# Smoothieboard_v1_1.net
KiCad netlist of a schematic drawn in Altium Designer
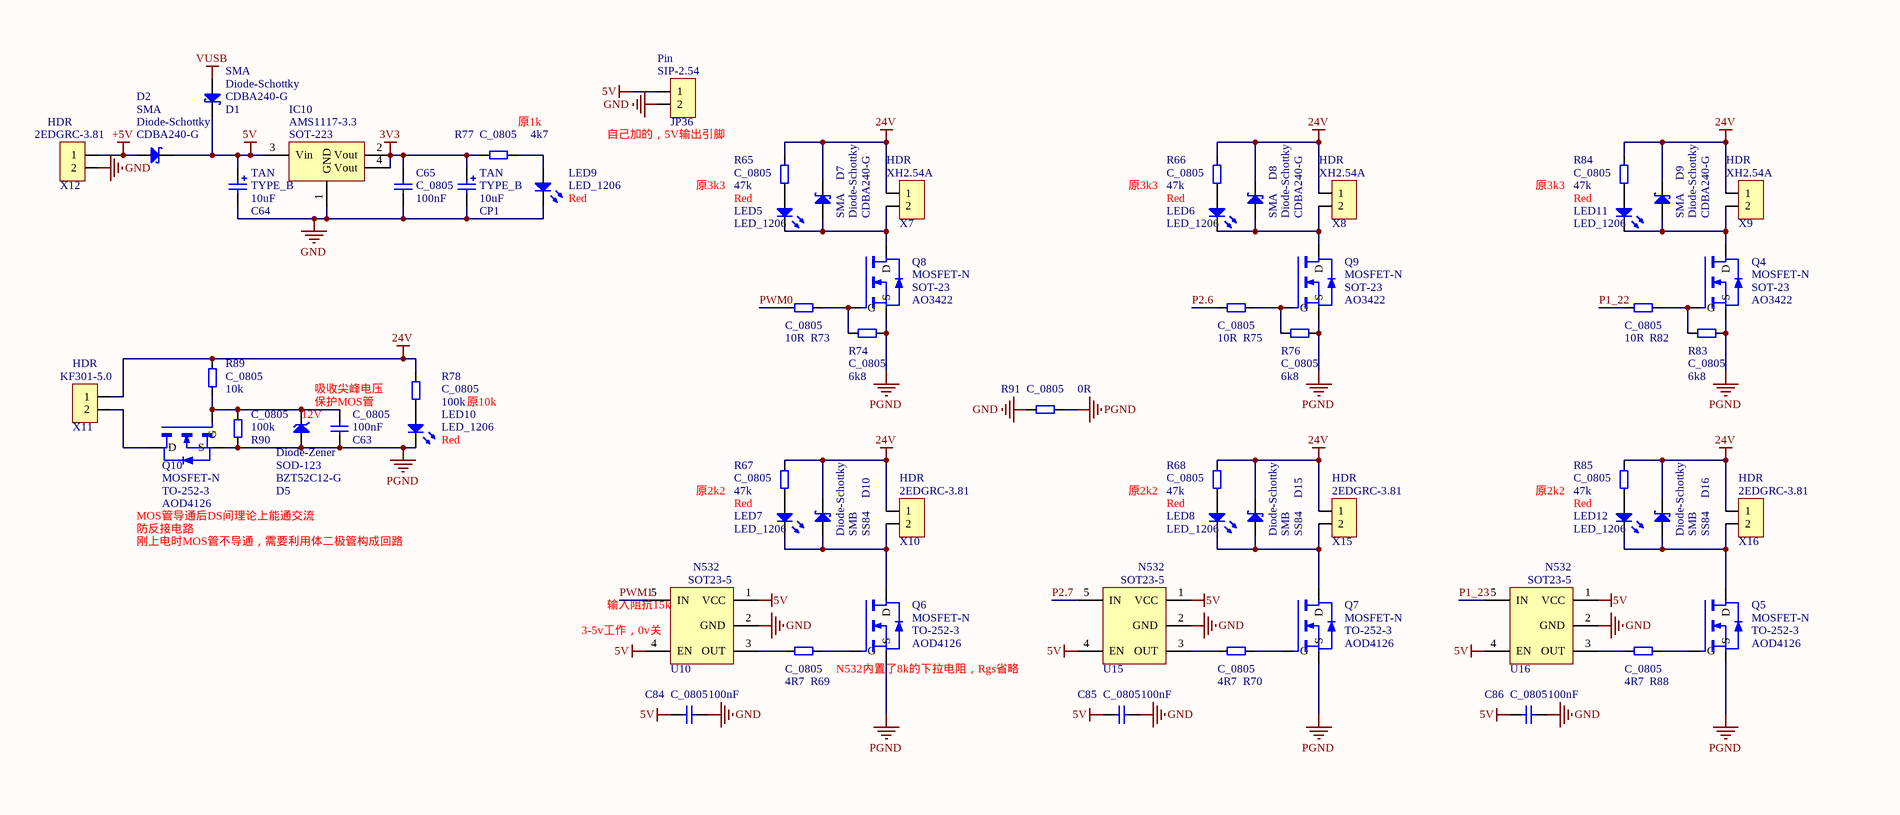
[diagram p0: Smoothieboard_v1.1.SchDoc, top left]
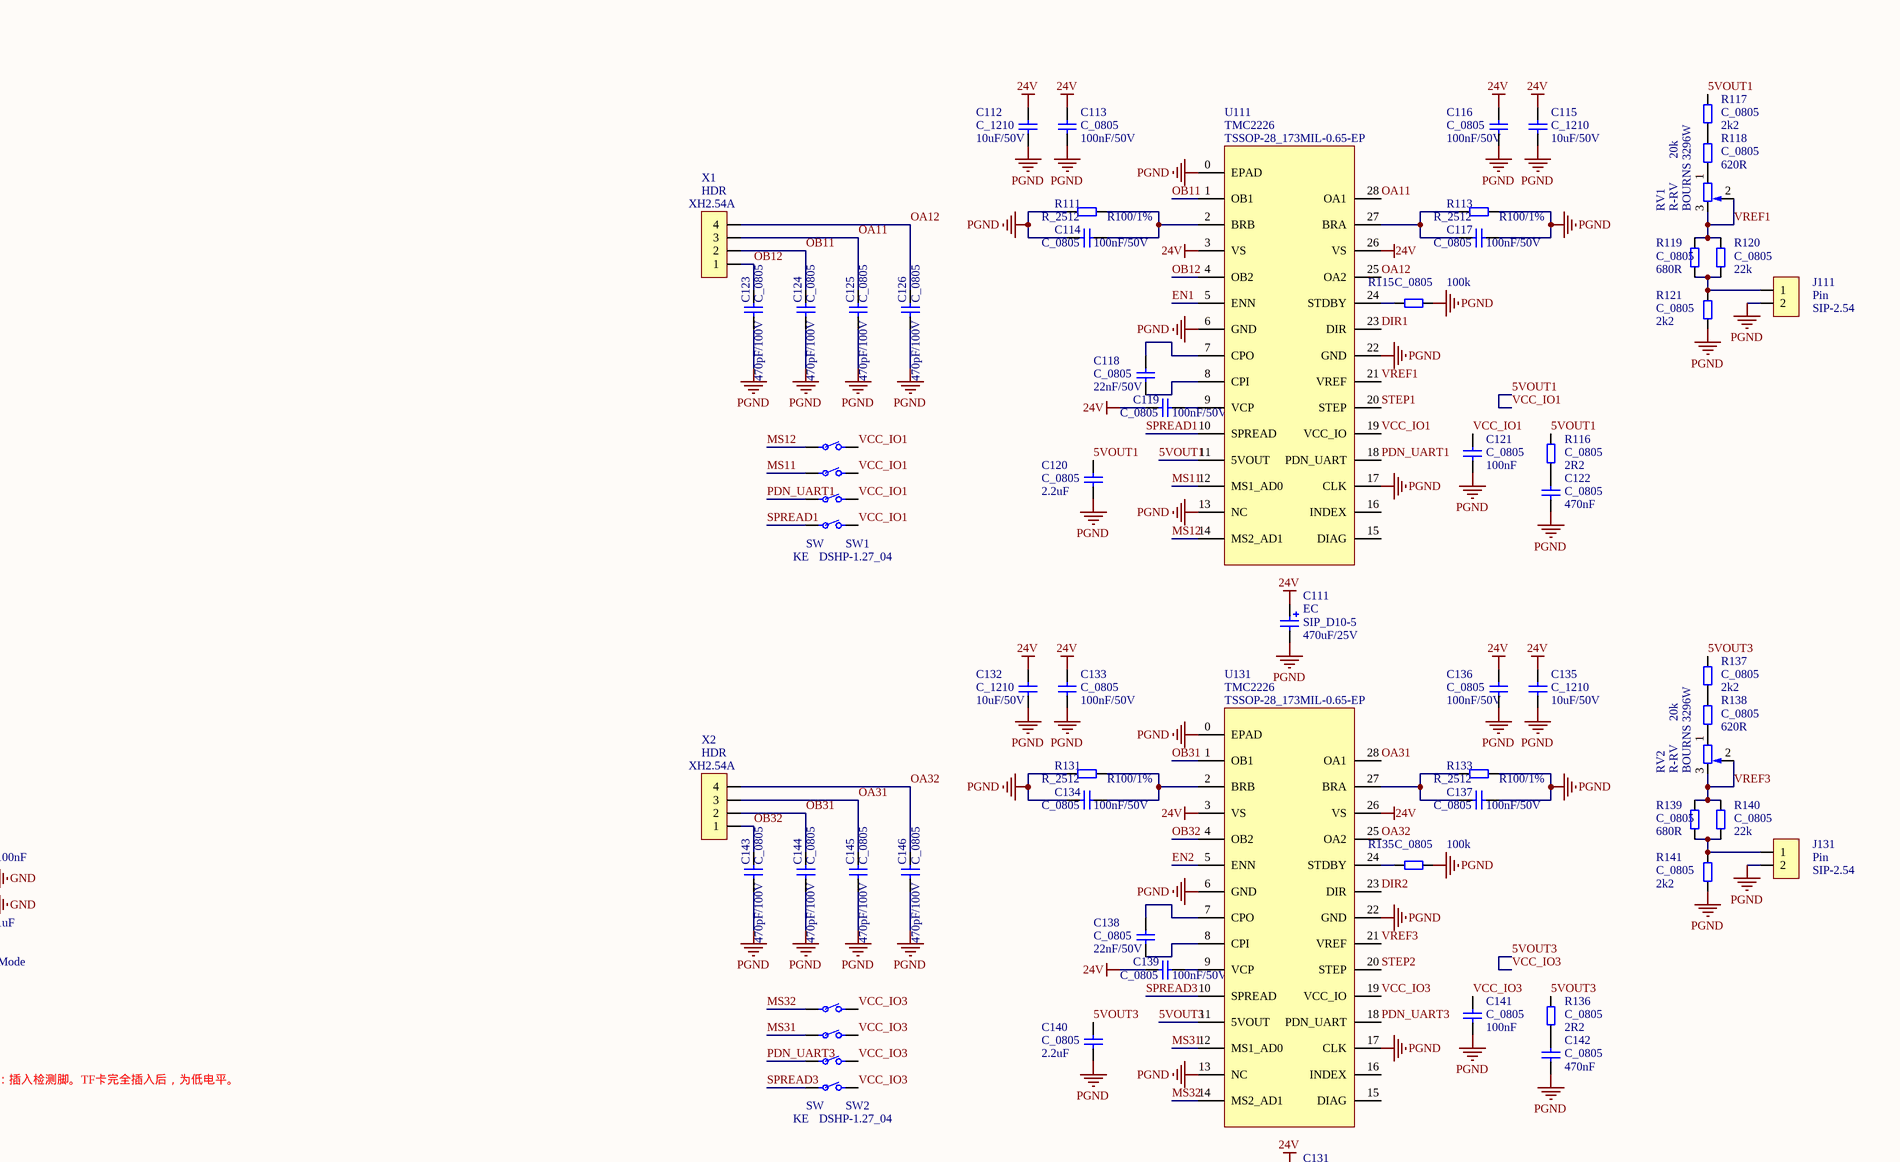
[diagram p1: Smoothieboard_v1.1.SchDoc, top right]
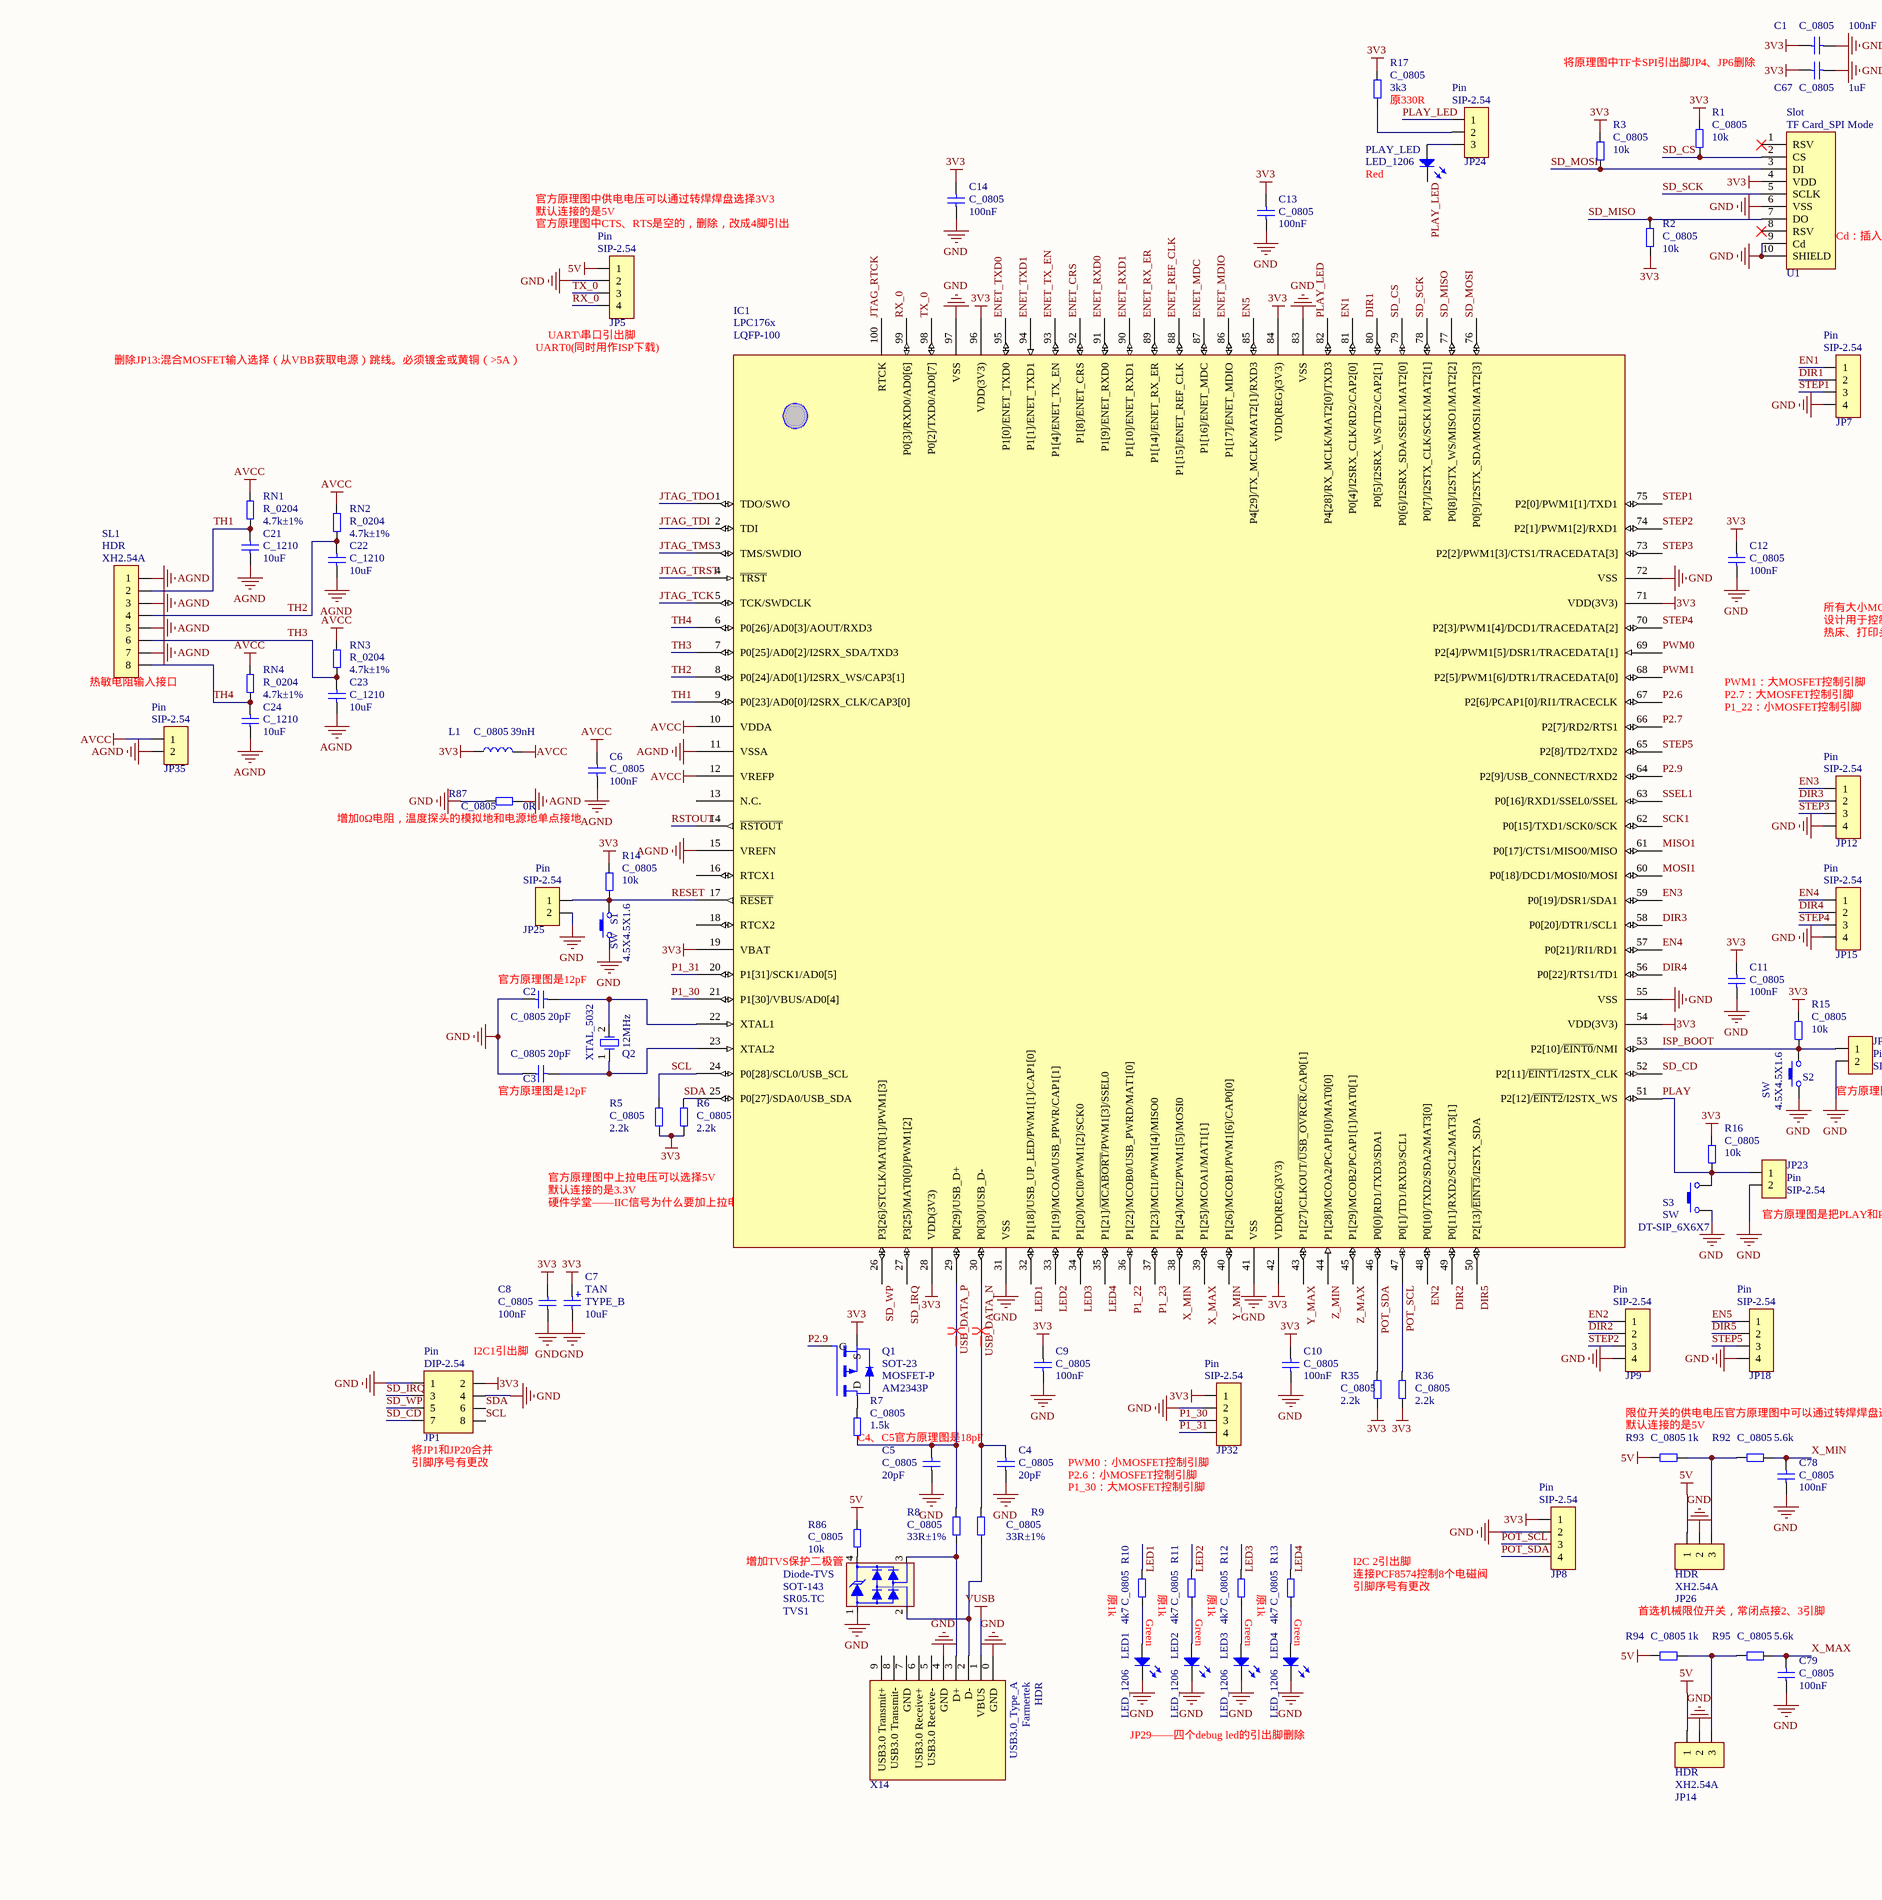
[diagram p2: Smoothieboard_v1.1.SchDoc, bottom left]
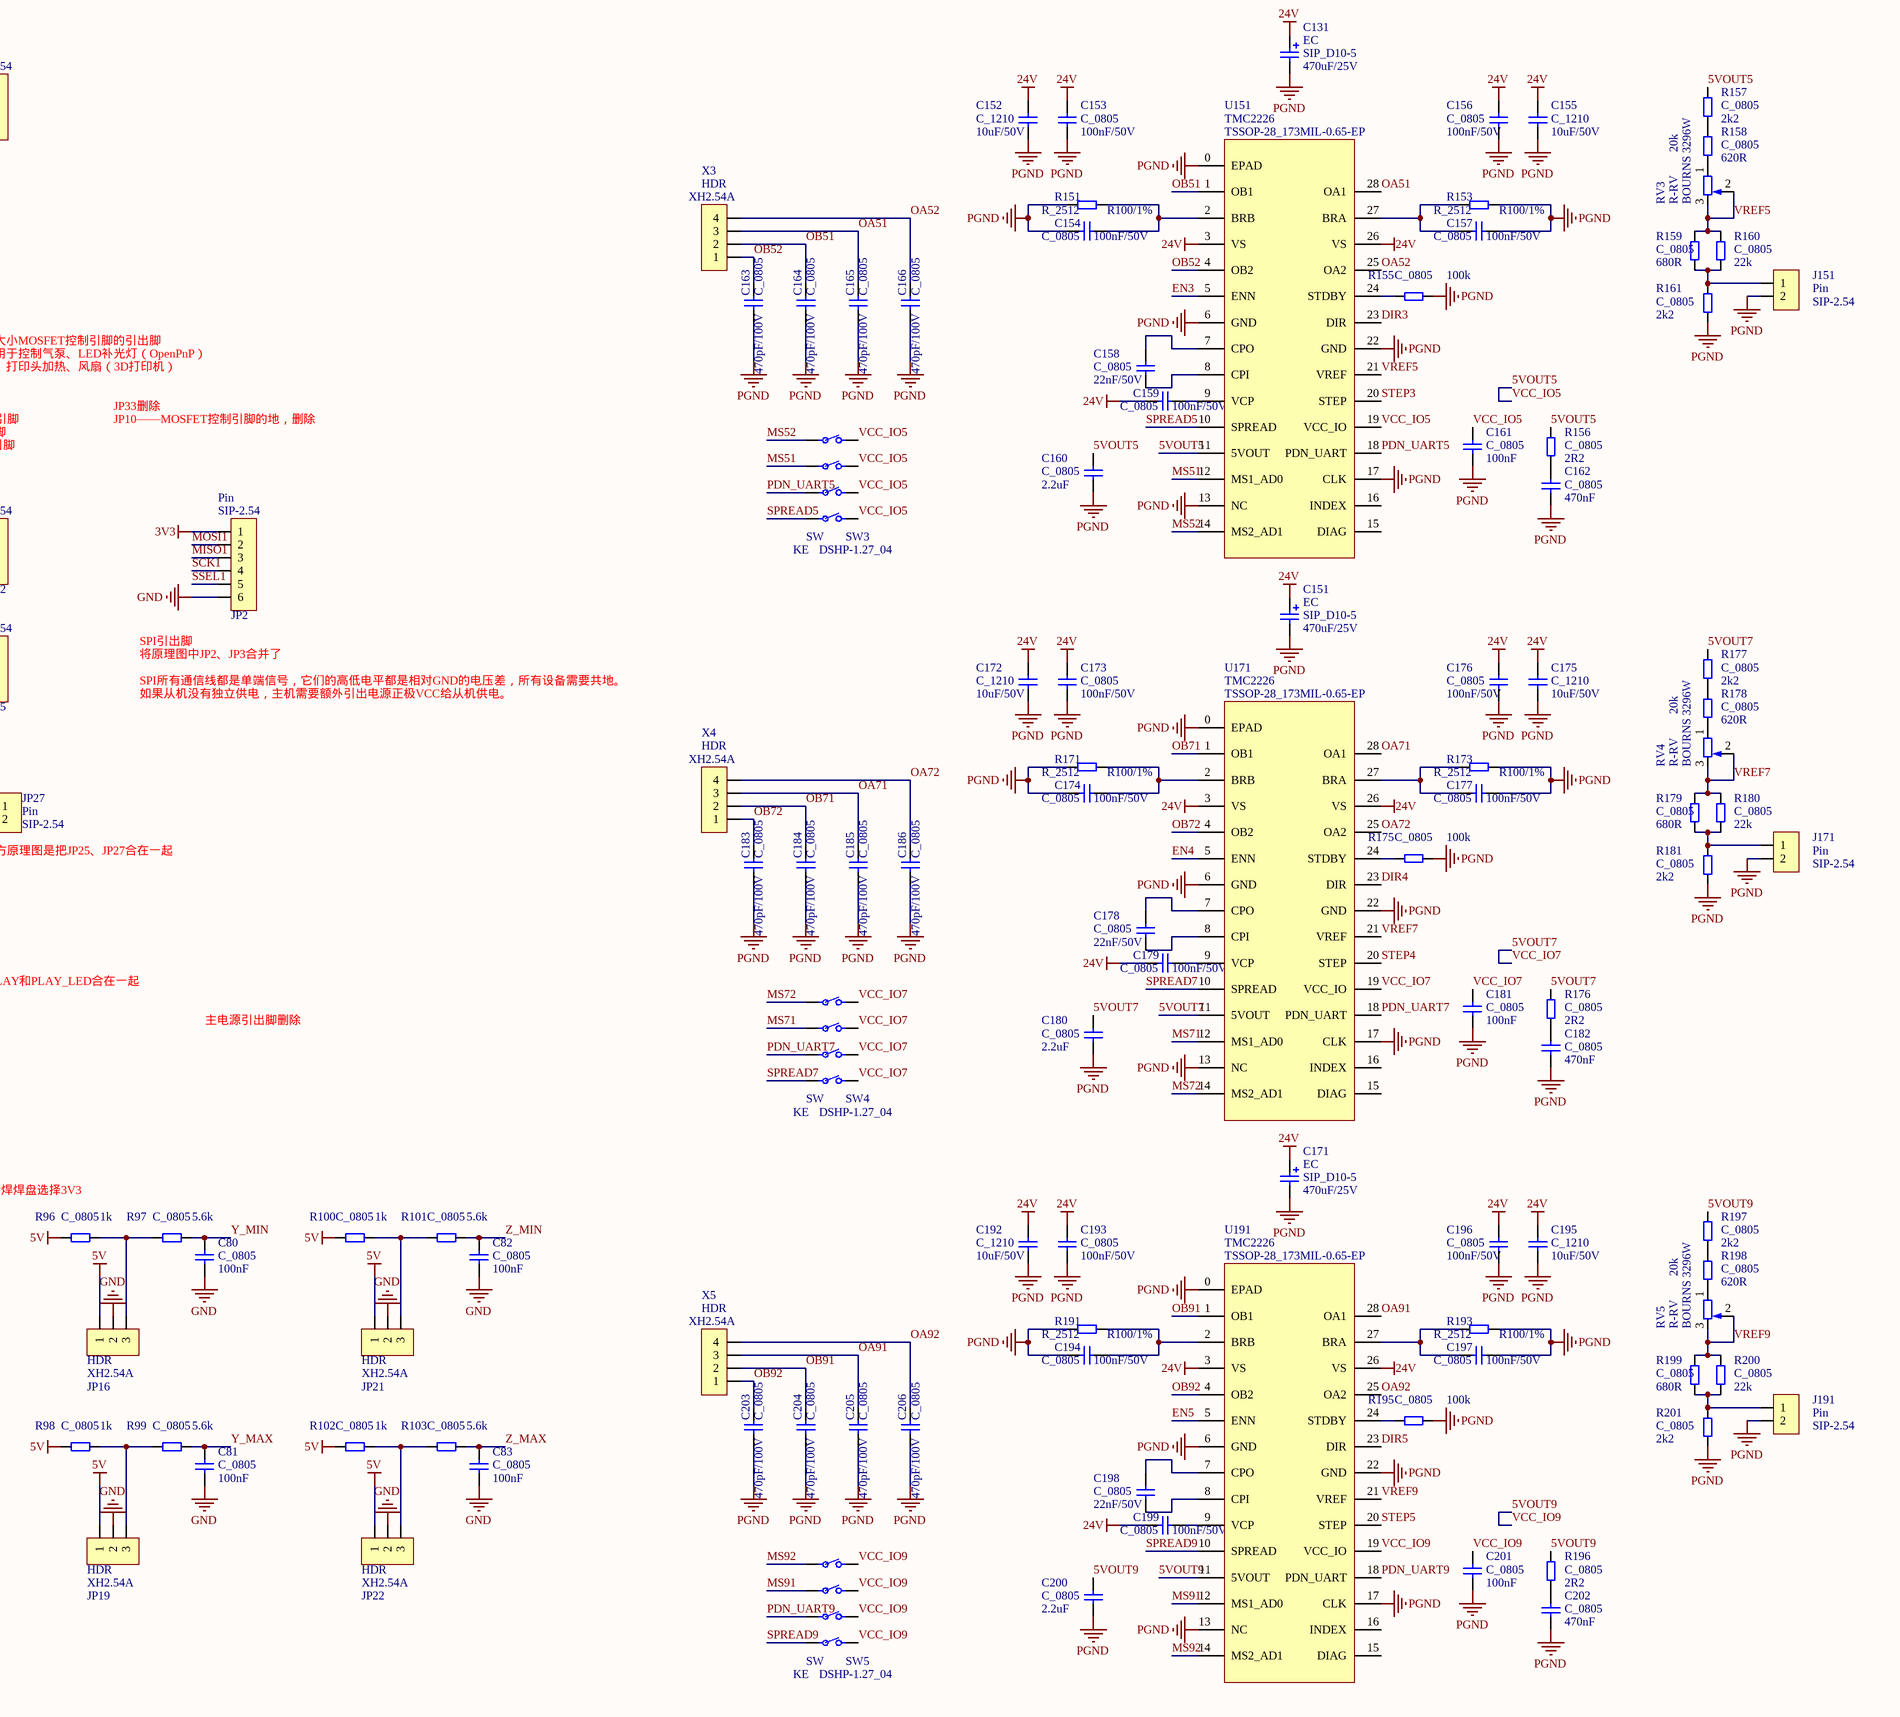
[diagram p3: Smoothieboard_v1.1.SchDoc, bottom right]

(export (version "E")
  (design (tool "Eeschema 10.0.6"))
  (components
    (comp (ref "C1")
      (value "C-MLCC_0805")
      (footprint "CAP-MLCC_0805")
      (description "贴片电容")
      (fields (field (name "TYPE/VALUE") "100nF") (field (name "FOOTPRINT INDEX") "C_0805"))
      (libsource (lib "我的集成库") (part "C-MLCC_0805"))
    )
    (comp (ref "C2")
      (value "C-MLCC_0805")
      (footprint "CAP-MLCC_0805")
      (description "贴片电容")
      (fields (field (name "TYPE/VALUE") "20pF") (field (name "FOOTPRINT INDEX") "C_0805"))
      (libsource (lib "我的集成库") (part "C-MLCC_0805"))
    )
    (comp (ref "C3")
      (value "C-MLCC_0805")
      (footprint "CAP-MLCC_0805")
      (description "贴片电容")
      (fields (field (name "TYPE/VALUE") "20pF") (field (name "FOOTPRINT INDEX") "C_0805"))
      (libsource (lib "我的集成库") (part "C-MLCC_0805"))
    )
    (comp (ref "C4")
      (value "C-MLCC_0805")
      (footprint "CAP-MLCC_0805")
      (description "贴片电容")
      (fields (field (name "TYPE/VALUE") "20pF") (field (name "FOOTPRINT INDEX") "C_0805"))
      (libsource (lib "我的集成库") (part "C-MLCC_0805"))
    )
    (comp (ref "C5")
      (value "C-MLCC_0805")
      (footprint "CAP-MLCC_0805")
      (description "贴片电容")
      (fields (field (name "TYPE/VALUE") "20pF") (field (name "FOOTPRINT INDEX") "C_0805"))
      (libsource (lib "我的集成库") (part "C-MLCC_0805"))
    )
    (comp (ref "C6")
      (value "C-MLCC_0805")
      (footprint "CAP-MLCC_0805")
      (description "贴片电容")
      (fields (field (name "TYPE/VALUE") "100nF") (field (name "FOOTPRINT INDEX") "C_0805"))
      (libsource (lib "我的集成库") (part "C-MLCC_0805"))
    )
    (comp (ref "C7")
      (value "C-TAN_Type_B")
      (footprint "CAP-TAN_TYPE_B")
      (description "贴片钽电容")
      (fields
        (field (name "FOOTPRINT INDEX") "TYPE_B")
        (field (name "SUBCLASS") "TAN")
        (field (name "TYPE/VALUE") "10uF")
      )
      (libsource (lib "我的集成库") (part "C-TAN_Type_B"))
    )
    (comp (ref "C8")
      (value "C-MLCC_0805")
      (footprint "CAP-MLCC_0805")
      (description "贴片电容")
      (fields (field (name "TYPE/VALUE") "100nF") (field (name "FOOTPRINT INDEX") "C_0805"))
      (libsource (lib "我的集成库") (part "C-MLCC_0805"))
    )
    (comp (ref "C9")
      (value "C-MLCC_0805")
      (footprint "CAP-MLCC_0805")
      (description "贴片电容")
      (fields (field (name "TYPE/VALUE") "100nF") (field (name "FOOTPRINT INDEX") "C_0805"))
      (libsource (lib "我的集成库") (part "C-MLCC_0805"))
    )
    (comp (ref "C10")
      (value "C-MLCC_0805")
      (footprint "CAP-MLCC_0805")
      (description "贴片电容")
      (fields (field (name "TYPE/VALUE") "100nF") (field (name "FOOTPRINT INDEX") "C_0805"))
      (libsource (lib "我的集成库") (part "C-MLCC_0805"))
    )
    (comp (ref "C11")
      (value "C-MLCC_0805")
      (footprint "CAP-MLCC_0805")
      (description "贴片电容")
      (fields (field (name "TYPE/VALUE") "100nF") (field (name "FOOTPRINT INDEX") "C_0805"))
      (libsource (lib "我的集成库") (part "C-MLCC_0805"))
    )
    (comp (ref "C12")
      (value "C-MLCC_0805")
      (footprint "CAP-MLCC_0805")
      (description "贴片电容")
      (fields (field (name "TYPE/VALUE") "100nF") (field (name "FOOTPRINT INDEX") "C_0805"))
      (libsource (lib "我的集成库") (part "C-MLCC_0805"))
    )
    (comp (ref "C13")
      (value "C-MLCC_0805")
      (footprint "CAP-MLCC_0805")
      (description "贴片电容")
      (fields (field (name "TYPE/VALUE") "100nF") (field (name "FOOTPRINT INDEX") "C_0805"))
      (libsource (lib "我的集成库") (part "C-MLCC_0805"))
    )
    (comp (ref "C14")
      (value "C-MLCC_0805")
      (footprint "CAP-MLCC_0805")
      (description "贴片电容")
      (fields (field (name "TYPE/VALUE") "100nF") (field (name "FOOTPRINT INDEX") "C_0805"))
      (libsource (lib "我的集成库") (part "C-MLCC_0805"))
    )
    (comp (ref "C21")
      (value "C-MLCC_1210")
      (footprint "CAP-MLCC_1210")
      (description "贴片电容")
      (fields (field (name "TYPE/VALUE") "10uF") (field (name "FOOTPRINT INDEX") "C_1210"))
      (libsource (lib "我的集成库") (part "C-MLCC_1210"))
    )
    (comp (ref "C22")
      (value "C-MLCC_1210")
      (footprint "CAP-MLCC_1210")
      (description "贴片电容")
      (fields (field (name "TYPE/VALUE") "10uF") (field (name "FOOTPRINT INDEX") "C_1210"))
      (libsource (lib "我的集成库") (part "C-MLCC_1210"))
    )
    (comp (ref "C23")
      (value "C-MLCC_1210")
      (footprint "CAP-MLCC_1210")
      (description "贴片电容")
      (fields (field (name "TYPE/VALUE") "10uF") (field (name "FOOTPRINT INDEX") "C_1210"))
      (libsource (lib "我的集成库") (part "C-MLCC_1210"))
    )
    (comp (ref "C24")
      (value "C-MLCC_1210")
      (footprint "CAP-MLCC_1210")
      (description "贴片电容")
      (fields (field (name "TYPE/VALUE") "10uF") (field (name "FOOTPRINT INDEX") "C_1210"))
      (libsource (lib "我的集成库") (part "C-MLCC_1210"))
    )
    (comp (ref "C63")
      (value "C-MLCC_0805")
      (footprint "CAP-MLCC_0805")
      (description "贴片电容")
      (fields (field (name "TYPE/VALUE") "100nF") (field (name "FOOTPRINT INDEX") "C_0805"))
      (libsource (lib "我的集成库") (part "C-MLCC_0805"))
    )
    (comp (ref "C64")
      (value "C-TAN_Type_B")
      (footprint "CAP-TAN_TYPE_B")
      (description "贴片钽电容")
      (fields
        (field (name "FOOTPRINT INDEX") "TYPE_B")
        (field (name "SUBCLASS") "TAN")
        (field (name "TYPE/VALUE") "10uF")
      )
      (libsource (lib "我的集成库") (part "C-TAN_Type_B"))
    )
    (comp (ref "C65")
      (value "C-MLCC_0805")
      (footprint "CAP-MLCC_0805")
      (description "贴片电容")
      (fields (field (name "TYPE/VALUE") "100nF") (field (name "FOOTPRINT INDEX") "C_0805"))
      (libsource (lib "我的集成库") (part "C-MLCC_0805"))
    )
    (comp (ref "C67")
      (value "C-MLCC_0805")
      (footprint "CAP-MLCC_0805")
      (description "贴片电容")
      (fields (field (name "TYPE/VALUE") "1uF") (field (name "FOOTPRINT INDEX") "C_0805"))
      (libsource (lib "我的集成库") (part "C-MLCC_0805"))
    )
    (comp (ref "C78")
      (value "C-MLCC_0805")
      (footprint "CAP-MLCC_0805")
      (description "贴片电容")
      (fields (field (name "TYPE/VALUE") "100nF") (field (name "FOOTPRINT INDEX") "C_0805"))
      (libsource (lib "我的集成库") (part "C-MLCC_0805"))
    )
    (comp (ref "C79")
      (value "C-MLCC_0805")
      (footprint "CAP-MLCC_0805")
      (description "贴片电容")
      (fields (field (name "TYPE/VALUE") "100nF") (field (name "FOOTPRINT INDEX") "C_0805"))
      (libsource (lib "我的集成库") (part "C-MLCC_0805"))
    )
    (comp (ref "C80")
      (value "C-MLCC_0805")
      (footprint "CAP-MLCC_0805")
      (description "贴片电容")
      (fields (field (name "TYPE/VALUE") "100nF") (field (name "FOOTPRINT INDEX") "C_0805"))
      (libsource (lib "我的集成库") (part "C-MLCC_0805"))
    )
    (comp (ref "C81")
      (value "C-MLCC_0805")
      (footprint "CAP-MLCC_0805")
      (description "贴片电容")
      (fields (field (name "TYPE/VALUE") "100nF") (field (name "FOOTPRINT INDEX") "C_0805"))
      (libsource (lib "我的集成库") (part "C-MLCC_0805"))
    )
    (comp (ref "C82")
      (value "C-MLCC_0805")
      (footprint "CAP-MLCC_0805")
      (description "贴片电容")
      (fields (field (name "TYPE/VALUE") "100nF") (field (name "FOOTPRINT INDEX") "C_0805"))
      (libsource (lib "我的集成库") (part "C-MLCC_0805"))
    )
    (comp (ref "C83")
      (value "C-MLCC_0805")
      (footprint "CAP-MLCC_0805")
      (description "贴片电容")
      (fields (field (name "TYPE/VALUE") "100nF") (field (name "FOOTPRINT INDEX") "C_0805"))
      (libsource (lib "我的集成库") (part "C-MLCC_0805"))
    )
    (comp (ref "C84")
      (value "C-MLCC_0805")
      (footprint "CAP-MLCC_0805")
      (description "贴片电容")
      (fields (field (name "TYPE/VALUE") "100nF") (field (name "FOOTPRINT INDEX") "C_0805"))
      (libsource (lib "我的集成库") (part "C-MLCC_0805"))
    )
    (comp (ref "C85")
      (value "C-MLCC_0805")
      (footprint "CAP-MLCC_0805")
      (description "贴片电容")
      (fields (field (name "TYPE/VALUE") "100nF") (field (name "FOOTPRINT INDEX") "C_0805"))
      (libsource (lib "我的集成库") (part "C-MLCC_0805"))
    )
    (comp (ref "C86")
      (value "C-MLCC_0805")
      (footprint "CAP-MLCC_0805")
      (description "贴片电容")
      (fields (field (name "TYPE/VALUE") "100nF") (field (name "FOOTPRINT INDEX") "C_0805"))
      (libsource (lib "我的集成库") (part "C-MLCC_0805"))
    )
    (comp (ref "C111")
      (value "C-EC-SIP_D10-5")
      (footprint "CAP-EC-SIP_D10-5")
      (description "直插电解电容")
      (fields
        (field (name "FOOTPRINT INDEX") "SIP_D10-5")
        (field (name "SUBCLASS") "EC")
        (field (name "TYPE/VALUE") "470uF/25V")
      )
      (libsource (lib "我的集成库") (part "C-EC-SIP_D10-5"))
    )
    (comp (ref "C112")
      (value "C-MLCC_1210")
      (footprint "CAP-MLCC_1210")
      (description "贴片电容")
      (fields (field (name "TYPE/VALUE") "10uF/50V") (field (name "FOOTPRINT INDEX") "C_1210"))
      (libsource (lib "我的集成库") (part "C-MLCC_1210"))
    )
    (comp (ref "C113")
      (value "C-MLCC_0805")
      (footprint "CAP-MLCC_0805")
      (description "贴片电容")
      (fields (field (name "TYPE/VALUE") "100nF/50V") (field (name "FOOTPRINT INDEX") "C_0805"))
      (libsource (lib "我的集成库") (part "C-MLCC_0805"))
    )
    (comp (ref "C114")
      (value "C-MLCC_0805")
      (footprint "CAP-MLCC_0805")
      (description "贴片电容")
      (fields (field (name "TYPE/VALUE") "100nF/50V") (field (name "FOOTPRINT INDEX") "C_0805"))
      (libsource (lib "我的集成库") (part "C-MLCC_0805"))
    )
    (comp (ref "C115")
      (value "C-MLCC_1210")
      (footprint "CAP-MLCC_1210")
      (description "贴片电容")
      (fields (field (name "TYPE/VALUE") "10uF/50V") (field (name "FOOTPRINT INDEX") "C_1210"))
      (libsource (lib "我的集成库") (part "C-MLCC_1210"))
    )
    (comp (ref "C116")
      (value "C-MLCC_0805")
      (footprint "CAP-MLCC_0805")
      (description "贴片电容")
      (fields (field (name "TYPE/VALUE") "100nF/50V") (field (name "FOOTPRINT INDEX") "C_0805"))
      (libsource (lib "我的集成库") (part "C-MLCC_0805"))
    )
    (comp (ref "C117")
      (value "C-MLCC_0805")
      (footprint "CAP-MLCC_0805")
      (description "贴片电容")
      (fields (field (name "TYPE/VALUE") "100nF/50V") (field (name "FOOTPRINT INDEX") "C_0805"))
      (libsource (lib "我的集成库") (part "C-MLCC_0805"))
    )
    (comp (ref "C118")
      (value "C-MLCC_0805")
      (footprint "CAP-MLCC_0805")
      (description "贴片电容")
      (fields (field (name "TYPE/VALUE") "22nF/50V") (field (name "FOOTPRINT INDEX") "C_0805"))
      (libsource (lib "我的集成库") (part "C-MLCC_0805"))
    )
    (comp (ref "C119")
      (value "C-MLCC_0805")
      (footprint "CAP-MLCC_0805")
      (description "贴片电容")
      (fields (field (name "TYPE/VALUE") "100nF/50V") (field (name "FOOTPRINT INDEX") "C_0805"))
      (libsource (lib "我的集成库") (part "C-MLCC_0805"))
    )
    (comp (ref "C120")
      (value "C-MLCC_0805")
      (footprint "CAP-MLCC_0805")
      (description "贴片电容")
      (fields (field (name "TYPE/VALUE") "2.2uF") (field (name "FOOTPRINT INDEX") "C_0805"))
      (libsource (lib "我的集成库") (part "C-MLCC_0805"))
    )
    (comp (ref "C121")
      (value "C-MLCC_0805")
      (footprint "CAP-MLCC_0805")
      (description "贴片电容")
      (fields (field (name "TYPE/VALUE") "100nF") (field (name "FOOTPRINT INDEX") "C_0805"))
      (libsource (lib "我的集成库") (part "C-MLCC_0805"))
    )
    (comp (ref "C122")
      (value "C-MLCC_0805")
      (footprint "CAP-MLCC_0805")
      (description "贴片电容")
      (fields (field (name "TYPE/VALUE") "470nF") (field (name "FOOTPRINT INDEX") "C_0805"))
      (libsource (lib "我的集成库") (part "C-MLCC_0805"))
    )
    (comp (ref "C123")
      (value "C-MLCC_0805")
      (footprint "CAP-MLCC_0805")
      (description "贴片电容")
      (fields (field (name "TYPE/VALUE") "470pF/100V") (field (name "FOOTPRINT INDEX") "C_0805"))
      (libsource (lib "我的集成库") (part "C-MLCC_0805"))
    )
    (comp (ref "C124")
      (value "C-MLCC_0805")
      (footprint "CAP-MLCC_0805")
      (description "贴片电容")
      (fields (field (name "TYPE/VALUE") "470pF/100V") (field (name "FOOTPRINT INDEX") "C_0805"))
      (libsource (lib "我的集成库") (part "C-MLCC_0805"))
    )
    (comp (ref "C125")
      (value "C-MLCC_0805")
      (footprint "CAP-MLCC_0805")
      (description "贴片电容")
      (fields (field (name "TYPE/VALUE") "470pF/100V") (field (name "FOOTPRINT INDEX") "C_0805"))
      (libsource (lib "我的集成库") (part "C-MLCC_0805"))
    )
    (comp (ref "C126")
      (value "C-MLCC_0805")
      (footprint "CAP-MLCC_0805")
      (description "贴片电容")
      (fields (field (name "TYPE/VALUE") "470pF/100V") (field (name "FOOTPRINT INDEX") "C_0805"))
      (libsource (lib "我的集成库") (part "C-MLCC_0805"))
    )
    (comp (ref "C131")
      (value "C-EC-SIP_D10-5")
      (footprint "CAP-EC-SIP_D10-5")
      (description "直插电解电容")
      (fields
        (field (name "FOOTPRINT INDEX") "SIP_D10-5")
        (field (name "SUBCLASS") "EC")
        (field (name "TYPE/VALUE") "470uF/25V")
      )
      (libsource (lib "我的集成库") (part "C-EC-SIP_D10-5"))
    )
    (comp (ref "C132")
      (value "C-MLCC_1210")
      (footprint "CAP-MLCC_1210")
      (description "贴片电容")
      (fields (field (name "TYPE/VALUE") "10uF/50V") (field (name "FOOTPRINT INDEX") "C_1210"))
      (libsource (lib "我的集成库") (part "C-MLCC_1210"))
    )
    (comp (ref "C133")
      (value "C-MLCC_0805")
      (footprint "CAP-MLCC_0805")
      (description "贴片电容")
      (fields (field (name "TYPE/VALUE") "100nF/50V") (field (name "FOOTPRINT INDEX") "C_0805"))
      (libsource (lib "我的集成库") (part "C-MLCC_0805"))
    )
    (comp (ref "C134")
      (value "C-MLCC_0805")
      (footprint "CAP-MLCC_0805")
      (description "贴片电容")
      (fields (field (name "TYPE/VALUE") "100nF/50V") (field (name "FOOTPRINT INDEX") "C_0805"))
      (libsource (lib "我的集成库") (part "C-MLCC_0805"))
    )
    (comp (ref "C135")
      (value "C-MLCC_1210")
      (footprint "CAP-MLCC_1210")
      (description "贴片电容")
      (fields (field (name "TYPE/VALUE") "10uF/50V") (field (name "FOOTPRINT INDEX") "C_1210"))
      (libsource (lib "我的集成库") (part "C-MLCC_1210"))
    )
    (comp (ref "C136")
      (value "C-MLCC_0805")
      (footprint "CAP-MLCC_0805")
      (description "贴片电容")
      (fields (field (name "TYPE/VALUE") "100nF/50V") (field (name "FOOTPRINT INDEX") "C_0805"))
      (libsource (lib "我的集成库") (part "C-MLCC_0805"))
    )
    (comp (ref "C137")
      (value "C-MLCC_0805")
      (footprint "CAP-MLCC_0805")
      (description "贴片电容")
      (fields (field (name "TYPE/VALUE") "100nF/50V") (field (name "FOOTPRINT INDEX") "C_0805"))
      (libsource (lib "我的集成库") (part "C-MLCC_0805"))
    )
    (comp (ref "C138")
      (value "C-MLCC_0805")
      (footprint "CAP-MLCC_0805")
      (description "贴片电容")
      (fields (field (name "TYPE/VALUE") "22nF/50V") (field (name "FOOTPRINT INDEX") "C_0805"))
      (libsource (lib "我的集成库") (part "C-MLCC_0805"))
    )
    (comp (ref "C139")
      (value "C-MLCC_0805")
      (footprint "CAP-MLCC_0805")
      (description "贴片电容")
      (fields (field (name "TYPE/VALUE") "100nF/50V") (field (name "FOOTPRINT INDEX") "C_0805"))
      (libsource (lib "我的集成库") (part "C-MLCC_0805"))
    )
    (comp (ref "C140")
      (value "C-MLCC_0805")
      (footprint "CAP-MLCC_0805")
      (description "贴片电容")
      (fields (field (name "TYPE/VALUE") "2.2uF") (field (name "FOOTPRINT INDEX") "C_0805"))
      (libsource (lib "我的集成库") (part "C-MLCC_0805"))
    )
    (comp (ref "C141")
      (value "C-MLCC_0805")
      (footprint "CAP-MLCC_0805")
      (description "贴片电容")
      (fields (field (name "TYPE/VALUE") "100nF") (field (name "FOOTPRINT INDEX") "C_0805"))
      (libsource (lib "我的集成库") (part "C-MLCC_0805"))
    )
    (comp (ref "C142")
      (value "C-MLCC_0805")
      (footprint "CAP-MLCC_0805")
      (description "贴片电容")
      (fields (field (name "TYPE/VALUE") "470nF") (field (name "FOOTPRINT INDEX") "C_0805"))
      (libsource (lib "我的集成库") (part "C-MLCC_0805"))
    )
    (comp (ref "C143")
      (value "C-MLCC_0805")
      (footprint "CAP-MLCC_0805")
      (description "贴片电容")
      (fields (field (name "TYPE/VALUE") "470pF/100V") (field (name "FOOTPRINT INDEX") "C_0805"))
      (libsource (lib "我的集成库") (part "C-MLCC_0805"))
    )
    (comp (ref "C144")
      (value "C-MLCC_0805")
      (footprint "CAP-MLCC_0805")
      (description "贴片电容")
      (fields (field (name "TYPE/VALUE") "470pF/100V") (field (name "FOOTPRINT INDEX") "C_0805"))
      (libsource (lib "我的集成库") (part "C-MLCC_0805"))
    )
    (comp (ref "C145")
      (value "C-MLCC_0805")
      (footprint "CAP-MLCC_0805")
      (description "贴片电容")
      (fields (field (name "TYPE/VALUE") "470pF/100V") (field (name "FOOTPRINT INDEX") "C_0805"))
      (libsource (lib "我的集成库") (part "C-MLCC_0805"))
    )
    (comp (ref "C146")
      (value "C-MLCC_0805")
      (footprint "CAP-MLCC_0805")
      (description "贴片电容")
      (fields (field (name "TYPE/VALUE") "470pF/100V") (field (name "FOOTPRINT INDEX") "C_0805"))
      (libsource (lib "我的集成库") (part "C-MLCC_0805"))
    )
    (comp (ref "C151")
      (value "C-EC-SIP_D10-5")
      (footprint "CAP-EC-SIP_D10-5")
      (description "直插电解电容")
      (fields
        (field (name "FOOTPRINT INDEX") "SIP_D10-5")
        (field (name "SUBCLASS") "EC")
        (field (name "TYPE/VALUE") "470uF/25V")
      )
      (libsource (lib "我的集成库") (part "C-EC-SIP_D10-5"))
    )
    (comp (ref "C152")
      (value "C-MLCC_1210")
      (footprint "CAP-MLCC_1210")
      (description "贴片电容")
      (fields (field (name "TYPE/VALUE") "10uF/50V") (field (name "FOOTPRINT INDEX") "C_1210"))
      (libsource (lib "我的集成库") (part "C-MLCC_1210"))
    )
    (comp (ref "C153")
      (value "C-MLCC_0805")
      (footprint "CAP-MLCC_0805")
      (description "贴片电容")
      (fields (field (name "TYPE/VALUE") "100nF/50V") (field (name "FOOTPRINT INDEX") "C_0805"))
      (libsource (lib "我的集成库") (part "C-MLCC_0805"))
    )
    (comp (ref "C154")
      (value "C-MLCC_0805")
      (footprint "CAP-MLCC_0805")
      (description "贴片电容")
      (fields (field (name "TYPE/VALUE") "100nF/50V") (field (name "FOOTPRINT INDEX") "C_0805"))
      (libsource (lib "我的集成库") (part "C-MLCC_0805"))
    )
    (comp (ref "C155")
      (value "C-MLCC_1210")
      (footprint "CAP-MLCC_1210")
      (description "贴片电容")
      (fields (field (name "TYPE/VALUE") "10uF/50V") (field (name "FOOTPRINT INDEX") "C_1210"))
      (libsource (lib "我的集成库") (part "C-MLCC_1210"))
    )
    (comp (ref "C156")
      (value "C-MLCC_0805")
      (footprint "CAP-MLCC_0805")
      (description "贴片电容")
      (fields (field (name "TYPE/VALUE") "100nF/50V") (field (name "FOOTPRINT INDEX") "C_0805"))
      (libsource (lib "我的集成库") (part "C-MLCC_0805"))
    )
    (comp (ref "C157")
      (value "C-MLCC_0805")
      (footprint "CAP-MLCC_0805")
      (description "贴片电容")
      (fields (field (name "TYPE/VALUE") "100nF/50V") (field (name "FOOTPRINT INDEX") "C_0805"))
      (libsource (lib "我的集成库") (part "C-MLCC_0805"))
    )
    (comp (ref "C158")
      (value "C-MLCC_0805")
      (footprint "CAP-MLCC_0805")
      (description "贴片电容")
      (fields (field (name "TYPE/VALUE") "22nF/50V") (field (name "FOOTPRINT INDEX") "C_0805"))
      (libsource (lib "我的集成库") (part "C-MLCC_0805"))
    )
    (comp (ref "C159")
      (value "C-MLCC_0805")
      (footprint "CAP-MLCC_0805")
      (description "贴片电容")
      (fields (field (name "TYPE/VALUE") "100nF/50V") (field (name "FOOTPRINT INDEX") "C_0805"))
      (libsource (lib "我的集成库") (part "C-MLCC_0805"))
    )
    (comp (ref "C160")
      (value "C-MLCC_0805")
      (footprint "CAP-MLCC_0805")
      (description "贴片电容")
      (fields (field (name "TYPE/VALUE") "2.2uF") (field (name "FOOTPRINT INDEX") "C_0805"))
      (libsource (lib "我的集成库") (part "C-MLCC_0805"))
    )
    (comp (ref "C161")
      (value "C-MLCC_0805")
      (footprint "CAP-MLCC_0805")
      (description "贴片电容")
      (fields (field (name "TYPE/VALUE") "100nF") (field (name "FOOTPRINT INDEX") "C_0805"))
      (libsource (lib "我的集成库") (part "C-MLCC_0805"))
    )
    (comp (ref "C162")
      (value "C-MLCC_0805")
      (footprint "CAP-MLCC_0805")
      (description "贴片电容")
      (fields (field (name "TYPE/VALUE") "470nF") (field (name "FOOTPRINT INDEX") "C_0805"))
      (libsource (lib "我的集成库") (part "C-MLCC_0805"))
    )
    (comp (ref "C163")
      (value "C-MLCC_0805")
      (footprint "CAP-MLCC_0805")
      (description "贴片电容")
      (fields (field (name "TYPE/VALUE") "470pF/100V") (field (name "FOOTPRINT INDEX") "C_0805"))
      (libsource (lib "我的集成库") (part "C-MLCC_0805"))
    )
    (comp (ref "C164")
      (value "C-MLCC_0805")
      (footprint "CAP-MLCC_0805")
      (description "贴片电容")
      (fields (field (name "TYPE/VALUE") "470pF/100V") (field (name "FOOTPRINT INDEX") "C_0805"))
      (libsource (lib "我的集成库") (part "C-MLCC_0805"))
    )
    (comp (ref "C165")
      (value "C-MLCC_0805")
      (footprint "CAP-MLCC_0805")
      (description "贴片电容")
      (fields (field (name "TYPE/VALUE") "470pF/100V") (field (name "FOOTPRINT INDEX") "C_0805"))
      (libsource (lib "我的集成库") (part "C-MLCC_0805"))
    )
    (comp (ref "C166")
      (value "C-MLCC_0805")
      (footprint "CAP-MLCC_0805")
      (description "贴片电容")
      (fields (field (name "TYPE/VALUE") "470pF/100V") (field (name "FOOTPRINT INDEX") "C_0805"))
      (libsource (lib "我的集成库") (part "C-MLCC_0805"))
    )
    (comp (ref "C171")
      (value "C-EC-SIP_D10-5")
      (footprint "CAP-EC-SIP_D10-5")
      (description "直插电解电容")
      (fields
        (field (name "FOOTPRINT INDEX") "SIP_D10-5")
        (field (name "SUBCLASS") "EC")
        (field (name "TYPE/VALUE") "470uF/25V")
      )
      (libsource (lib "我的集成库") (part "C-EC-SIP_D10-5"))
    )
    (comp (ref "C172")
      (value "C-MLCC_1210")
      (footprint "CAP-MLCC_1210")
      (description "贴片电容")
      (fields (field (name "TYPE/VALUE") "10uF/50V") (field (name "FOOTPRINT INDEX") "C_1210"))
      (libsource (lib "我的集成库") (part "C-MLCC_1210"))
    )
    (comp (ref "C173")
      (value "C-MLCC_0805")
      (footprint "CAP-MLCC_0805")
      (description "贴片电容")
      (fields (field (name "TYPE/VALUE") "100nF/50V") (field (name "FOOTPRINT INDEX") "C_0805"))
      (libsource (lib "我的集成库") (part "C-MLCC_0805"))
    )
    (comp (ref "C174")
      (value "C-MLCC_0805")
      (footprint "CAP-MLCC_0805")
      (description "贴片电容")
      (fields (field (name "TYPE/VALUE") "100nF/50V") (field (name "FOOTPRINT INDEX") "C_0805"))
      (libsource (lib "我的集成库") (part "C-MLCC_0805"))
    )
    (comp (ref "C175")
      (value "C-MLCC_1210")
      (footprint "CAP-MLCC_1210")
      (description "贴片电容")
      (fields (field (name "TYPE/VALUE") "10uF/50V") (field (name "FOOTPRINT INDEX") "C_1210"))
      (libsource (lib "我的集成库") (part "C-MLCC_1210"))
    )
    (comp (ref "C176")
      (value "C-MLCC_0805")
      (footprint "CAP-MLCC_0805")
      (description "贴片电容")
      (fields (field (name "TYPE/VALUE") "100nF/50V") (field (name "FOOTPRINT INDEX") "C_0805"))
      (libsource (lib "我的集成库") (part "C-MLCC_0805"))
    )
    (comp (ref "C177")
      (value "C-MLCC_0805")
      (footprint "CAP-MLCC_0805")
      (description "贴片电容")
      (fields (field (name "TYPE/VALUE") "100nF/50V") (field (name "FOOTPRINT INDEX") "C_0805"))
      (libsource (lib "我的集成库") (part "C-MLCC_0805"))
    )
    (comp (ref "C178")
      (value "C-MLCC_0805")
      (footprint "CAP-MLCC_0805")
      (description "贴片电容")
      (fields (field (name "TYPE/VALUE") "22nF/50V") (field (name "FOOTPRINT INDEX") "C_0805"))
      (libsource (lib "我的集成库") (part "C-MLCC_0805"))
    )
    (comp (ref "C179")
      (value "C-MLCC_0805")
      (footprint "CAP-MLCC_0805")
      (description "贴片电容")
      (fields (field (name "TYPE/VALUE") "100nF/50V") (field (name "FOOTPRINT INDEX") "C_0805"))
      (libsource (lib "我的集成库") (part "C-MLCC_0805"))
    )
    (comp (ref "C180")
      (value "C-MLCC_0805")
      (footprint "CAP-MLCC_0805")
      (description "贴片电容")
      (fields (field (name "TYPE/VALUE") "2.2uF") (field (name "FOOTPRINT INDEX") "C_0805"))
      (libsource (lib "我的集成库") (part "C-MLCC_0805"))
    )
    (comp (ref "C181")
      (value "C-MLCC_0805")
      (footprint "CAP-MLCC_0805")
      (description "贴片电容")
      (fields (field (name "TYPE/VALUE") "100nF") (field (name "FOOTPRINT INDEX") "C_0805"))
      (libsource (lib "我的集成库") (part "C-MLCC_0805"))
    )
    (comp (ref "C182")
      (value "C-MLCC_0805")
      (footprint "CAP-MLCC_0805")
      (description "贴片电容")
      (fields (field (name "TYPE/VALUE") "470nF") (field (name "FOOTPRINT INDEX") "C_0805"))
      (libsource (lib "我的集成库") (part "C-MLCC_0805"))
    )
    (comp (ref "C183")
      (value "C-MLCC_0805")
      (footprint "CAP-MLCC_0805")
      (description "贴片电容")
      (fields (field (name "TYPE/VALUE") "470pF/100V") (field (name "FOOTPRINT INDEX") "C_0805"))
      (libsource (lib "我的集成库") (part "C-MLCC_0805"))
    )
    (comp (ref "C184")
      (value "C-MLCC_0805")
      (footprint "CAP-MLCC_0805")
      (description "贴片电容")
      (fields (field (name "TYPE/VALUE") "470pF/100V") (field (name "FOOTPRINT INDEX") "C_0805"))
      (libsource (lib "我的集成库") (part "C-MLCC_0805"))
    )
    (comp (ref "C185")
      (value "C-MLCC_0805")
      (footprint "CAP-MLCC_0805")
      (description "贴片电容")
      (fields (field (name "TYPE/VALUE") "470pF/100V") (field (name "FOOTPRINT INDEX") "C_0805"))
      (libsource (lib "我的集成库") (part "C-MLCC_0805"))
    )
    (comp (ref "C186")
      (value "C-MLCC_0805")
      (footprint "CAP-MLCC_0805")
      (description "贴片电容")
      (fields (field (name "TYPE/VALUE") "470pF/100V") (field (name "FOOTPRINT INDEX") "C_0805"))
      (libsource (lib "我的集成库") (part "C-MLCC_0805"))
    )
    (comp (ref "C192")
      (value "C-MLCC_1210")
      (footprint "CAP-MLCC_1210")
      (description "贴片电容")
      (fields (field (name "TYPE/VALUE") "10uF/50V") (field (name "FOOTPRINT INDEX") "C_1210"))
      (libsource (lib "我的集成库") (part "C-MLCC_1210"))
    )
    (comp (ref "C193")
      (value "C-MLCC_0805")
      (footprint "CAP-MLCC_0805")
      (description "贴片电容")
      (fields (field (name "TYPE/VALUE") "100nF/50V") (field (name "FOOTPRINT INDEX") "C_0805"))
      (libsource (lib "我的集成库") (part "C-MLCC_0805"))
    )
    (comp (ref "C194")
      (value "C-MLCC_0805")
      (footprint "CAP-MLCC_0805")
      (description "贴片电容")
      (fields (field (name "TYPE/VALUE") "100nF/50V") (field (name "FOOTPRINT INDEX") "C_0805"))
      (libsource (lib "我的集成库") (part "C-MLCC_0805"))
    )
    (comp (ref "C195")
      (value "C-MLCC_1210")
      (footprint "CAP-MLCC_1210")
      (description "贴片电容")
      (fields (field (name "TYPE/VALUE") "10uF/50V") (field (name "FOOTPRINT INDEX") "C_1210"))
      (libsource (lib "我的集成库") (part "C-MLCC_1210"))
    )
    (comp (ref "C196")
      (value "C-MLCC_0805")
      (footprint "CAP-MLCC_0805")
      (description "贴片电容")
      (fields (field (name "TYPE/VALUE") "100nF/50V") (field (name "FOOTPRINT INDEX") "C_0805"))
      (libsource (lib "我的集成库") (part "C-MLCC_0805"))
    )
    (comp (ref "C197")
      (value "C-MLCC_0805")
      (footprint "CAP-MLCC_0805")
      (description "贴片电容")
      (fields (field (name "TYPE/VALUE") "100nF/50V") (field (name "FOOTPRINT INDEX") "C_0805"))
      (libsource (lib "我的集成库") (part "C-MLCC_0805"))
    )
    (comp (ref "C198")
      (value "C-MLCC_0805")
      (footprint "CAP-MLCC_0805")
      (description "贴片电容")
      (fields (field (name "TYPE/VALUE") "22nF/50V") (field (name "FOOTPRINT INDEX") "C_0805"))
      (libsource (lib "我的集成库") (part "C-MLCC_0805"))
    )
    (comp (ref "C199")
      (value "C-MLCC_0805")
      (footprint "CAP-MLCC_0805")
      (description "贴片电容")
      (fields (field (name "TYPE/VALUE") "100nF/50V") (field (name "FOOTPRINT INDEX") "C_0805"))
      (libsource (lib "我的集成库") (part "C-MLCC_0805"))
    )
    (comp (ref "C200")
      (value "C-MLCC_0805")
      (footprint "CAP-MLCC_0805")
      (description "贴片电容")
      (fields (field (name "TYPE/VALUE") "2.2uF") (field (name "FOOTPRINT INDEX") "C_0805"))
      (libsource (lib "我的集成库") (part "C-MLCC_0805"))
    )
    (comp (ref "C201")
      (value "C-MLCC_0805")
      (footprint "CAP-MLCC_0805")
      (description "贴片电容")
      (fields (field (name "TYPE/VALUE") "100nF") (field (name "FOOTPRINT INDEX") "C_0805"))
      (libsource (lib "我的集成库") (part "C-MLCC_0805"))
    )
    (comp (ref "C202")
      (value "C-MLCC_0805")
      (footprint "CAP-MLCC_0805")
      (description "贴片电容")
      (fields (field (name "TYPE/VALUE") "470nF") (field (name "FOOTPRINT INDEX") "C_0805"))
      (libsource (lib "我的集成库") (part "C-MLCC_0805"))
    )
    (comp (ref "C203")
      (value "C-MLCC_0805")
      (footprint "CAP-MLCC_0805")
      (description "贴片电容")
      (fields (field (name "TYPE/VALUE") "470pF/100V") (field (name "FOOTPRINT INDEX") "C_0805"))
      (libsource (lib "我的集成库") (part "C-MLCC_0805"))
    )
    (comp (ref "C204")
      (value "C-MLCC_0805")
      (footprint "CAP-MLCC_0805")
      (description "贴片电容")
      (fields (field (name "TYPE/VALUE") "470pF/100V") (field (name "FOOTPRINT INDEX") "C_0805"))
      (libsource (lib "我的集成库") (part "C-MLCC_0805"))
    )
    (comp (ref "C205")
      (value "C-MLCC_0805")
      (footprint "CAP-MLCC_0805")
      (description "贴片电容")
      (fields (field (name "TYPE/VALUE") "470pF/100V") (field (name "FOOTPRINT INDEX") "C_0805"))
      (libsource (lib "我的集成库") (part "C-MLCC_0805"))
    )
    (comp (ref "C206")
      (value "C-MLCC_0805")
      (footprint "CAP-MLCC_0805")
      (description "贴片电容")
      (fields (field (name "TYPE/VALUE") "470pF/100V") (field (name "FOOTPRINT INDEX") "C_0805"))
      (libsource (lib "我的集成库") (part "C-MLCC_0805"))
    )
    (comp (ref "CP1")
      (value "C-TAN_Type_B")
      (footprint "CAP-TAN_TYPE_B")
      (description "贴片钽电容")
      (fields
        (field (name "FOOTPRINT INDEX") "TYPE_B")
        (field (name "SUBCLASS") "TAN")
        (field (name "TYPE/VALUE") "10uF")
      )
      (libsource (lib "我的集成库") (part "C-TAN_Type_B"))
    )
    (comp (ref "D1")
      (value "Diode-Schottky_SMA")
      (footprint "SMA")
      (description "肖特基二极管")
      (fields (field (name "SUBCLASS") "Diode-Schottky") (field (name "TYPE/VALUE") "CDBA240-G"))
      (libsource (lib "我的集成库") (part "Diode-Schottky_SMA"))
    )
    (comp (ref "D2")
      (value "Diode-Schottky_SMA")
      (footprint "SMA")
      (description "肖特基二极管")
      (fields (field (name "SUBCLASS") "Diode-Schottky") (field (name "TYPE/VALUE") "CDBA240-G"))
      (libsource (lib "我的集成库") (part "Diode-Schottky_SMA"))
    )
    (comp (ref "D5")
      (value "Diode-Zener_SOD-123")
      (footprint "SOD-123")
      (description "贴片稳压二极管")
      (fields (field (name "SUBCLASS") "Diode-Zener") (field (name "TYPE/VALUE") "BZT52C12-G"))
      (libsource (lib "我的集成库") (part "Diode-Zener_SOD-123"))
    )
    (comp (ref "D7")
      (value "Diode-Schottky_SMA")
      (footprint "SMA")
      (description "肖特基二极管")
      (fields (field (name "SUBCLASS") "Diode-Schottky") (field (name "TYPE/VALUE") "CDBA240-G"))
      (libsource (lib "我的集成库") (part "Diode-Schottky_SMA"))
    )
    (comp (ref "D8")
      (value "Diode-Schottky_SMA")
      (footprint "SMA")
      (description "肖特基二极管")
      (fields (field (name "SUBCLASS") "Diode-Schottky") (field (name "TYPE/VALUE") "CDBA240-G"))
      (libsource (lib "我的集成库") (part "Diode-Schottky_SMA"))
    )
    (comp (ref "D9")
      (value "Diode-Schottky_SMA")
      (footprint "SMA")
      (description "肖特基二极管")
      (fields (field (name "SUBCLASS") "Diode-Schottky") (field (name "TYPE/VALUE") "CDBA240-G"))
      (libsource (lib "我的集成库") (part "Diode-Schottky_SMA"))
    )
    (comp (ref "D10")
      (value "Diode-Schottky_SMB")
      (footprint "SMB")
      (description "肖特基二极管")
      (fields (field (name "SUBCLASS") "Diode-Schottky") (field (name "TYPE/VALUE") "SS84"))
      (libsource (lib "我的集成库") (part "Diode-Schottky_SMB"))
    )
    (comp (ref "D15")
      (value "Diode-Schottky_SMB")
      (footprint "SMB")
      (description "肖特基二极管")
      (fields (field (name "SUBCLASS") "Diode-Schottky") (field (name "TYPE/VALUE") "SS84"))
      (libsource (lib "我的集成库") (part "Diode-Schottky_SMB"))
    )
    (comp (ref "D16")
      (value "Diode-Schottky_SMB")
      (footprint "SMB")
      (description "肖特基二极管")
      (fields (field (name "SUBCLASS") "Diode-Schottky") (field (name "TYPE/VALUE") "SS84"))
      (libsource (lib "我的集成库") (part "Diode-Schottky_SMB"))
    )
    (comp (ref "IC1")
      (value "MCU-LPC176x")
      (footprint "LQFP-100")
      (description "微控制器")
      (fields (field (name "TYPE") "LPC176x"))
      (libsource (lib "我的集成库") (part "MCU-LPC176x"))
    )
    (comp (ref "IC10")
      (value "LDO-AMS1117-3.3")
      (footprint "SOT-223")
      (description "3.3V稳压芯片")
      (fields (field (name "TYPE") "AMS1117-3.3"))
      (libsource (lib "我的集成库") (part "LDO-AMS1117-3.3"))
    )
    (comp (ref "J111")
      (value "Pin-2.54_1x2")
      (footprint "PIN-SIP-2.54_1X2")
      (description "直插针-2.54")
      (fields (field (name "FOOTPRINT INDEX") "SIP-2.54") (field (name "CLASS") "Pin"))
      (libsource (lib "我的集成库") (part "Pin-2.54_1x2"))
    )
    (comp (ref "J131")
      (value "Pin-2.54_1x2")
      (footprint "PIN-SIP-2.54_1X2")
      (description "直插针-2.54")
      (fields (field (name "FOOTPRINT INDEX") "SIP-2.54") (field (name "CLASS") "Pin"))
      (libsource (lib "我的集成库") (part "Pin-2.54_1x2"))
    )
    (comp (ref "J151")
      (value "Pin-2.54_1x2")
      (footprint "PIN-SIP-2.54_1X2")
      (description "直插针-2.54")
      (fields (field (name "FOOTPRINT INDEX") "SIP-2.54") (field (name "CLASS") "Pin"))
      (libsource (lib "我的集成库") (part "Pin-2.54_1x2"))
    )
    (comp (ref "J171")
      (value "Pin-2.54_1x2")
      (footprint "PIN-SIP-2.54_1X2")
      (description "直插针-2.54")
      (fields (field (name "FOOTPRINT INDEX") "SIP-2.54") (field (name "CLASS") "Pin"))
      (libsource (lib "我的集成库") (part "Pin-2.54_1x2"))
    )
    (comp (ref "J191")
      (value "Pin-2.54_1x2")
      (footprint "PIN-SIP-2.54_1X2")
      (description "直插针-2.54")
      (fields (field (name "FOOTPRINT INDEX") "SIP-2.54") (field (name "CLASS") "Pin"))
      (libsource (lib "我的集成库") (part "Pin-2.54_1x2"))
    )
    (comp (ref "JP1")
      (value "Pin-2.54_2x4")
      (footprint "PIN-DIP-2.54_2X4")
      (description "直插针-2.54")
      (fields (field (name "FOOTPRINT INDEX") "DIP-2.54") (field (name "CLASS") "Pin"))
      (libsource (lib "我的集成库") (part "Pin-2.54_2x4"))
    )
    (comp (ref "JP2")
      (value "Pin-2.54_1x6")
      (footprint "PIN-SIP-2.54_1X6")
      (description "直插针-2.54")
      (fields (field (name "FOOTPRINT INDEX") "SIP-2.54") (field (name "CLASS") "Pin"))
      (libsource (lib "我的集成库") (part "Pin-2.54_1x6"))
    )
    (comp (ref "JP5")
      (value "Pin-2.54_1x4")
      (footprint "PIN-SIP-2.54_1X4")
      (description "直插针-2.54")
      (fields (field (name "FOOTPRINT INDEX") "SIP-2.54") (field (name "CLASS") "Pin"))
      (libsource (lib "我的集成库") (part "Pin-2.54_1x4"))
    )
    (comp (ref "JP7")
      (value "Pin-2.54_1x4")
      (footprint "PIN-SIP-2.54_1X4")
      (description "直插针-2.54")
      (fields (field (name "FOOTPRINT INDEX") "SIP-2.54") (field (name "CLASS") "Pin"))
      (libsource (lib "我的集成库") (part "Pin-2.54_1x4"))
    )
    (comp (ref "JP8")
      (value "Pin-2.54_1x4")
      (footprint "PIN-SIP-2.54_1X4")
      (description "直插针-2.54")
      (fields (field (name "FOOTPRINT INDEX") "SIP-2.54") (field (name "CLASS") "Pin"))
      (libsource (lib "我的集成库") (part "Pin-2.54_1x4"))
    )
    (comp (ref "JP9")
      (value "Pin-2.54_1x4")
      (footprint "PIN-SIP-2.54_1X4")
      (description "直插针-2.54")
      (fields (field (name "FOOTPRINT INDEX") "SIP-2.54") (field (name "CLASS") "Pin"))
      (libsource (lib "我的集成库") (part "Pin-2.54_1x4"))
    )
    (comp (ref "JP12")
      (value "Pin-2.54_1x4")
      (footprint "PIN-SIP-2.54_1X4")
      (description "直插针-2.54")
      (fields (field (name "FOOTPRINT INDEX") "SIP-2.54") (field (name "CLASS") "Pin"))
      (libsource (lib "我的集成库") (part "Pin-2.54_1x4"))
    )
    (comp (ref "JP14")
      (value "HDR-XH2.54A_3P")
      (footprint "HDR-XH2.54A_3P")
      (description "XH2.54直针插座")
      (fields (field (name "FOOTPRINT INDEX") "XH2.54A") (field (name "CLASS") "HDR"))
      (libsource (lib "我的集成库") (part "HDR-XH2.54A_3P"))
    )
    (comp (ref "JP15")
      (value "Pin-2.54_1x4")
      (footprint "PIN-SIP-2.54_1X4")
      (description "直插针-2.54")
      (fields (field (name "FOOTPRINT INDEX") "SIP-2.54") (field (name "CLASS") "Pin"))
      (libsource (lib "我的集成库") (part "Pin-2.54_1x4"))
    )
    (comp (ref "JP16")
      (value "HDR-XH2.54A_3P")
      (footprint "HDR-XH2.54A_3P")
      (description "XH2.54直针插座")
      (fields (field (name "FOOTPRINT INDEX") "XH2.54A") (field (name "CLASS") "HDR"))
      (libsource (lib "我的集成库") (part "HDR-XH2.54A_3P"))
    )
    (comp (ref "JP18")
      (value "Pin-2.54_1x4")
      (footprint "PIN-SIP-2.54_1X4")
      (description "直插针-2.54")
      (fields (field (name "FOOTPRINT INDEX") "SIP-2.54") (field (name "CLASS") "Pin"))
      (libsource (lib "我的集成库") (part "Pin-2.54_1x4"))
    )
    (comp (ref "JP19")
      (value "HDR-XH2.54A_3P")
      (footprint "HDR-XH2.54A_3P")
      (description "XH2.54直针插座")
      (fields (field (name "FOOTPRINT INDEX") "XH2.54A") (field (name "CLASS") "HDR"))
      (libsource (lib "我的集成库") (part "HDR-XH2.54A_3P"))
    )
    (comp (ref "JP21")
      (value "HDR-XH2.54A_3P")
      (footprint "HDR-XH2.54A_3P")
      (description "XH2.54直针插座")
      (fields (field (name "FOOTPRINT INDEX") "XH2.54A") (field (name "CLASS") "HDR"))
      (libsource (lib "我的集成库") (part "HDR-XH2.54A_3P"))
    )
    (comp (ref "JP22")
      (value "HDR-XH2.54A_3P")
      (footprint "HDR-XH2.54A_3P")
      (description "XH2.54直针插座")
      (fields (field (name "FOOTPRINT INDEX") "XH2.54A") (field (name "CLASS") "HDR"))
      (libsource (lib "我的集成库") (part "HDR-XH2.54A_3P"))
    )
    (comp (ref "JP23")
      (value "Pin-2.54_1x2")
      (footprint "PIN-SIP-2.54_1X2")
      (description "直插针-2.54")
      (fields (field (name "FOOTPRINT INDEX") "SIP-2.54") (field (name "CLASS") "Pin"))
      (libsource (lib "我的集成库") (part "Pin-2.54_1x2"))
    )
    (comp (ref "JP24")
      (value "Pin-2.54_1x3")
      (footprint "PIN-SIP-2.54_1X3")
      (description "直插针-2.54")
      (fields (field (name "FOOTPRINT INDEX") "SIP-2.54") (field (name "CLASS") "Pin"))
      (libsource (lib "我的集成库") (part "Pin-2.54_1x3"))
    )
    (comp (ref "JP25")
      (value "Pin-2.54_1x2")
      (footprint "PIN-SIP-2.54_1X2")
      (description "直插针-2.54")
      (fields (field (name "FOOTPRINT INDEX") "SIP-2.54") (field (name "CLASS") "Pin"))
      (libsource (lib "") (part "Pin-2.54_1x2_1"))
    )
    (comp (ref "JP26")
      (value "HDR-XH2.54A_3P")
      (footprint "HDR-XH2.54A_3P")
      (description "XH2.54直针插座")
      (fields (field (name "FOOTPRINT INDEX") "XH2.54A") (field (name "CLASS") "HDR"))
      (libsource (lib "我的集成库") (part "HDR-XH2.54A_3P"))
    )
    (comp (ref "JP27")
      (value "Pin-2.54_1x2")
      (footprint "PIN-SIP-2.54_1X2")
      (description "直插针-2.54")
      (fields (field (name "FOOTPRINT INDEX") "SIP-2.54") (field (name "CLASS") "Pin"))
      (libsource (lib "我的集成库") (part "Pin-2.54_1x2"))
    )
    (comp (ref "JP32")
      (value "Pin-2.54_1x4")
      (footprint "PIN-SIP-2.54_1X4")
      (description "直插针-2.54")
      (fields (field (name "FOOTPRINT INDEX") "SIP-2.54") (field (name "CLASS") "Pin"))
      (libsource (lib "我的集成库") (part "Pin-2.54_1x4"))
    )
    (comp (ref "JP35")
      (value "Pin-2.54_1x2")
      (footprint "PIN-SIP-2.54_1X2")
      (description "直插针-2.54")
      (fields (field (name "FOOTPRINT INDEX") "SIP-2.54") (field (name "CLASS") "Pin"))
      (libsource (lib "我的集成库") (part "Pin-2.54_1x2"))
    )
    (comp (ref "JP36")
      (value "Pin-2.54_1x2")
      (footprint "PIN-SIP-2.54_1X2")
      (description "直插针-2.54")
      (fields (field (name "FOOTPRINT INDEX") "SIP-2.54") (field (name "CLASS") "Pin"))
      (libsource (lib "我的集成库") (part "Pin-2.54_1x2"))
    )
    (comp (ref "L1")
      (value "L_0805")
      (footprint "CAP-MLCC_0805")
      (description "贴片电感")
      (fields (field (name "FOOTPRINT INDEX") "C_0805") (field (name "TYPE/VALUE") "39nH"))
      (libsource (lib "我的集成库") (part "L_0805"))
    )
    (comp (ref "LED1")
      (value "LED_1206")
      (footprint "LED_1206")
      (description "贴片LED")
      (libsource (lib "我的集成库") (part "LED_1206"))
    )
    (comp (ref "LED2")
      (value "LED_1206")
      (footprint "LED_1206")
      (description "贴片LED")
      (libsource (lib "我的集成库") (part "LED_1206"))
    )
    (comp (ref "LED3")
      (value "LED_1206")
      (footprint "LED_1206")
      (description "贴片LED")
      (libsource (lib "我的集成库") (part "LED_1206"))
    )
    (comp (ref "LED4")
      (value "LED_1206")
      (footprint "LED_1206")
      (description "贴片LED")
      (libsource (lib "我的集成库") (part "LED_1206"))
    )
    (comp (ref "LED5")
      (value "LED_1206")
      (footprint "LED_1206")
      (description "贴片LED")
      (libsource (lib "我的集成库") (part "LED_1206"))
    )
    (comp (ref "LED6")
      (value "LED_1206")
      (footprint "LED_1206")
      (description "贴片LED")
      (libsource (lib "我的集成库") (part "LED_1206"))
    )
    (comp (ref "LED7")
      (value "LED_1206")
      (footprint "LED_1206")
      (description "贴片LED")
      (libsource (lib "我的集成库") (part "LED_1206"))
    )
    (comp (ref "LED8")
      (value "LED_1206")
      (footprint "LED_1206")
      (description "贴片LED")
      (libsource (lib "我的集成库") (part "LED_1206"))
    )
    (comp (ref "LED9")
      (value "LED_1206")
      (footprint "LED_1206")
      (description "贴片LED")
      (libsource (lib "我的集成库") (part "LED_1206"))
    )
    (comp (ref "LED10")
      (value "LED_1206")
      (footprint "LED_1206")
      (description "贴片LED")
      (libsource (lib "我的集成库") (part "LED_1206"))
    )
    (comp (ref "LED11")
      (value "LED_1206")
      (footprint "LED_1206")
      (description "贴片LED")
      (libsource (lib "我的集成库") (part "LED_1206"))
    )
    (comp (ref "LED12")
      (value "LED_1206")
      (footprint "LED_1206")
      (description "贴片LED")
      (libsource (lib "我的集成库") (part "LED_1206"))
    )
    (comp (ref "PLAY_LED")
      (value "LED_1206")
      (footprint "LED_1206")
      (description "贴片LED")
      (libsource (lib "我的集成库") (part "LED_1206"))
    )
    (comp (ref "Q1")
      (value "MOSFET-P_SOT-23")
      (footprint "SOT-23")
      (description "场效应管")
      (fields (field (name "SUBCLASS") "MOSFET-P") (field (name "TYPE/VALUE") "AM2343P"))
      (libsource (lib "我的集成库") (part "MOSFET-P_SOT-23"))
    )
    (comp (ref "Q2")
      (value "XTAL_5032")
      (footprint "XTAL_5032")
      (description "贴片晶振")
      (fields (field (name "TYPE/VALUE") "12MHz"))
      (libsource (lib "我的集成库") (part "XTAL_5032"))
    )
    (comp (ref "Q4")
      (value "MOSFET-N_SOT-23")
      (footprint "SOT-23")
      (description "场效应管")
      (fields (field (name "SUBCLASS") "MOSFET-N") (field (name "TYPE/VALUE") "AO3422"))
      (libsource (lib "我的集成库") (part "MOSFET-N_SOT-23"))
    )
    (comp (ref "Q5")
      (value "MOSFET-N_TO-252-3")
      (footprint "TO-252-3")
      (description "功率场效应管")
      (fields (field (name "SUBCLASS") "MOSFET-N") (field (name "TYPE/VALUE") "AOD4126"))
      (libsource (lib "") (part "MOSFET-N_TO-252-3_1"))
    )
    (comp (ref "Q6")
      (value "MOSFET-N_TO-252-3")
      (footprint "TO-252-3")
      (description "功率场效应管")
      (fields (field (name "SUBCLASS") "MOSFET-N") (field (name "TYPE/VALUE") "AOD4126"))
      (libsource (lib "") (part "MOSFET-N_TO-252-3_1"))
    )
    (comp (ref "Q7")
      (value "MOSFET-N_TO-252-3")
      (footprint "TO-252-3")
      (description "功率场效应管")
      (fields (field (name "SUBCLASS") "MOSFET-N") (field (name "TYPE/VALUE") "AOD4126"))
      (libsource (lib "") (part "MOSFET-N_TO-252-3_1"))
    )
    (comp (ref "Q8")
      (value "MOSFET-N_SOT-23")
      (footprint "SOT-23")
      (description "场效应管")
      (fields (field (name "SUBCLASS") "MOSFET-N") (field (name "TYPE/VALUE") "AO3422"))
      (libsource (lib "我的集成库") (part "MOSFET-N_SOT-23"))
    )
    (comp (ref "Q9")
      (value "MOSFET-N_SOT-23")
      (footprint "SOT-23")
      (description "场效应管")
      (fields (field (name "SUBCLASS") "MOSFET-N") (field (name "TYPE/VALUE") "AO3422"))
      (libsource (lib "我的集成库") (part "MOSFET-N_SOT-23"))
    )
    (comp (ref "Q10")
      (value "MOSFET-N_TO-252-3")
      (footprint "TO-252-3")
      (description "功率场效应管")
      (fields (field (name "SUBCLASS") "MOSFET-N") (field (name "TYPE/VALUE") "AOD4126"))
      (libsource (lib "我的集成库") (part "MOSFET-N_TO-252-3"))
    )
    (comp (ref "R1")
      (value "R_0805")
      (footprint "CAP-MLCC_0805")
      (description "贴片电阻")
      (fields (field (name "FOOTPRINT INDEX") "C_0805") (field (name "TYPE/VALUE") "10k"))
      (libsource (lib "我的集成库") (part "R_0805"))
    )
    (comp (ref "R2")
      (value "R_0805")
      (footprint "CAP-MLCC_0805")
      (description "贴片电阻")
      (fields (field (name "FOOTPRINT INDEX") "C_0805") (field (name "TYPE/VALUE") "10k"))
      (libsource (lib "我的集成库") (part "R_0805"))
    )
    (comp (ref "R3")
      (value "R_0805")
      (footprint "CAP-MLCC_0805")
      (description "贴片电阻")
      (fields (field (name "FOOTPRINT INDEX") "C_0805") (field (name "TYPE/VALUE") "10k"))
      (libsource (lib "我的集成库") (part "R_0805"))
    )
    (comp (ref "R5")
      (value "R_0805")
      (footprint "CAP-MLCC_0805")
      (description "贴片电阻")
      (fields (field (name "FOOTPRINT INDEX") "C_0805") (field (name "TYPE/VALUE") "2.2k"))
      (libsource (lib "") (part "R_0805_1"))
    )
    (comp (ref "R6")
      (value "R_0805")
      (footprint "CAP-MLCC_0805")
      (description "贴片电阻")
      (fields (field (name "FOOTPRINT INDEX") "C_0805") (field (name "TYPE/VALUE") "2.2k"))
      (libsource (lib "") (part "R_0805_1"))
    )
    (comp (ref "R7")
      (value "R_0805")
      (footprint "CAP-MLCC_0805")
      (description "贴片电阻")
      (fields (field (name "FOOTPRINT INDEX") "C_0805") (field (name "TYPE/VALUE") "1.5k"))
      (libsource (lib "") (part "R_0805_1"))
    )
    (comp (ref "R8")
      (value "R_0805")
      (footprint "CAP-MLCC_0805")
      (description "贴片电阻")
      (fields (field (name "FOOTPRINT INDEX") "C_0805") (field (name "TYPE/VALUE") "33R±1%"))
      (libsource (lib "") (part "R_0805_1"))
    )
    (comp (ref "R9")
      (value "R_0805")
      (footprint "CAP-MLCC_0805")
      (description "贴片电阻")
      (fields (field (name "FOOTPRINT INDEX") "C_0805") (field (name "TYPE/VALUE") "33R±1%"))
      (libsource (lib "") (part "R_0805_1"))
    )
    (comp (ref "R10")
      (value "R_0805")
      (footprint "CAP-MLCC_0805")
      (description "贴片电阻")
      (fields (field (name "FOOTPRINT INDEX") "C_0805") (field (name "TYPE/VALUE") "4k7"))
      (libsource (lib "") (part "R_0805_1"))
    )
    (comp (ref "R11")
      (value "R_0805")
      (footprint "CAP-MLCC_0805")
      (description "贴片电阻")
      (fields (field (name "FOOTPRINT INDEX") "C_0805") (field (name "TYPE/VALUE") "4k7"))
      (libsource (lib "") (part "R_0805_1"))
    )
    (comp (ref "R12")
      (value "R_0805")
      (footprint "CAP-MLCC_0805")
      (description "贴片电阻")
      (fields (field (name "FOOTPRINT INDEX") "C_0805") (field (name "TYPE/VALUE") "4k7"))
      (libsource (lib "") (part "R_0805_1"))
    )
    (comp (ref "R13")
      (value "R_0805")
      (footprint "CAP-MLCC_0805")
      (description "贴片电阻")
      (fields (field (name "FOOTPRINT INDEX") "C_0805") (field (name "TYPE/VALUE") "4k7"))
      (libsource (lib "") (part "R_0805_1"))
    )
    (comp (ref "R14")
      (value "R_0805")
      (footprint "CAP-MLCC_0805")
      (description "贴片电阻")
      (fields (field (name "FOOTPRINT INDEX") "C_0805") (field (name "TYPE/VALUE") "10k"))
      (libsource (lib "我的集成库") (part "R_0805"))
    )
    (comp (ref "R15")
      (value "R_0805")
      (footprint "CAP-MLCC_0805")
      (description "贴片电阻")
      (fields (field (name "FOOTPRINT INDEX") "C_0805") (field (name "TYPE/VALUE") "10k"))
      (libsource (lib "") (part "R_0805_1"))
    )
    (comp (ref "R16")
      (value "R_0805")
      (footprint "CAP-MLCC_0805")
      (description "贴片电阻")
      (fields (field (name "FOOTPRINT INDEX") "C_0805") (field (name "TYPE/VALUE") "10k"))
      (libsource (lib "") (part "R_0805_1"))
    )
    (comp (ref "R17")
      (value "R_0805")
      (footprint "CAP-MLCC_0805")
      (description "贴片电阻")
      (fields (field (name "FOOTPRINT INDEX") "C_0805") (field (name "TYPE/VALUE") "3k3"))
      (libsource (lib "我的集成库") (part "R_0805"))
    )
    (comp (ref "R35")
      (value "R_0805")
      (footprint "CAP-MLCC_0805")
      (description "贴片电阻")
      (fields (field (name "FOOTPRINT INDEX") "C_0805") (field (name "TYPE/VALUE") "2.2k"))
      (libsource (lib "") (part "R_0805_1"))
    )
    (comp (ref "R36")
      (value "R_0805")
      (footprint "CAP-MLCC_0805")
      (description "贴片电阻")
      (fields (field (name "FOOTPRINT INDEX") "C_0805") (field (name "TYPE/VALUE") "2.2k"))
      (libsource (lib "") (part "R_0805_1"))
    )
    (comp (ref "R65")
      (value "R_0805")
      (footprint "CAP-MLCC_0805")
      (description "贴片电阻")
      (fields (field (name "FOOTPRINT INDEX") "C_0805") (field (name "TYPE/VALUE") "47k"))
      (libsource (lib "") (part "R_0805_1"))
    )
    (comp (ref "R66")
      (value "R_0805")
      (footprint "CAP-MLCC_0805")
      (description "贴片电阻")
      (fields (field (name "FOOTPRINT INDEX") "C_0805") (field (name "TYPE/VALUE") "47k"))
      (libsource (lib "") (part "R_0805_1"))
    )
    (comp (ref "R67")
      (value "R_0805")
      (footprint "CAP-MLCC_0805")
      (description "贴片电阻")
      (fields (field (name "FOOTPRINT INDEX") "C_0805") (field (name "TYPE/VALUE") "47k"))
      (libsource (lib "") (part "R_0805_1"))
    )
    (comp (ref "R68")
      (value "R_0805")
      (footprint "CAP-MLCC_0805")
      (description "贴片电阻")
      (fields (field (name "FOOTPRINT INDEX") "C_0805") (field (name "TYPE/VALUE") "47k"))
      (libsource (lib "") (part "R_0805_1"))
    )
    (comp (ref "R69")
      (value "R_0805")
      (footprint "CAP-MLCC_0805")
      (description "贴片电阻")
      (fields (field (name "FOOTPRINT INDEX") "C_0805") (field (name "TYPE/VALUE") "4R7"))
      (libsource (lib "") (part "R_0805_3"))
    )
    (comp (ref "R70")
      (value "R_0805")
      (footprint "CAP-MLCC_0805")
      (description "贴片电阻")
      (fields (field (name "FOOTPRINT INDEX") "C_0805") (field (name "TYPE/VALUE") "4R7"))
      (libsource (lib "") (part "R_0805_3"))
    )
    (comp (ref "R73")
      (value "R_0805")
      (footprint "CAP-MLCC_0805")
      (description "贴片电阻")
      (fields (field (name "FOOTPRINT INDEX") "C_0805") (field (name "TYPE/VALUE") "10R"))
      (libsource (lib "") (part "R_0805_3"))
    )
    (comp (ref "R74")
      (value "R_0805")
      (footprint "CAP-MLCC_0805")
      (description "贴片电阻")
      (fields (field (name "FOOTPRINT INDEX") "C_0805") (field (name "TYPE/VALUE") "6k8"))
      (libsource (lib "") (part "R_0805_3"))
    )
    (comp (ref "R75")
      (value "R_0805")
      (footprint "CAP-MLCC_0805")
      (description "贴片电阻")
      (fields (field (name "FOOTPRINT INDEX") "C_0805") (field (name "TYPE/VALUE") "10R"))
      (libsource (lib "") (part "R_0805_3"))
    )
    (comp (ref "R76")
      (value "R_0805")
      (footprint "CAP-MLCC_0805")
      (description "贴片电阻")
      (fields (field (name "FOOTPRINT INDEX") "C_0805") (field (name "TYPE/VALUE") "6k8"))
      (libsource (lib "") (part "R_0805_3"))
    )
    (comp (ref "R77")
      (value "R_0805")
      (footprint "CAP-MLCC_0805")
      (description "贴片电阻")
      (fields (field (name "FOOTPRINT INDEX") "C_0805") (field (name "TYPE/VALUE") "4k7"))
      (libsource (lib "") (part "R_0805_2"))
    )
    (comp (ref "R78")
      (value "R_0805")
      (footprint "CAP-MLCC_0805")
      (description "贴片电阻")
      (fields (field (name "FOOTPRINT INDEX") "C_0805") (field (name "TYPE/VALUE") "100k"))
      (libsource (lib "") (part "R_0805_1"))
    )
    (comp (ref "R82")
      (value "R_0805")
      (footprint "CAP-MLCC_0805")
      (description "贴片电阻")
      (fields (field (name "FOOTPRINT INDEX") "C_0805") (field (name "TYPE/VALUE") "10R"))
      (libsource (lib "") (part "R_0805_3"))
    )
    (comp (ref "R83")
      (value "R_0805")
      (footprint "CAP-MLCC_0805")
      (description "贴片电阻")
      (fields (field (name "FOOTPRINT INDEX") "C_0805") (field (name "TYPE/VALUE") "6k8"))
      (libsource (lib "") (part "R_0805_3"))
    )
    (comp (ref "R84")
      (value "R_0805")
      (footprint "CAP-MLCC_0805")
      (description "贴片电阻")
      (fields (field (name "FOOTPRINT INDEX") "C_0805") (field (name "TYPE/VALUE") "47k"))
      (libsource (lib "") (part "R_0805_1"))
    )
    (comp (ref "R85")
      (value "R_0805")
      (footprint "CAP-MLCC_0805")
      (description "贴片电阻")
      (fields (field (name "FOOTPRINT INDEX") "C_0805") (field (name "TYPE/VALUE") "47k"))
      (libsource (lib "") (part "R_0805_1"))
    )
    (comp (ref "R86")
      (value "R_0805")
      (footprint "CAP-MLCC_0805")
      (description "贴片电阻")
      (fields (field (name "FOOTPRINT INDEX") "C_0805") (field (name "TYPE/VALUE") "10k"))
      (libsource (lib "") (part "R_0805_1"))
    )
    (comp (ref "R87")
      (value "R_0805")
      (footprint "CAP-MLCC_0805")
      (description "贴片电阻")
      (fields (field (name "FOOTPRINT INDEX") "C_0805") (field (name "TYPE/VALUE") "0R"))
      (libsource (lib "") (part "R_0805_3"))
    )
    (comp (ref "R88")
      (value "R_0805")
      (footprint "CAP-MLCC_0805")
      (description "贴片电阻")
      (fields (field (name "FOOTPRINT INDEX") "C_0805") (field (name "TYPE/VALUE") "4R7"))
      (libsource (lib "") (part "R_0805_3"))
    )
    (comp (ref "R89")
      (value "R_0805")
      (footprint "CAP-MLCC_0805")
      (description "贴片电阻")
      (fields (field (name "FOOTPRINT INDEX") "C_0805") (field (name "TYPE/VALUE") "10k"))
      (libsource (lib "") (part "R_0805_1"))
    )
    (comp (ref "R90")
      (value "R_0805")
      (footprint "CAP-MLCC_0805")
      (description "贴片电阻")
      (fields (field (name "FOOTPRINT INDEX") "C_0805") (field (name "TYPE/VALUE") "100k"))
      (libsource (lib "") (part "R_0805_1"))
    )
    (comp (ref "R91")
      (value "R_0805")
      (footprint "CAP-MLCC_0805")
      (description "贴片电阻")
      (fields (field (name "FOOTPRINT INDEX") "C_0805") (field (name "TYPE/VALUE") "0R"))
      (libsource (lib "") (part "R_0805_3"))
    )
    (comp (ref "R92")
      (value "R_0805")
      (footprint "CAP-MLCC_0805")
      (description "贴片电阻")
      (fields (field (name "FOOTPRINT INDEX") "C_0805") (field (name "TYPE/VALUE") "5.6k"))
      (libsource (lib "") (part "R_0805_2"))
    )
    (comp (ref "R93")
      (value "R_0805")
      (footprint "CAP-MLCC_0805")
      (description "贴片电阻")
      (fields (field (name "FOOTPRINT INDEX") "C_0805") (field (name "TYPE/VALUE") "1k"))
      (libsource (lib "") (part "R_0805_2"))
    )
    (comp (ref "R94")
      (value "R_0805")
      (footprint "CAP-MLCC_0805")
      (description "贴片电阻")
      (fields (field (name "FOOTPRINT INDEX") "C_0805") (field (name "TYPE/VALUE") "1k"))
      (libsource (lib "") (part "R_0805_2"))
    )
    (comp (ref "R95")
      (value "R_0805")
      (footprint "CAP-MLCC_0805")
      (description "贴片电阻")
      (fields (field (name "FOOTPRINT INDEX") "C_0805") (field (name "TYPE/VALUE") "5.6k"))
      (libsource (lib "") (part "R_0805_2"))
    )
    (comp (ref "R96")
      (value "R_0805")
      (footprint "CAP-MLCC_0805")
      (description "贴片电阻")
      (fields (field (name "FOOTPRINT INDEX") "C_0805") (field (name "TYPE/VALUE") "1k"))
      (libsource (lib "") (part "R_0805_2"))
    )
    (comp (ref "R97")
      (value "R_0805")
      (footprint "CAP-MLCC_0805")
      (description "贴片电阻")
      (fields (field (name "FOOTPRINT INDEX") "C_0805") (field (name "TYPE/VALUE") "5.6k"))
      (libsource (lib "") (part "R_0805_2"))
    )
    (comp (ref "R98")
      (value "R_0805")
      (footprint "CAP-MLCC_0805")
      (description "贴片电阻")
      (fields (field (name "FOOTPRINT INDEX") "C_0805") (field (name "TYPE/VALUE") "1k"))
      (libsource (lib "") (part "R_0805_2"))
    )
    (comp (ref "R99")
      (value "R_0805")
      (footprint "CAP-MLCC_0805")
      (description "贴片电阻")
      (fields (field (name "FOOTPRINT INDEX") "C_0805") (field (name "TYPE/VALUE") "5.6k"))
      (libsource (lib "") (part "R_0805_2"))
    )
    (comp (ref "R100")
      (value "R_0805")
      (footprint "CAP-MLCC_0805")
      (description "贴片电阻")
      (fields (field (name "FOOTPRINT INDEX") "C_0805") (field (name "TYPE/VALUE") "1k"))
      (libsource (lib "") (part "R_0805_2"))
    )
    (comp (ref "R101")
      (value "R_0805")
      (footprint "CAP-MLCC_0805")
      (description "贴片电阻")
      (fields (field (name "FOOTPRINT INDEX") "C_0805") (field (name "TYPE/VALUE") "5.6k"))
      (libsource (lib "") (part "R_0805_2"))
    )
    (comp (ref "R102")
      (value "R_0805")
      (footprint "CAP-MLCC_0805")
      (description "贴片电阻")
      (fields (field (name "FOOTPRINT INDEX") "C_0805") (field (name "TYPE/VALUE") "1k"))
      (libsource (lib "") (part "R_0805_2"))
    )
    (comp (ref "R103")
      (value "R_0805")
      (footprint "CAP-MLCC_0805")
      (description "贴片电阻")
      (fields (field (name "FOOTPRINT INDEX") "C_0805") (field (name "TYPE/VALUE") "5.6k"))
      (libsource (lib "") (part "R_0805_2"))
    )
    (comp (ref "R111")
      (value "R_2512")
      (footprint "RES_2512")
      (description "贴片电阻")
      (fields (field (name "FOOTPRINT INDEX") "R_2512") (field (name "TYPE/VALUE") "R100/1%"))
      (libsource (lib "我的集成库") (part "R_2512"))
    )
    (comp (ref "R113")
      (value "R_2512")
      (footprint "RES_2512")
      (description "贴片电阻")
      (fields (field (name "FOOTPRINT INDEX") "R_2512") (field (name "TYPE/VALUE") "R100/1%"))
      (libsource (lib "我的集成库") (part "R_2512"))
    )
    (comp (ref "R115")
      (value "R_0805")
      (footprint "CAP-MLCC_0805")
      (description "贴片电阻")
      (fields (field (name "FOOTPRINT INDEX") "C_0805") (field (name "TYPE/VALUE") "100k"))
      (libsource (lib "") (part "R_0805_2"))
    )
    (comp (ref "R116")
      (value "R_0805")
      (footprint "CAP-MLCC_0805")
      (description "贴片电阻")
      (fields (field (name "FOOTPRINT INDEX") "C_0805") (field (name "TYPE/VALUE") "2R2"))
      (libsource (lib "我的集成库") (part "R_0805"))
    )
    (comp (ref "R117")
      (value "R_0805")
      (footprint "CAP-MLCC_0805")
      (description "贴片电阻")
      (fields (field (name "FOOTPRINT INDEX") "C_0805") (field (name "TYPE/VALUE") "2k2"))
      (libsource (lib "") (part "R_0805_1"))
    )
    (comp (ref "R118")
      (value "R_0805")
      (footprint "CAP-MLCC_0805")
      (description "贴片电阻")
      (fields (field (name "FOOTPRINT INDEX") "C_0805") (field (name "TYPE/VALUE") "620R"))
      (libsource (lib "") (part "R_0805_1"))
    )
    (comp (ref "R119")
      (value "R_0805")
      (footprint "CAP-MLCC_0805")
      (description "贴片电阻")
      (fields (field (name "FOOTPRINT INDEX") "C_0805") (field (name "TYPE/VALUE") "680R"))
      (libsource (lib "我的集成库") (part "R_0805"))
    )
    (comp (ref "R120")
      (value "R_0805")
      (footprint "CAP-MLCC_0805")
      (description "贴片电阻")
      (fields (field (name "FOOTPRINT INDEX") "C_0805") (field (name "TYPE/VALUE") "22k"))
      (libsource (lib "我的集成库") (part "R_0805"))
    )
    (comp (ref "R121")
      (value "R_0805")
      (footprint "CAP-MLCC_0805")
      (description "贴片电阻")
      (fields (field (name "FOOTPRINT INDEX") "C_0805") (field (name "TYPE/VALUE") "2k2"))
      (libsource (lib "") (part "R_0805_1"))
    )
    (comp (ref "R131")
      (value "R_2512")
      (footprint "RES_2512")
      (description "贴片电阻")
      (fields (field (name "FOOTPRINT INDEX") "R_2512") (field (name "TYPE/VALUE") "R100/1%"))
      (libsource (lib "我的集成库") (part "R_2512"))
    )
    (comp (ref "R133")
      (value "R_2512")
      (footprint "RES_2512")
      (description "贴片电阻")
      (fields (field (name "FOOTPRINT INDEX") "R_2512") (field (name "TYPE/VALUE") "R100/1%"))
      (libsource (lib "我的集成库") (part "R_2512"))
    )
    (comp (ref "R135")
      (value "R_0805")
      (footprint "CAP-MLCC_0805")
      (description "贴片电阻")
      (fields (field (name "FOOTPRINT INDEX") "C_0805") (field (name "TYPE/VALUE") "100k"))
      (libsource (lib "") (part "R_0805_2"))
    )
    (comp (ref "R136")
      (value "R_0805")
      (footprint "CAP-MLCC_0805")
      (description "贴片电阻")
      (fields (field (name "FOOTPRINT INDEX") "C_0805") (field (name "TYPE/VALUE") "2R2"))
      (libsource (lib "我的集成库") (part "R_0805"))
    )
    (comp (ref "R137")
      (value "R_0805")
      (footprint "CAP-MLCC_0805")
      (description "贴片电阻")
      (fields (field (name "FOOTPRINT INDEX") "C_0805") (field (name "TYPE/VALUE") "2k2"))
      (libsource (lib "") (part "R_0805_1"))
    )
    (comp (ref "R138")
      (value "R_0805")
      (footprint "CAP-MLCC_0805")
      (description "贴片电阻")
      (fields (field (name "FOOTPRINT INDEX") "C_0805") (field (name "TYPE/VALUE") "620R"))
      (libsource (lib "") (part "R_0805_1"))
    )
    (comp (ref "R139")
      (value "R_0805")
      (footprint "CAP-MLCC_0805")
      (description "贴片电阻")
      (fields (field (name "FOOTPRINT INDEX") "C_0805") (field (name "TYPE/VALUE") "680R"))
      (libsource (lib "我的集成库") (part "R_0805"))
    )
    (comp (ref "R140")
      (value "R_0805")
      (footprint "CAP-MLCC_0805")
      (description "贴片电阻")
      (fields (field (name "FOOTPRINT INDEX") "C_0805") (field (name "TYPE/VALUE") "22k"))
      (libsource (lib "我的集成库") (part "R_0805"))
    )
    (comp (ref "R141")
      (value "R_0805")
      (footprint "CAP-MLCC_0805")
      (description "贴片电阻")
      (fields (field (name "FOOTPRINT INDEX") "C_0805") (field (name "TYPE/VALUE") "2k2"))
      (libsource (lib "") (part "R_0805_1"))
    )
    (comp (ref "R151")
      (value "R_2512")
      (footprint "RES_2512")
      (description "贴片电阻")
      (fields (field (name "FOOTPRINT INDEX") "R_2512") (field (name "TYPE/VALUE") "R100/1%"))
      (libsource (lib "我的集成库") (part "R_2512"))
    )
    (comp (ref "R153")
      (value "R_2512")
      (footprint "RES_2512")
      (description "贴片电阻")
      (fields (field (name "FOOTPRINT INDEX") "R_2512") (field (name "TYPE/VALUE") "R100/1%"))
      (libsource (lib "我的集成库") (part "R_2512"))
    )
    (comp (ref "R155")
      (value "R_0805")
      (footprint "CAP-MLCC_0805")
      (description "贴片电阻")
      (fields (field (name "FOOTPRINT INDEX") "C_0805") (field (name "TYPE/VALUE") "100k"))
      (libsource (lib "") (part "R_0805_2"))
    )
    (comp (ref "R156")
      (value "R_0805")
      (footprint "CAP-MLCC_0805")
      (description "贴片电阻")
      (fields (field (name "FOOTPRINT INDEX") "C_0805") (field (name "TYPE/VALUE") "2R2"))
      (libsource (lib "我的集成库") (part "R_0805"))
    )
    (comp (ref "R157")
      (value "R_0805")
      (footprint "CAP-MLCC_0805")
      (description "贴片电阻")
      (fields (field (name "FOOTPRINT INDEX") "C_0805") (field (name "TYPE/VALUE") "2k2"))
      (libsource (lib "") (part "R_0805_1"))
    )
    (comp (ref "R158")
      (value "R_0805")
      (footprint "CAP-MLCC_0805")
      (description "贴片电阻")
      (fields (field (name "FOOTPRINT INDEX") "C_0805") (field (name "TYPE/VALUE") "620R"))
      (libsource (lib "") (part "R_0805_1"))
    )
    (comp (ref "R159")
      (value "R_0805")
      (footprint "CAP-MLCC_0805")
      (description "贴片电阻")
      (fields (field (name "FOOTPRINT INDEX") "C_0805") (field (name "TYPE/VALUE") "680R"))
      (libsource (lib "我的集成库") (part "R_0805"))
    )
    (comp (ref "R160")
      (value "R_0805")
      (footprint "CAP-MLCC_0805")
      (description "贴片电阻")
      (fields (field (name "FOOTPRINT INDEX") "C_0805") (field (name "TYPE/VALUE") "22k"))
      (libsource (lib "我的集成库") (part "R_0805"))
    )
    (comp (ref "R161")
      (value "R_0805")
      (footprint "CAP-MLCC_0805")
      (description "贴片电阻")
      (fields (field (name "FOOTPRINT INDEX") "C_0805") (field (name "TYPE/VALUE") "2k2"))
      (libsource (lib "") (part "R_0805_1"))
    )
    (comp (ref "R171")
      (value "R_2512")
      (footprint "RES_2512")
      (description "贴片电阻")
      (fields (field (name "FOOTPRINT INDEX") "R_2512") (field (name "TYPE/VALUE") "R100/1%"))
      (libsource (lib "我的集成库") (part "R_2512"))
    )
    (comp (ref "R173")
      (value "R_2512")
      (footprint "RES_2512")
      (description "贴片电阻")
      (fields (field (name "FOOTPRINT INDEX") "R_2512") (field (name "TYPE/VALUE") "R100/1%"))
      (libsource (lib "我的集成库") (part "R_2512"))
    )
    (comp (ref "R175")
      (value "R_0805")
      (footprint "CAP-MLCC_0805")
      (description "贴片电阻")
      (fields (field (name "FOOTPRINT INDEX") "C_0805") (field (name "TYPE/VALUE") "100k"))
      (libsource (lib "") (part "R_0805_2"))
    )
    (comp (ref "R176")
      (value "R_0805")
      (footprint "CAP-MLCC_0805")
      (description "贴片电阻")
      (fields (field (name "FOOTPRINT INDEX") "C_0805") (field (name "TYPE/VALUE") "2R2"))
      (libsource (lib "我的集成库") (part "R_0805"))
    )
    (comp (ref "R177")
      (value "R_0805")
      (footprint "CAP-MLCC_0805")
      (description "贴片电阻")
      (fields (field (name "FOOTPRINT INDEX") "C_0805") (field (name "TYPE/VALUE") "2k2"))
      (libsource (lib "") (part "R_0805_1"))
    )
    (comp (ref "R178")
      (value "R_0805")
      (footprint "CAP-MLCC_0805")
      (description "贴片电阻")
      (fields (field (name "FOOTPRINT INDEX") "C_0805") (field (name "TYPE/VALUE") "620R"))
      (libsource (lib "") (part "R_0805_1"))
    )
    (comp (ref "R179")
      (value "R_0805")
      (footprint "CAP-MLCC_0805")
      (description "贴片电阻")
      (fields (field (name "FOOTPRINT INDEX") "C_0805") (field (name "TYPE/VALUE") "680R"))
      (libsource (lib "我的集成库") (part "R_0805"))
    )
    (comp (ref "R180")
      (value "R_0805")
      (footprint "CAP-MLCC_0805")
      (description "贴片电阻")
      (fields (field (name "FOOTPRINT INDEX") "C_0805") (field (name "TYPE/VALUE") "22k"))
      (libsource (lib "我的集成库") (part "R_0805"))
    )
    (comp (ref "R181")
      (value "R_0805")
      (footprint "CAP-MLCC_0805")
      (description "贴片电阻")
      (fields (field (name "FOOTPRINT INDEX") "C_0805") (field (name "TYPE/VALUE") "2k2"))
      (libsource (lib "") (part "R_0805_1"))
    )
    (comp (ref "R191")
      (value "R_2512")
      (footprint "RES_2512")
      (description "贴片电阻")
      (fields (field (name "FOOTPRINT INDEX") "R_2512") (field (name "TYPE/VALUE") "R100/1%"))
      (libsource (lib "我的集成库") (part "R_2512"))
    )
    (comp (ref "R193")
      (value "R_2512")
      (footprint "RES_2512")
      (description "贴片电阻")
      (fields (field (name "FOOTPRINT INDEX") "R_2512") (field (name "TYPE/VALUE") "R100/1%"))
      (libsource (lib "我的集成库") (part "R_2512"))
    )
    (comp (ref "R195")
      (value "R_0805")
      (footprint "CAP-MLCC_0805")
      (description "贴片电阻")
      (fields (field (name "FOOTPRINT INDEX") "C_0805") (field (name "TYPE/VALUE") "100k"))
      (libsource (lib "") (part "R_0805_2"))
    )
    (comp (ref "R196")
      (value "R_0805")
      (footprint "CAP-MLCC_0805")
      (description "贴片电阻")
      (fields (field (name "FOOTPRINT INDEX") "C_0805") (field (name "TYPE/VALUE") "2R2"))
      (libsource (lib "我的集成库") (part "R_0805"))
    )
    (comp (ref "R197")
      (value "R_0805")
      (footprint "CAP-MLCC_0805")
      (description "贴片电阻")
      (fields (field (name "FOOTPRINT INDEX") "C_0805") (field (name "TYPE/VALUE") "2k2"))
      (libsource (lib "") (part "R_0805_1"))
    )
    (comp (ref "R198")
      (value "R_0805")
      (footprint "CAP-MLCC_0805")
      (description "贴片电阻")
      (fields (field (name "FOOTPRINT INDEX") "C_0805") (field (name "TYPE/VALUE") "620R"))
      (libsource (lib "") (part "R_0805_1"))
    )
    (comp (ref "R199")
      (value "R_0805")
      (footprint "CAP-MLCC_0805")
      (description "贴片电阻")
      (fields (field (name "FOOTPRINT INDEX") "C_0805") (field (name "TYPE/VALUE") "680R"))
      (libsource (lib "我的集成库") (part "R_0805"))
    )
    (comp (ref "R200")
      (value "R_0805")
      (footprint "CAP-MLCC_0805")
      (description "贴片电阻")
      (fields (field (name "FOOTPRINT INDEX") "C_0805") (field (name "TYPE/VALUE") "22k"))
      (libsource (lib "我的集成库") (part "R_0805"))
    )
    (comp (ref "R201")
      (value "R_0805")
      (footprint "CAP-MLCC_0805")
      (description "贴片电阻")
      (fields (field (name "FOOTPRINT INDEX") "C_0805") (field (name "TYPE/VALUE") "2k2"))
      (libsource (lib "") (part "R_0805_1"))
    )
    (comp (ref "RN1")
      (value "R_0204")
      (footprint "RES_0204")
      (description "贴片晶圆电阻")
      (fields (field (name "FOOTPRINT INDEX") "R_0204") (field (name "TYPE/VALUE") "4.7k±1%"))
      (libsource (lib "我的集成库") (part "R_0204"))
    )
    (comp (ref "RN2")
      (value "R_0204")
      (footprint "RES_0204")
      (description "贴片晶圆电阻")
      (fields (field (name "FOOTPRINT INDEX") "R_0204") (field (name "TYPE/VALUE") "4.7k±1%"))
      (libsource (lib "我的集成库") (part "R_0204"))
    )
    (comp (ref "RN3")
      (value "R_0204")
      (footprint "RES_0204")
      (description "贴片晶圆电阻")
      (fields (field (name "FOOTPRINT INDEX") "R_0204") (field (name "TYPE/VALUE") "4.7k±1%"))
      (libsource (lib "我的集成库") (part "R_0204"))
    )
    (comp (ref "RN4")
      (value "R_0204")
      (footprint "RES_0204")
      (description "贴片晶圆电阻")
      (fields (field (name "FOOTPRINT INDEX") "R_0204") (field (name "TYPE/VALUE") "4.7k±1%"))
      (libsource (lib "我的集成库") (part "R_0204"))
    )
    (comp (ref "RV1")
      (value "R-RV_3296W")
      (footprint "BOURNS 3296W")
      (description "直插可调电阻")
      (fields (field (name "SUBCLASS") "R-RV") (field (name "TYPE/VALUE") "20k"))
      (libsource (lib "我的集成库") (part "R-RV_3296W"))
    )
    (comp (ref "RV2")
      (value "R-RV_3296W")
      (footprint "BOURNS 3296W")
      (description "直插可调电阻")
      (fields (field (name "SUBCLASS") "R-RV") (field (name "TYPE/VALUE") "20k"))
      (libsource (lib "我的集成库") (part "R-RV_3296W"))
    )
    (comp (ref "RV3")
      (value "R-RV_3296W")
      (footprint "BOURNS 3296W")
      (description "直插可调电阻")
      (fields (field (name "SUBCLASS") "R-RV") (field (name "TYPE/VALUE") "20k"))
      (libsource (lib "我的集成库") (part "R-RV_3296W"))
    )
    (comp (ref "RV4")
      (value "R-RV_3296W")
      (footprint "BOURNS 3296W")
      (description "直插可调电阻")
      (fields (field (name "SUBCLASS") "R-RV") (field (name "TYPE/VALUE") "20k"))
      (libsource (lib "我的集成库") (part "R-RV_3296W"))
    )
    (comp (ref "RV5")
      (value "R-RV_3296W")
      (footprint "BOURNS 3296W")
      (description "直插可调电阻")
      (fields (field (name "SUBCLASS") "R-RV") (field (name "TYPE/VALUE") "20k"))
      (libsource (lib "我的集成库") (part "R-RV_3296W"))
    )
    (comp (ref "S1")
      (value "SW_4.5X4.5X1.6")
      (footprint "SW_4.5X4.5X1.6")
      (description "贴片轻触按键")
      (fields (field (name "FOOTPRINT INDEX") "4.5X4.5X1.6") (field (name "CLASS") "SW"))
      (libsource (lib "我的集成库") (part "SW_4.5X4.5X1.6"))
    )
    (comp (ref "S2")
      (value "SW_4.5X4.5X1.6")
      (footprint "SW_4.5X4.5X1.6")
      (description "贴片轻触按键")
      (fields (field (name "FOOTPRINT INDEX") "4.5X4.5X1.6") (field (name "CLASS") "SW"))
      (libsource (lib "我的集成库") (part "SW_4.5X4.5X1.6"))
    )
    (comp (ref "S3")
      (value "SW-DT-SIP_6X6X7")
      (footprint "SW-DT-SIP_6X6X7")
      (description "侧脚6x6x7微动开关")
      (fields (field (name "FOOTPRINT INDEX") "DT-SIP_6X6X7") (field (name "CLASS") "SW"))
      (libsource (lib "我的集成库") (part "SW-DT-SIP_6X6X7"))
    )
    (comp (ref "SL1")
      (value "HDR-XH2.54A_8P")
      (footprint "HDR-XH2.54A_8P")
      (description "XH2.54直针插座")
      (fields (field (name "FOOTPRINT INDEX") "XH2.54A") (field (name "CLASS") "HDR"))
      (libsource (lib "我的集成库") (part "HDR-XH2.54A_8P"))
    )
    (comp (ref "SW1")
      (value "SW_DSHP-1.27_04")
      (footprint "KE DSHP-1.27_04")
      (description "贴片拨码开关")
      (fields
        (field (name "FOOTPRINT INDEX") "DSHP-1.27_04")
        (field (name "CLASS") "SW")
        (field (name "MANUFACTURER") "KE")
      )
      (libsource (lib "我的集成库") (part "SW_DSHP-1.27_04"))
    )
    (comp (ref "SW2")
      (value "SW_DSHP-1.27_04")
      (footprint "KE DSHP-1.27_04")
      (description "贴片拨码开关")
      (fields
        (field (name "FOOTPRINT INDEX") "DSHP-1.27_04")
        (field (name "CLASS") "SW")
        (field (name "MANUFACTURER") "KE")
      )
      (libsource (lib "我的集成库") (part "SW_DSHP-1.27_04"))
    )
    (comp (ref "SW3")
      (value "SW_DSHP-1.27_04")
      (footprint "KE DSHP-1.27_04")
      (description "贴片拨码开关")
      (fields
        (field (name "FOOTPRINT INDEX") "DSHP-1.27_04")
        (field (name "CLASS") "SW")
        (field (name "MANUFACTURER") "KE")
      )
      (libsource (lib "我的集成库") (part "SW_DSHP-1.27_04"))
    )
    (comp (ref "SW4")
      (value "SW_DSHP-1.27_04")
      (footprint "KE DSHP-1.27_04")
      (description "贴片拨码开关")
      (fields
        (field (name "FOOTPRINT INDEX") "DSHP-1.27_04")
        (field (name "CLASS") "SW")
        (field (name "MANUFACTURER") "KE")
      )
      (libsource (lib "我的集成库") (part "SW_DSHP-1.27_04"))
    )
    (comp (ref "SW5")
      (value "SW_DSHP-1.27_04")
      (footprint "KE DSHP-1.27_04")
      (description "贴片拨码开关")
      (fields
        (field (name "FOOTPRINT INDEX") "DSHP-1.27_04")
        (field (name "CLASS") "SW")
        (field (name "MANUFACTURER") "KE")
      )
      (libsource (lib "我的集成库") (part "SW_DSHP-1.27_04"))
    )
    (comp (ref "TVS1")
      (value "Diode-TVS_SOT-143")
      (footprint "SOT-143")
      (description "TVS二极管阵列")
      (fields (field (name "SUBCLASS") "Diode-TVS") (field (name "TYPE/VALUE") "SR05.TC"))
      (libsource (lib "我的集成库") (part "Diode-TVS_SOT-143"))
    )
    (comp (ref "U1")
      (value "Slot-TF Card_SPI Mode")
      (footprint "Slot-TF Card")
      (description "TF卡插槽")
      (fields (field (name "FOOTPRINT INDEX") "TF Card_SPI Mode") (field (name "CLASS") "Slot"))
      (libsource (lib "我的集成库") (part "Slot-TF Card_SPI Mode"))
    )
    (comp (ref "U10")
      (value "IC-N532")
      (footprint "SOT23-5")
      (description "通用功率开关控制器")
      (fields (field (name "TYPE") "N532"))
      (libsource (lib "我的集成库") (part "IC-N532"))
    )
    (comp (ref "U15")
      (value "IC-N532")
      (footprint "SOT23-5")
      (description "通用功率开关控制器")
      (fields (field (name "TYPE") "N532"))
      (libsource (lib "我的集成库") (part "IC-N532"))
    )
    (comp (ref "U16")
      (value "IC-N532")
      (footprint "SOT23-5")
      (description "通用功率开关控制器")
      (fields (field (name "TYPE") "N532"))
      (libsource (lib "我的集成库") (part "IC-N532"))
    )
    (comp (ref "U111")
      (value "IC-TMC2226")
      (footprint "TSSOP-28_173MIL-0.65-EP")
      (description "步进电机控制器")
      (fields (field (name "TYPE") "TMC2226"))
      (libsource (lib "我的集成库") (part "IC-TMC2226"))
    )
    (comp (ref "U131")
      (value "IC-TMC2226")
      (footprint "TSSOP-28_173MIL-0.65-EP")
      (description "步进电机控制器")
      (fields (field (name "TYPE") "TMC2226"))
      (libsource (lib "我的集成库") (part "IC-TMC2226"))
    )
    (comp (ref "U151")
      (value "IC-TMC2226")
      (footprint "TSSOP-28_173MIL-0.65-EP")
      (description "步进电机控制器")
      (fields (field (name "TYPE") "TMC2226"))
      (libsource (lib "我的集成库") (part "IC-TMC2226"))
    )
    (comp (ref "U171")
      (value "IC-TMC2226")
      (footprint "TSSOP-28_173MIL-0.65-EP")
      (description "步进电机控制器")
      (fields (field (name "TYPE") "TMC2226"))
      (libsource (lib "我的集成库") (part "IC-TMC2226"))
    )
    (comp (ref "U191")
      (value "IC-TMC2226")
      (footprint "TSSOP-28_173MIL-0.65-EP")
      (description "步进电机控制器")
      (fields (field (name "TYPE") "TMC2226"))
      (libsource (lib "我的集成库") (part "IC-TMC2226"))
    )
    (comp (ref "X1")
      (value "HDR-XH2.54A_4P")
      (footprint "HDR-XH2.54A_4P")
      (description "XH2.54直针插座")
      (fields (field (name "FOOTPRINT INDEX") "XH2.54A") (field (name "CLASS") "HDR"))
      (libsource (lib "我的集成库") (part "HDR-XH2.54A_4P"))
    )
    (comp (ref "X2")
      (value "HDR-XH2.54A_4P")
      (footprint "HDR-XH2.54A_4P")
      (description "XH2.54直针插座")
      (fields (field (name "FOOTPRINT INDEX") "XH2.54A") (field (name "CLASS") "HDR"))
      (libsource (lib "我的集成库") (part "HDR-XH2.54A_4P"))
    )
    (comp (ref "X3")
      (value "HDR-XH2.54A_4P")
      (footprint "HDR-XH2.54A_4P")
      (description "XH2.54直针插座")
      (fields (field (name "FOOTPRINT INDEX") "XH2.54A") (field (name "CLASS") "HDR"))
      (libsource (lib "我的集成库") (part "HDR-XH2.54A_4P"))
    )
    (comp (ref "X4")
      (value "HDR-XH2.54A_4P")
      (footprint "HDR-XH2.54A_4P")
      (description "XH2.54直针插座")
      (fields (field (name "FOOTPRINT INDEX") "XH2.54A") (field (name "CLASS") "HDR"))
      (libsource (lib "我的集成库") (part "HDR-XH2.54A_4P"))
    )
    (comp (ref "X5")
      (value "HDR-XH2.54A_4P")
      (footprint "HDR-XH2.54A_4P")
      (description "XH2.54直针插座")
      (fields (field (name "FOOTPRINT INDEX") "XH2.54A") (field (name "CLASS") "HDR"))
      (libsource (lib "我的集成库") (part "HDR-XH2.54A_4P"))
    )
    (comp (ref "X7")
      (value "HDR-XH2.54A_2P")
      (footprint "HDR-XH2.54A_2P")
      (description "XH2.54直针插座")
      (fields (field (name "FOOTPRINT INDEX") "XH2.54A") (field (name "CLASS") "HDR"))
      (libsource (lib "我的集成库") (part "HDR-XH2.54A_2P"))
    )
    (comp (ref "X8")
      (value "HDR-XH2.54A_2P")
      (footprint "HDR-XH2.54A_2P")
      (description "XH2.54直针插座")
      (fields (field (name "FOOTPRINT INDEX") "XH2.54A") (field (name "CLASS") "HDR"))
      (libsource (lib "我的集成库") (part "HDR-XH2.54A_2P"))
    )
    (comp (ref "X9")
      (value "HDR-XH2.54A_2P")
      (footprint "HDR-XH2.54A_2P")
      (description "XH2.54直针插座")
      (fields (field (name "FOOTPRINT INDEX") "XH2.54A") (field (name "CLASS") "HDR"))
      (libsource (lib "我的集成库") (part "HDR-XH2.54A_2P"))
    )
    (comp (ref "X10")
      (value "HDR-2EDGRC-3.81_2P")
      (footprint "HDR-2EDGRC-3.81_2P")
      (description "封口弯针插座-3.81")
      (fields (field (name "FOOTPRINT INDEX") "2EDGRC-3.81") (field (name "CLASS") "HDR"))
      (libsource (lib "我的集成库") (part "HDR-2EDGRC-3.81_2P"))
    )
    (comp (ref "X11")
      (value "HDR-KF301-5.0_2P")
      (footprint "HDR-KF301-5.0_2P")
      (description "螺钉式接线端子-5.0直针")
      (fields (field (name "FOOTPRINT INDEX") "KF301-5.0") (field (name "CLASS") "HDR"))
      (libsource (lib "我的集成库") (part "HDR-KF301-5.0_2P"))
    )
    (comp (ref "X12")
      (value "HDR-2EDGRC-3.81_2P")
      (footprint "HDR-2EDGRC-3.81_2P")
      (description "封口弯针插座-3.81")
      (fields (field (name "FOOTPRINT INDEX") "2EDGRC-3.81") (field (name "CLASS") "HDR"))
      (libsource (lib "") (part "HDR-2EDGRC-3.81_2P_1"))
    )
    (comp (ref "X14")
      (value "HDR-Farmertek USB3.0_Type_A")
      (footprint "HDR-FARMERTEK USB3.0_TYPE_A")
      (description "USB3.0母座")
      (fields
        (field (name "FOOTPRINT INDEX") "USB3.0_Type_A")
        (field (name "MANUFACTURER") "Farmertek")
        (field (name "CLASS") "HDR")
      )
      (libsource (lib "我的集成库") (part "HDR-Farmertek USB3.0_Type_A"))
    )
    (comp (ref "X15")
      (value "HDR-2EDGRC-3.81_2P")
      (footprint "HDR-2EDGRC-3.81_2P")
      (description "封口弯针插座-3.81")
      (fields (field (name "FOOTPRINT INDEX") "2EDGRC-3.81") (field (name "CLASS") "HDR"))
      (libsource (lib "我的集成库") (part "HDR-2EDGRC-3.81_2P"))
    )
    (comp (ref "X16")
      (value "HDR-2EDGRC-3.81_2P")
      (footprint "HDR-2EDGRC-3.81_2P")
      (description "封口弯针插座-3.81")
      (fields (field (name "FOOTPRINT INDEX") "2EDGRC-3.81") (field (name "CLASS") "HDR"))
      (libsource (lib "我的集成库") (part "HDR-2EDGRC-3.81_2P"))
    )
  )
  (nets
    (net (code "1") (name "+5V") (class "Default")
      (node (ref "D2") (pin "1") (pinfunction "A_1") (pintype "passive"))
      (node (ref "X12") (pin "1") (pinfunction "1_1") (pintype "passive"))
    )
    (net (code "2") (name "/5VOUT1") (class "Default")
      (node (ref "C120") (pin "1") (pinfunction "1_1") (pintype "passive"))
      (node (ref "C121") (pin "1") (pinfunction "1_1") (pintype "passive"))
      (node (ref "R116") (pin "1") (pinfunction "1_1") (pintype "passive"))
      (node (ref "R117") (pin "2") (pinfunction "2_2") (pintype "passive"))
      (node (ref "SW1") (pin "1") (pinfunction "1_1") (pintype "passive"))
      (node (ref "SW1") (pin "3") (pinfunction "3_3") (pintype "passive"))
      (node (ref "SW1") (pin "5") (pinfunction "5_5") (pintype "passive"))
      (node (ref "SW1") (pin "7") (pinfunction "7_7") (pintype "passive"))
      (node (ref "U111") (pin "11") (pinfunction "5VOUT_11") (pintype "passive"))
      (node (ref "U111") (pin "19") (pinfunction "VCC_IO_19") (pintype "passive"))
    )
    (net (code "3") (name "/5VOUT3") (class "Default")
      (node (ref "C140") (pin "1") (pinfunction "1_1") (pintype "passive"))
      (node (ref "C141") (pin "1") (pinfunction "1_1") (pintype "passive"))
      (node (ref "R136") (pin "1") (pinfunction "1_1") (pintype "passive"))
      (node (ref "R137") (pin "2") (pinfunction "2_2") (pintype "passive"))
      (node (ref "SW2") (pin "1") (pinfunction "1_1") (pintype "passive"))
      (node (ref "SW2") (pin "3") (pinfunction "3_3") (pintype "passive"))
      (node (ref "SW2") (pin "5") (pinfunction "5_5") (pintype "passive"))
      (node (ref "SW2") (pin "7") (pinfunction "7_7") (pintype "passive"))
      (node (ref "U131") (pin "11") (pinfunction "5VOUT_11") (pintype "passive"))
      (node (ref "U131") (pin "19") (pinfunction "VCC_IO_19") (pintype "passive"))
    )
    (net (code "4") (name "/5VOUT5") (class "Default")
      (node (ref "C160") (pin "1") (pinfunction "1_1") (pintype "passive"))
      (node (ref "C161") (pin "1") (pinfunction "1_1") (pintype "passive"))
      (node (ref "R156") (pin "1") (pinfunction "1_1") (pintype "passive"))
      (node (ref "R157") (pin "2") (pinfunction "2_2") (pintype "passive"))
      (node (ref "SW3") (pin "1") (pinfunction "1_1") (pintype "passive"))
      (node (ref "SW3") (pin "3") (pinfunction "3_3") (pintype "passive"))
      (node (ref "SW3") (pin "5") (pinfunction "5_5") (pintype "passive"))
      (node (ref "SW3") (pin "7") (pinfunction "7_7") (pintype "passive"))
      (node (ref "U151") (pin "11") (pinfunction "5VOUT_11") (pintype "passive"))
      (node (ref "U151") (pin "19") (pinfunction "VCC_IO_19") (pintype "passive"))
    )
    (net (code "5") (name "/5VOUT7") (class "Default")
      (node (ref "C180") (pin "1") (pinfunction "1_1") (pintype "passive"))
      (node (ref "C181") (pin "1") (pinfunction "1_1") (pintype "passive"))
      (node (ref "R176") (pin "1") (pinfunction "1_1") (pintype "passive"))
      (node (ref "R177") (pin "2") (pinfunction "2_2") (pintype "passive"))
      (node (ref "SW4") (pin "1") (pinfunction "1_1") (pintype "passive"))
      (node (ref "SW4") (pin "3") (pinfunction "3_3") (pintype "passive"))
      (node (ref "SW4") (pin "5") (pinfunction "5_5") (pintype "passive"))
      (node (ref "SW4") (pin "7") (pinfunction "7_7") (pintype "passive"))
      (node (ref "U171") (pin "11") (pinfunction "5VOUT_11") (pintype "passive"))
      (node (ref "U171") (pin "19") (pinfunction "VCC_IO_19") (pintype "passive"))
    )
    (net (code "6") (name "/5VOUT9") (class "Default")
      (node (ref "C200") (pin "1") (pinfunction "1_1") (pintype "passive"))
      (node (ref "C201") (pin "1") (pinfunction "1_1") (pintype "passive"))
      (node (ref "R196") (pin "1") (pinfunction "1_1") (pintype "passive"))
      (node (ref "R197") (pin "2") (pinfunction "2_2") (pintype "passive"))
      (node (ref "SW5") (pin "1") (pinfunction "1_1") (pintype "passive"))
      (node (ref "SW5") (pin "3") (pinfunction "3_3") (pintype "passive"))
      (node (ref "SW5") (pin "5") (pinfunction "5_5") (pintype "passive"))
      (node (ref "SW5") (pin "7") (pinfunction "7_7") (pintype "passive"))
      (node (ref "U191") (pin "11") (pinfunction "5VOUT_11") (pintype "passive"))
      (node (ref "U191") (pin "19") (pinfunction "VCC_IO_19") (pintype "passive"))
    )
    (net (code "7") (name "/DIR1") (class "Default")
      (node (ref "IC1") (pin "80") (pinfunction "P0[5]/I2SRX_WS/TD2/CAP2[1]_80") (pintype "bidirectional"))
      (node (ref "JP7") (pin "2") (pinfunction "2_2") (pintype "passive"))
      (node (ref "U111") (pin "23") (pinfunction "DIR_23") (pintype "passive"))
    )
    (net (code "8") (name "/DIR2") (class "Default")
      (node (ref "IC1") (pin "49") (pinfunction "P0[11]/RXD2/SCL2/MAT3[1]_49") (pintype "bidirectional"))
      (node (ref "JP9") (pin "2") (pinfunction "2_2") (pintype "passive"))
      (node (ref "U131") (pin "23") (pinfunction "DIR_23") (pintype "passive"))
    )
    (net (code "9") (name "/DIR3") (class "Default")
      (node (ref "IC1") (pin "58") (pinfunction "P0[20]/DTR1/SCL1_58") (pintype "bidirectional"))
      (node (ref "JP12") (pin "2") (pinfunction "2_2") (pintype "passive"))
      (node (ref "U151") (pin "23") (pinfunction "DIR_23") (pintype "passive"))
    )
    (net (code "10") (name "/DIR4") (class "Default")
      (node (ref "IC1") (pin "56") (pinfunction "P0[22]/RTS1/TD1_56") (pintype "bidirectional"))
      (node (ref "JP15") (pin "2") (pinfunction "2_2") (pintype "passive"))
      (node (ref "U171") (pin "23") (pinfunction "DIR_23") (pintype "passive"))
    )
    (net (code "11") (name "/DIR5") (class "Default")
      (node (ref "IC1") (pin "50") (pinfunction "P2[13]/~{EINT3}/I2STX_SDA_50") (pintype "bidirectional"))
      (node (ref "JP18") (pin "2") (pinfunction "2_2") (pintype "passive"))
      (node (ref "U191") (pin "23") (pinfunction "DIR_23") (pintype "passive"))
    )
    (net (code "12") (name "/EN1") (class "Default")
      (node (ref "IC1") (pin "81") (pinfunction "P0[4]/I2SRX_CLK/RD2/CAP2[0]_81") (pintype "bidirectional"))
      (node (ref "JP7") (pin "1") (pinfunction "1_1") (pintype "passive"))
      (node (ref "U111") (pin "5") (pinfunction "ENN_5") (pintype "passive"))
    )
    (net (code "13") (name "/EN2") (class "Default")
      (node (ref "IC1") (pin "48") (pinfunction "P0[10]/TXD2/SDA2/MAT3[0]_48") (pintype "bidirectional"))
      (node (ref "JP9") (pin "1") (pinfunction "1_1") (pintype "passive"))
      (node (ref "U131") (pin "5") (pinfunction "ENN_5") (pintype "passive"))
    )
    (net (code "14") (name "/EN3") (class "Default")
      (node (ref "IC1") (pin "59") (pinfunction "P0[19]/DSR1/SDA1_59") (pintype "bidirectional"))
      (node (ref "JP12") (pin "1") (pinfunction "1_1") (pintype "passive"))
      (node (ref "U151") (pin "5") (pinfunction "ENN_5") (pintype "passive"))
    )
    (net (code "15") (name "/EN4") (class "Default")
      (node (ref "IC1") (pin "57") (pinfunction "P0[21]/RI1/RD1_57") (pintype "bidirectional"))
      (node (ref "JP15") (pin "1") (pinfunction "1_1") (pintype "passive"))
      (node (ref "U171") (pin "5") (pinfunction "ENN_5") (pintype "passive"))
    )
    (net (code "16") (name "/EN5") (class "Default")
      (node (ref "IC1") (pin "85") (pinfunction "P4[29]/TX_MCLK/MAT2[1]/RXD3_85") (pintype "bidirectional"))
      (node (ref "JP18") (pin "1") (pinfunction "1_1") (pintype "passive"))
      (node (ref "U191") (pin "5") (pinfunction "ENN_5") (pintype "passive"))
    )
    (net (code "17") (name "/ENET_CRS") (class "Default")
      (node (ref "IC1") (pin "92") (pinfunction "P1[8]/ENET_CRS_92") (pintype "bidirectional"))
    )
    (net (code "18") (name "/ENET_MDC") (class "Default")
      (node (ref "IC1") (pin "87") (pinfunction "P1[16]/ENET_MDC_87") (pintype "bidirectional"))
    )
    (net (code "19") (name "/ENET_MDIO") (class "Default")
      (node (ref "IC1") (pin "86") (pinfunction "P1[17]/ENET_MDIO_86") (pintype "bidirectional"))
    )
    (net (code "20") (name "/ENET_REF_CLK") (class "Default")
      (node (ref "IC1") (pin "88") (pinfunction "P1[15]/ENET_REF_CLK_88") (pintype "bidirectional"))
    )
    (net (code "21") (name "/ENET_RXD0") (class "Default")
      (node (ref "IC1") (pin "91") (pinfunction "P1[9]/ENET_RXD0_91") (pintype "bidirectional"))
    )
    (net (code "22") (name "/ENET_RXD1") (class "Default")
      (node (ref "IC1") (pin "90") (pinfunction "P1[10]/ENET_RXD1_90") (pintype "bidirectional"))
    )
    (net (code "23") (name "/ENET_RX_ER") (class "Default")
      (node (ref "IC1") (pin "89") (pinfunction "P1[14]/ENET_RX_ER_89") (pintype "bidirectional"))
    )
    (net (code "24") (name "/ENET_TXD0") (class "Default")
      (node (ref "IC1") (pin "95") (pinfunction "P1[0]/ENET_TXD0_95") (pintype "bidirectional"))
    )
    (net (code "25") (name "/ENET_TXD1") (class "Default")
      (node (ref "IC1") (pin "94") (pinfunction "P1[1]/ENET_TXD1_94") (pintype "input"))
    )
    (net (code "26") (name "/ENET_TX_EN") (class "Default")
      (node (ref "IC1") (pin "93") (pinfunction "P1[4]/ENET_TX_EN_93") (pintype "bidirectional"))
    )
    (net (code "27") (name "/ISP_BOOT") (class "Default")
      (node (ref "IC1") (pin "53") (pinfunction "P2[10]/~{EINT0}/NMI_53") (pintype "bidirectional"))
      (node (ref "JP27") (pin "1") (pinfunction "1_1") (pintype "passive"))
      (node (ref "R15") (pin "1") (pinfunction "1_1") (pintype "passive"))
      (node (ref "S2") (pin "2") (pinfunction "2_2") (pintype "passive"))
    )
    (net (code "28") (name "/JTAG_RTCK") (class "Default")
      (node (ref "IC1") (pin "100") (pinfunction "RTCK_100") (pintype "power_in"))
    )
    (net (code "29") (name "/JTAG_TCK") (class "Default")
      (node (ref "IC1") (pin "5") (pinfunction "TCK/SWDCLK_5") (pintype "bidirectional"))
    )
    (net (code "30") (name "/JTAG_TDI") (class "Default")
      (node (ref "IC1") (pin "2") (pinfunction "TDI_2") (pintype "bidirectional"))
    )
    (net (code "31") (name "/JTAG_TDO") (class "Default")
      (node (ref "IC1") (pin "1") (pinfunction "TDO/SWO_1") (pintype "bidirectional"))
    )
    (net (code "32") (name "/JTAG_TMS") (class "Default")
      (node (ref "IC1") (pin "3") (pinfunction "TMS/SWDIO_3") (pintype "bidirectional"))
    )
    (net (code "33") (name "/JTAG_TRST") (class "Default")
      (node (ref "IC1") (pin "4") (pinfunction "~{TRST}_4") (pintype "input"))
    )
    (net (code "34") (name "/LED1") (class "Default")
      (node (ref "IC1") (pin "32") (pinfunction "P1[18]/USB_UP_LED/PWM1[1]/CAP1[0]_32") (pintype "bidirectional"))
      (node (ref "R10") (pin "2") (pinfunction "2_2") (pintype "passive"))
    )
    (net (code "35") (name "/LED2") (class "Default")
      (node (ref "IC1") (pin "33") (pinfunction "P1[19]/MCOA0/USB_PPWR/CAP1[1]_33") (pintype "bidirectional"))
      (node (ref "R11") (pin "2") (pinfunction "2_2") (pintype "passive"))
    )
    (net (code "36") (name "/LED3") (class "Default")
      (node (ref "IC1") (pin "34") (pinfunction "P1[20]/MCI0/PWM1[2]/SCK0_34") (pintype "bidirectional"))
      (node (ref "R12") (pin "2") (pinfunction "2_2") (pintype "passive"))
    )
    (net (code "37") (name "/LED4") (class "Default")
      (node (ref "IC1") (pin "35") (pinfunction "P1[21]/~{MCABORT}/PWM1[3]/SSEL0_35") (pintype "bidirectional"))
      (node (ref "R13") (pin "2") (pinfunction "2_2") (pintype "passive"))
    )
    (net (code "38") (name "/MISO1") (class "Default")
      (node (ref "IC1") (pin "61") (pinfunction "P0[17]/CTS1/MISO0/MISO_61") (pintype "bidirectional"))
      (node (ref "JP2") (pin "3") (pinfunction "3_3") (pintype "passive"))
    )
    (net (code "39") (name "/MOSI1") (class "Default")
      (node (ref "IC1") (pin "60") (pinfunction "P0[18]/DCD1/MOSI0/MOSI_60") (pintype "bidirectional"))
      (node (ref "JP2") (pin "2") (pinfunction "2_2") (pintype "passive"))
    )
    (net (code "40") (name "/MS11") (class "Default")
      (node (ref "SW1") (pin "4") (pinfunction "4_4") (pintype "passive"))
      (node (ref "U111") (pin "12") (pinfunction "MS1_AD0_12") (pintype "passive"))
    )
    (net (code "41") (name "/MS12") (class "Default")
      (node (ref "SW1") (pin "2") (pinfunction "2_2") (pintype "passive"))
      (node (ref "U111") (pin "14") (pinfunction "MS2_AD1_14") (pintype "passive"))
    )
    (net (code "42") (name "/MS31") (class "Default")
      (node (ref "SW2") (pin "4") (pinfunction "4_4") (pintype "passive"))
      (node (ref "U131") (pin "12") (pinfunction "MS1_AD0_12") (pintype "passive"))
    )
    (net (code "43") (name "/MS32") (class "Default")
      (node (ref "SW2") (pin "2") (pinfunction "2_2") (pintype "passive"))
      (node (ref "U131") (pin "14") (pinfunction "MS2_AD1_14") (pintype "passive"))
    )
    (net (code "44") (name "/MS51") (class "Default")
      (node (ref "SW3") (pin "4") (pinfunction "4_4") (pintype "passive"))
      (node (ref "U151") (pin "12") (pinfunction "MS1_AD0_12") (pintype "passive"))
    )
    (net (code "45") (name "/MS52") (class "Default")
      (node (ref "SW3") (pin "2") (pinfunction "2_2") (pintype "passive"))
      (node (ref "U151") (pin "14") (pinfunction "MS2_AD1_14") (pintype "passive"))
    )
    (net (code "46") (name "/MS71") (class "Default")
      (node (ref "SW4") (pin "4") (pinfunction "4_4") (pintype "passive"))
      (node (ref "U171") (pin "12") (pinfunction "MS1_AD0_12") (pintype "passive"))
    )
    (net (code "47") (name "/MS72") (class "Default")
      (node (ref "SW4") (pin "2") (pinfunction "2_2") (pintype "passive"))
      (node (ref "U171") (pin "14") (pinfunction "MS2_AD1_14") (pintype "passive"))
    )
    (net (code "48") (name "/MS91") (class "Default")
      (node (ref "SW5") (pin "4") (pinfunction "4_4") (pintype "passive"))
      (node (ref "U191") (pin "12") (pinfunction "MS1_AD0_12") (pintype "passive"))
    )
    (net (code "49") (name "/MS92") (class "Default")
      (node (ref "SW5") (pin "2") (pinfunction "2_2") (pintype "passive"))
      (node (ref "U191") (pin "14") (pinfunction "MS2_AD1_14") (pintype "passive"))
    )
    (net (code "50") (name "/OA11") (class "Default")
      (node (ref "C125") (pin "1") (pinfunction "1_1") (pintype "passive"))
      (node (ref "U111") (pin "28") (pinfunction "OA1_28") (pintype "passive"))
      (node (ref "X1") (pin "3") (pinfunction "3_3") (pintype "passive"))
    )
    (net (code "51") (name "/OA12") (class "Default")
      (node (ref "C126") (pin "1") (pinfunction "1_1") (pintype "passive"))
      (node (ref "U111") (pin "25") (pinfunction "OA2_25") (pintype "passive"))
      (node (ref "X1") (pin "4") (pinfunction "4_4") (pintype "passive"))
    )
    (net (code "52") (name "/OA31") (class "Default")
      (node (ref "C145") (pin "1") (pinfunction "1_1") (pintype "passive"))
      (node (ref "U131") (pin "28") (pinfunction "OA1_28") (pintype "passive"))
      (node (ref "X2") (pin "3") (pinfunction "3_3") (pintype "passive"))
    )
    (net (code "53") (name "/OA32") (class "Default")
      (node (ref "C146") (pin "1") (pinfunction "1_1") (pintype "passive"))
      (node (ref "U131") (pin "25") (pinfunction "OA2_25") (pintype "passive"))
      (node (ref "X2") (pin "4") (pinfunction "4_4") (pintype "passive"))
    )
    (net (code "54") (name "/OA51") (class "Default")
      (node (ref "C165") (pin "1") (pinfunction "1_1") (pintype "passive"))
      (node (ref "U151") (pin "28") (pinfunction "OA1_28") (pintype "passive"))
      (node (ref "X3") (pin "3") (pinfunction "3_3") (pintype "passive"))
    )
    (net (code "55") (name "/OA52") (class "Default")
      (node (ref "C166") (pin "1") (pinfunction "1_1") (pintype "passive"))
      (node (ref "U151") (pin "25") (pinfunction "OA2_25") (pintype "passive"))
      (node (ref "X3") (pin "4") (pinfunction "4_4") (pintype "passive"))
    )
    (net (code "56") (name "/OA71") (class "Default")
      (node (ref "C185") (pin "1") (pinfunction "1_1") (pintype "passive"))
      (node (ref "U171") (pin "28") (pinfunction "OA1_28") (pintype "passive"))
      (node (ref "X4") (pin "3") (pinfunction "3_3") (pintype "passive"))
    )
    (net (code "57") (name "/OA72") (class "Default")
      (node (ref "C186") (pin "1") (pinfunction "1_1") (pintype "passive"))
      (node (ref "U171") (pin "25") (pinfunction "OA2_25") (pintype "passive"))
      (node (ref "X4") (pin "4") (pinfunction "4_4") (pintype "passive"))
    )
    (net (code "58") (name "/OA91") (class "Default")
      (node (ref "C205") (pin "1") (pinfunction "1_1") (pintype "passive"))
      (node (ref "U191") (pin "28") (pinfunction "OA1_28") (pintype "passive"))
      (node (ref "X5") (pin "3") (pinfunction "3_3") (pintype "passive"))
    )
    (net (code "59") (name "/OA92") (class "Default")
      (node (ref "C206") (pin "1") (pinfunction "1_1") (pintype "passive"))
      (node (ref "U191") (pin "25") (pinfunction "OA2_25") (pintype "passive"))
      (node (ref "X5") (pin "4") (pinfunction "4_4") (pintype "passive"))
    )
    (net (code "60") (name "/OB11") (class "Default")
      (node (ref "C124") (pin "1") (pinfunction "1_1") (pintype "passive"))
      (node (ref "U111") (pin "1") (pinfunction "OB1_1") (pintype "passive"))
      (node (ref "X1") (pin "2") (pinfunction "2_2") (pintype "passive"))
    )
    (net (code "61") (name "/OB12") (class "Default")
      (node (ref "C123") (pin "1") (pinfunction "1_1") (pintype "passive"))
      (node (ref "U111") (pin "4") (pinfunction "OB2_4") (pintype "passive"))
      (node (ref "X1") (pin "1") (pinfunction "1_1") (pintype "passive"))
    )
    (net (code "62") (name "/OB31") (class "Default")
      (node (ref "C144") (pin "1") (pinfunction "1_1") (pintype "passive"))
      (node (ref "U131") (pin "1") (pinfunction "OB1_1") (pintype "passive"))
      (node (ref "X2") (pin "2") (pinfunction "2_2") (pintype "passive"))
    )
    (net (code "63") (name "/OB32") (class "Default")
      (node (ref "C143") (pin "1") (pinfunction "1_1") (pintype "passive"))
      (node (ref "U131") (pin "4") (pinfunction "OB2_4") (pintype "passive"))
      (node (ref "X2") (pin "1") (pinfunction "1_1") (pintype "passive"))
    )
    (net (code "64") (name "/OB51") (class "Default")
      (node (ref "C164") (pin "1") (pinfunction "1_1") (pintype "passive"))
      (node (ref "U151") (pin "1") (pinfunction "OB1_1") (pintype "passive"))
      (node (ref "X3") (pin "2") (pinfunction "2_2") (pintype "passive"))
    )
    (net (code "65") (name "/OB52") (class "Default")
      (node (ref "C163") (pin "1") (pinfunction "1_1") (pintype "passive"))
      (node (ref "U151") (pin "4") (pinfunction "OB2_4") (pintype "passive"))
      (node (ref "X3") (pin "1") (pinfunction "1_1") (pintype "passive"))
    )
    (net (code "66") (name "/OB71") (class "Default")
      (node (ref "C184") (pin "1") (pinfunction "1_1") (pintype "passive"))
      (node (ref "U171") (pin "1") (pinfunction "OB1_1") (pintype "passive"))
      (node (ref "X4") (pin "2") (pinfunction "2_2") (pintype "passive"))
    )
    (net (code "67") (name "/OB72") (class "Default")
      (node (ref "C183") (pin "1") (pinfunction "1_1") (pintype "passive"))
      (node (ref "U171") (pin "4") (pinfunction "OB2_4") (pintype "passive"))
      (node (ref "X4") (pin "1") (pinfunction "1_1") (pintype "passive"))
    )
    (net (code "68") (name "/OB91") (class "Default")
      (node (ref "C204") (pin "1") (pinfunction "1_1") (pintype "passive"))
      (node (ref "U191") (pin "1") (pinfunction "OB1_1") (pintype "passive"))
      (node (ref "X5") (pin "2") (pinfunction "2_2") (pintype "passive"))
    )
    (net (code "69") (name "/OB92") (class "Default")
      (node (ref "C203") (pin "1") (pinfunction "1_1") (pintype "passive"))
      (node (ref "U191") (pin "4") (pinfunction "OB2_4") (pintype "passive"))
      (node (ref "X5") (pin "1") (pinfunction "1_1") (pintype "passive"))
    )
    (net (code "70") (name "/P1_22") (class "Default")
      (node (ref "IC1") (pin "36") (pinfunction "P1[22]/MCOB0/USB_PWRD/MAT1[0]_36") (pintype "bidirectional"))
      (node (ref "R82") (pin "2") (pinfunction "2_2") (pintype "passive"))
    )
    (net (code "71") (name "/P1_23") (class "Default")
      (node (ref "IC1") (pin "37") (pinfunction "P1[23]/MCI1/PWM1[4]/MISO0_37") (pintype "bidirectional"))
      (node (ref "U16") (pin "5") (pinfunction "IN_5") (pintype "passive"))
    )
    (net (code "72") (name "/P1_30") (class "Default")
      (node (ref "IC1") (pin "21") (pinfunction "P1[30]/VBUS/AD0[4]_21") (pintype "bidirectional"))
      (node (ref "JP32") (pin "3") (pinfunction "3_3") (pintype "passive"))
    )
    (net (code "73") (name "/P1_31") (class "Default")
      (node (ref "IC1") (pin "20") (pinfunction "P1[31]/SCK1/AD0[5]_20") (pintype "bidirectional"))
      (node (ref "JP32") (pin "4") (pinfunction "4_4") (pintype "passive"))
    )
    (net (code "74") (name "/P2.6") (class "Default")
      (node (ref "IC1") (pin "67") (pinfunction "P2[6]/PCAP1[0]/RI1/TRACECLK_67") (pintype "bidirectional"))
      (node (ref "R75") (pin "2") (pinfunction "2_2") (pintype "passive"))
    )
    (net (code "75") (name "/P2.7") (class "Default")
      (node (ref "IC1") (pin "66") (pinfunction "P2[7]/RD2/RTS1_66") (pintype "bidirectional"))
      (node (ref "U15") (pin "5") (pinfunction "IN_5") (pintype "passive"))
    )
    (net (code "76") (name "/P2.9") (class "Default")
      (node (ref "IC1") (pin "64") (pinfunction "P2[9]/USB_CONNECT/RXD2_64") (pintype "bidirectional"))
      (node (ref "Q1") (pin "1") (pinfunction "G_1") (pintype "passive"))
    )
    (net (code "77") (name "/PDN_UART1") (class "Default")
      (node (ref "SW1") (pin "6") (pinfunction "6_6") (pintype "passive"))
      (node (ref "U111") (pin "18") (pinfunction "PDN_UART_18") (pintype "passive"))
    )
    (net (code "78") (name "/PDN_UART3") (class "Default")
      (node (ref "SW2") (pin "6") (pinfunction "6_6") (pintype "passive"))
      (node (ref "U131") (pin "18") (pinfunction "PDN_UART_18") (pintype "passive"))
    )
    (net (code "79") (name "/PDN_UART5") (class "Default")
      (node (ref "SW3") (pin "6") (pinfunction "6_6") (pintype "passive"))
      (node (ref "U151") (pin "18") (pinfunction "PDN_UART_18") (pintype "passive"))
    )
    (net (code "80") (name "/PDN_UART7") (class "Default")
      (node (ref "SW4") (pin "6") (pinfunction "6_6") (pintype "passive"))
      (node (ref "U171") (pin "18") (pinfunction "PDN_UART_18") (pintype "passive"))
    )
    (net (code "81") (name "/PDN_UART9") (class "Default")
      (node (ref "SW5") (pin "6") (pinfunction "6_6") (pintype "passive"))
      (node (ref "U191") (pin "18") (pinfunction "PDN_UART_18") (pintype "passive"))
    )
    (net (code "82") (name "/PLAY") (class "Default")
      (node (ref "IC1") (pin "51") (pinfunction "P2[12]/~{EINT2}/I2STX_WS_51") (pintype "bidirectional"))
      (node (ref "JP23") (pin "1") (pinfunction "1_1") (pintype "passive"))
      (node (ref "R16") (pin "1") (pinfunction "1_1") (pintype "passive"))
      (node (ref "S3") (pin "2") (pinfunction "2_2") (pintype "passive"))
    )
    (net (code "83") (name "/PLAY_LED") (class "Default")
      (node (ref "IC1") (pin "82") (pinfunction "P4[28]/RX_MCLK/MAT2[0]/TXD3_82") (pintype "bidirectional"))
      (node (ref "JP24") (pin "1") (pinfunction "1_1") (pintype "passive"))
      (node (ref "PLAY_LED") (pin "2") (pinfunction "K_2") (pintype "passive"))
    )
    (net (code "84") (name "/POT_SCL") (class "Default")
      (node (ref "IC1") (pin "47") (pinfunction "P0[1]/TD1/RXD3/SCL1_47") (pintype "bidirectional"))
      (node (ref "JP8") (pin "3") (pinfunction "3_3") (pintype "passive"))
      (node (ref "R36") (pin "2") (pinfunction "2_2") (pintype "passive"))
    )
    (net (code "85") (name "/POT_SDA") (class "Default")
      (node (ref "IC1") (pin "46") (pinfunction "P0[0]/RD1/TXD3/SDA1_46") (pintype "bidirectional"))
      (node (ref "JP8") (pin "4") (pinfunction "4_4") (pintype "passive"))
      (node (ref "R35") (pin "2") (pinfunction "2_2") (pintype "passive"))
    )
    (net (code "86") (name "/PWM0") (class "Default")
      (node (ref "IC1") (pin "69") (pinfunction "P2[4]/PWM1[5]/DSR1/TRACEDATA[1]_69") (pintype "input"))
      (node (ref "R73") (pin "2") (pinfunction "2_2") (pintype "passive"))
    )
    (net (code "87") (name "/PWM1") (class "Default")
      (node (ref "IC1") (pin "68") (pinfunction "P2[5]/PWM1[6]/DTR1/TRACEDATA[0]_68") (pintype "bidirectional"))
      (node (ref "U10") (pin "5") (pinfunction "IN_5") (pintype "passive"))
    )
    (net (code "88") (name "/RESET") (class "Default")
      (node (ref "IC1") (pin "17") (pinfunction "~{RESET}_17") (pintype "output"))
      (node (ref "JP25") (pin "1") (pinfunction "1_1") (pintype "passive"))
      (node (ref "R14") (pin "2") (pinfunction "2_2") (pintype "passive"))
      (node (ref "S1") (pin "2") (pinfunction "2_2") (pintype "passive"))
    )
    (net (code "89") (name "/RSTOUT") (class "Default")
      (node (ref "IC1") (pin "14") (pinfunction "~{RSTOUT}_14") (pintype "output"))
    )
    (net (code "90") (name "/RX_0") (class "Default")
      (node (ref "IC1") (pin "99") (pinfunction "P0[3]/RXD0/AD0[6]_99") (pintype "bidirectional"))
      (node (ref "JP5") (pin "4") (pinfunction "4_4") (pintype "passive"))
    )
    (net (code "91") (name "/SCK1") (class "Default")
      (node (ref "IC1") (pin "62") (pinfunction "P0[15]/TXD1/SCK0/SCK_62") (pintype "bidirectional"))
      (node (ref "JP2") (pin "4") (pinfunction "4_4") (pintype "passive"))
    )
    (net (code "92") (name "/SCL") (class "Default")
      (node (ref "IC1") (pin "24") (pinfunction "P0[28]/SCL0/USB_SCL_24") (pintype "bidirectional"))
      (node (ref "JP1") (pin "8") (pinfunction "8_8") (pintype "passive"))
      (node (ref "R5") (pin "2") (pinfunction "2_2") (pintype "passive"))
    )
    (net (code "93") (name "/SDA") (class "Default")
      (node (ref "IC1") (pin "25") (pinfunction "P0[27]/SDA0/USB_SDA_25") (pintype "bidirectional"))
      (node (ref "JP1") (pin "6") (pinfunction "6_6") (pintype "passive"))
      (node (ref "R6") (pin "2") (pinfunction "2_2") (pintype "passive"))
    )
    (net (code "94") (name "/SD_CD") (class "Default")
      (node (ref "IC1") (pin "52") (pinfunction "P2[11]/~{EINT1}/I2STX_CLK_52") (pintype "bidirectional"))
      (node (ref "JP1") (pin "7") (pinfunction "7_7") (pintype "passive"))
    )
    (net (code "95") (name "/SD_CS") (class "Default")
      (node (ref "IC1") (pin "79") (pinfunction "P0[6]/I2SRX_SDA/SSEL1/MAT2[0]_79") (pintype "bidirectional"))
      (node (ref "R1") (pin "2") (pinfunction "2_2") (pintype "passive"))
      (node (ref "U1") (pin "2") (pinfunction "CS_2") (pintype "passive"))
    )
    (net (code "96") (name "/SD_IRQ") (class "Default")
      (node (ref "IC1") (pin "27") (pinfunction "P3[25]/MAT0[0]/PWM1[2]_27") (pintype "bidirectional"))
      (node (ref "JP1") (pin "3") (pinfunction "3_3") (pintype "passive"))
    )
    (net (code "97") (name "/SD_MISO") (class "Default")
      (node (ref "IC1") (pin "77") (pinfunction "P0[8]/I2STX_WS/MISO1/MAT2[2]_77") (pintype "bidirectional"))
      (node (ref "R2") (pin "1") (pinfunction "1_1") (pintype "passive"))
      (node (ref "U1") (pin "7") (pinfunction "DO_7") (pintype "passive"))
    )
    (net (code "98") (name "/SD_MOSI") (class "Default")
      (node (ref "IC1") (pin "76") (pinfunction "P0[9]/I2STX_SDA/MOSI1/MAT2[3]_76") (pintype "bidirectional"))
      (node (ref "R3") (pin "2") (pinfunction "2_2") (pintype "passive"))
      (node (ref "U1") (pin "3") (pinfunction "DI_3") (pintype "passive"))
    )
    (net (code "99") (name "/SD_SCK") (class "Default")
      (node (ref "IC1") (pin "78") (pinfunction "P0[7]/I2STX_CLK/SCK1/MAT2[1]_78") (pintype "bidirectional"))
      (node (ref "U1") (pin "5") (pinfunction "SCLK_5") (pintype "passive"))
    )
    (net (code "100") (name "/SD_WP") (class "Default")
      (node (ref "IC1") (pin "26") (pinfunction "P3[26]/STCLK/MAT0[1]/PWM1[3]_26") (pintype "bidirectional"))
      (node (ref "JP1") (pin "5") (pinfunction "5_5") (pintype "passive"))
    )
    (net (code "101") (name "/SPREAD1") (class "Default")
      (node (ref "SW1") (pin "8") (pinfunction "8_8") (pintype "passive"))
      (node (ref "U111") (pin "10") (pinfunction "SPREAD_10") (pintype "passive"))
    )
    (net (code "102") (name "/SPREAD3") (class "Default")
      (node (ref "SW2") (pin "8") (pinfunction "8_8") (pintype "passive"))
      (node (ref "U131") (pin "10") (pinfunction "SPREAD_10") (pintype "passive"))
    )
    (net (code "103") (name "/SPREAD5") (class "Default")
      (node (ref "SW3") (pin "8") (pinfunction "8_8") (pintype "passive"))
      (node (ref "U151") (pin "10") (pinfunction "SPREAD_10") (pintype "passive"))
    )
    (net (code "104") (name "/SPREAD7") (class "Default")
      (node (ref "SW4") (pin "8") (pinfunction "8_8") (pintype "passive"))
      (node (ref "U171") (pin "10") (pinfunction "SPREAD_10") (pintype "passive"))
    )
    (net (code "105") (name "/SPREAD9") (class "Default")
      (node (ref "SW5") (pin "8") (pinfunction "8_8") (pintype "passive"))
      (node (ref "U191") (pin "10") (pinfunction "SPREAD_10") (pintype "passive"))
    )
    (net (code "106") (name "/SSEL1") (class "Default")
      (node (ref "IC1") (pin "63") (pinfunction "P0[16]/RXD1/SSEL0/SSEL_63") (pintype "bidirectional"))
      (node (ref "JP2") (pin "5") (pinfunction "5_5") (pintype "passive"))
    )
    (net (code "107") (name "/STEP1") (class "Default")
      (node (ref "IC1") (pin "75") (pinfunction "P2[0]/PWM1[1]/TXD1_75") (pintype "bidirectional"))
      (node (ref "JP7") (pin "3") (pinfunction "3_3") (pintype "passive"))
      (node (ref "U111") (pin "20") (pinfunction "STEP_20") (pintype "passive"))
    )
    (net (code "108") (name "/STEP2") (class "Default")
      (node (ref "IC1") (pin "74") (pinfunction "P2[1]/PWM1[2]/RXD1_74") (pintype "bidirectional"))
      (node (ref "JP9") (pin "3") (pinfunction "3_3") (pintype "passive"))
      (node (ref "U131") (pin "20") (pinfunction "STEP_20") (pintype "passive"))
    )
    (net (code "109") (name "/STEP3") (class "Default")
      (node (ref "IC1") (pin "73") (pinfunction "P2[2]/PWM1[3]/CTS1/TRACEDATA[3]_73") (pintype "bidirectional"))
      (node (ref "JP12") (pin "3") (pinfunction "3_3") (pintype "passive"))
      (node (ref "U151") (pin "20") (pinfunction "STEP_20") (pintype "passive"))
    )
    (net (code "110") (name "/STEP4") (class "Default")
      (node (ref "IC1") (pin "70") (pinfunction "P2[3]/PWM1[4]/DCD1/TRACEDATA[2]_70") (pintype "bidirectional"))
      (node (ref "JP15") (pin "3") (pinfunction "3_3") (pintype "passive"))
      (node (ref "U171") (pin "20") (pinfunction "STEP_20") (pintype "passive"))
    )
    (net (code "111") (name "/STEP5") (class "Default")
      (node (ref "IC1") (pin "65") (pinfunction "P2[8]/TD2/TXD2_65") (pintype "bidirectional"))
      (node (ref "JP18") (pin "3") (pinfunction "3_3") (pintype "passive"))
      (node (ref "U191") (pin "20") (pinfunction "STEP_20") (pintype "passive"))
    )
    (net (code "112") (name "/TH1") (class "Default")
      (node (ref "C21") (pin "1") (pinfunction "1_1") (pintype "passive"))
      (node (ref "IC1") (pin "9") (pinfunction "P0[23]/AD0[0]/I2SRX_CLK/CAP3[0]_9") (pintype "bidirectional"))
      (node (ref "RN1") (pin "1") (pinfunction "1_1") (pintype "passive"))
      (node (ref "SL1") (pin "2") (pinfunction "2_2") (pintype "passive"))
    )
    (net (code "113") (name "/TH2") (class "Default")
      (node (ref "C22") (pin "1") (pinfunction "1_1") (pintype "passive"))
      (node (ref "IC1") (pin "8") (pinfunction "P0[24]/AD0[1]/I2SRX_WS/CAP3[1]_8") (pintype "bidirectional"))
      (node (ref "RN2") (pin "1") (pinfunction "1_1") (pintype "passive"))
      (node (ref "SL1") (pin "4") (pinfunction "4_4") (pintype "passive"))
    )
    (net (code "114") (name "/TH3") (class "Default")
      (node (ref "C23") (pin "1") (pinfunction "1_1") (pintype "passive"))
      (node (ref "IC1") (pin "7") (pinfunction "P0[25]/AD0[2]/I2SRX_SDA/TXD3_7") (pintype "bidirectional"))
      (node (ref "RN3") (pin "1") (pinfunction "1_1") (pintype "passive"))
      (node (ref "SL1") (pin "6") (pinfunction "6_6") (pintype "passive"))
    )
    (net (code "115") (name "/TH4") (class "Default")
      (node (ref "C24") (pin "1") (pinfunction "1_1") (pintype "passive"))
      (node (ref "IC1") (pin "6") (pinfunction "P0[26]/AD0[3]/AOUT/RXD3_6") (pintype "bidirectional"))
      (node (ref "RN4") (pin "1") (pinfunction "1_1") (pintype "passive"))
      (node (ref "SL1") (pin "8") (pinfunction "8_8") (pintype "passive"))
    )
    (net (code "116") (name "/TX_0") (class "Default")
      (node (ref "IC1") (pin "98") (pinfunction "P0[2]/TXD0/AD0[7]_98") (pintype "bidirectional"))
      (node (ref "JP5") (pin "3") (pinfunction "3_3") (pintype "passive"))
    )
    (net (code "117") (name "/USB_DATA_N") (class "Default")
      (node (ref "C4") (pin "1") (pinfunction "1_1") (pintype "passive"))
      (node (ref "IC1") (pin "30") (pinfunction "P0[30]/USB_D-_30") (pintype "bidirectional"))
      (node (ref "R9") (pin "2") (pinfunction "2_2") (pintype "passive"))
    )
    (net (code "118") (name "/USB_DATA_P") (class "Default")
      (node (ref "C5") (pin "1") (pinfunction "1_1") (pintype "passive"))
      (node (ref "IC1") (pin "29") (pinfunction "P0[29]/USB_D+_29") (pintype "bidirectional"))
      (node (ref "R7") (pin "1") (pinfunction "1_1") (pintype "passive"))
      (node (ref "R8") (pin "2") (pinfunction "2_2") (pintype "passive"))
    )
    (net (code "119") (name "/VREF1") (class "Default")
      (node (ref "R119") (pin "1") (pinfunction "1_1") (pintype "passive"))
      (node (ref "R120") (pin "1") (pinfunction "1_1") (pintype "passive"))
      (node (ref "RV1") (pin "2") (pinfunction "2_2") (pintype "passive"))
      (node (ref "RV1") (pin "3") (pinfunction "3_3") (pintype "passive"))
      (node (ref "U111") (pin "21") (pinfunction "VREF_21") (pintype "passive"))
    )
    (net (code "120") (name "/VREF3") (class "Default")
      (node (ref "R139") (pin "1") (pinfunction "1_1") (pintype "passive"))
      (node (ref "R140") (pin "1") (pinfunction "1_1") (pintype "passive"))
      (node (ref "RV2") (pin "2") (pinfunction "2_2") (pintype "passive"))
      (node (ref "RV2") (pin "3") (pinfunction "3_3") (pintype "passive"))
      (node (ref "U131") (pin "21") (pinfunction "VREF_21") (pintype "passive"))
    )
    (net (code "121") (name "/VREF5") (class "Default")
      (node (ref "R159") (pin "1") (pinfunction "1_1") (pintype "passive"))
      (node (ref "R160") (pin "1") (pinfunction "1_1") (pintype "passive"))
      (node (ref "RV3") (pin "2") (pinfunction "2_2") (pintype "passive"))
      (node (ref "RV3") (pin "3") (pinfunction "3_3") (pintype "passive"))
      (node (ref "U151") (pin "21") (pinfunction "VREF_21") (pintype "passive"))
    )
    (net (code "122") (name "/VREF7") (class "Default")
      (node (ref "R179") (pin "1") (pinfunction "1_1") (pintype "passive"))
      (node (ref "R180") (pin "1") (pinfunction "1_1") (pintype "passive"))
      (node (ref "RV4") (pin "2") (pinfunction "2_2") (pintype "passive"))
      (node (ref "RV4") (pin "3") (pinfunction "3_3") (pintype "passive"))
      (node (ref "U171") (pin "21") (pinfunction "VREF_21") (pintype "passive"))
    )
    (net (code "123") (name "/VREF9") (class "Default")
      (node (ref "R199") (pin "1") (pinfunction "1_1") (pintype "passive"))
      (node (ref "R200") (pin "1") (pinfunction "1_1") (pintype "passive"))
      (node (ref "RV5") (pin "2") (pinfunction "2_2") (pintype "passive"))
      (node (ref "RV5") (pin "3") (pinfunction "3_3") (pintype "passive"))
      (node (ref "U191") (pin "21") (pinfunction "VREF_21") (pintype "passive"))
    )
    (net (code "124") (name "/X_MAX") (class "Default")
      (node (ref "C79") (pin "1") (pinfunction "1_1") (pintype "passive"))
      (node (ref "IC1") (pin "39") (pinfunction "P1[25]/MCOA1/MAT1[1]_39") (pintype "bidirectional"))
      (node (ref "R95") (pin "2") (pinfunction "2_2") (pintype "passive"))
    )
    (net (code "125") (name "/X_MIN") (class "Default")
      (node (ref "C78") (pin "1") (pinfunction "1_1") (pintype "passive"))
      (node (ref "IC1") (pin "38") (pinfunction "P1[24]/MCI2/PWM1[5]/MOSI0_38") (pintype "bidirectional"))
      (node (ref "R92") (pin "2") (pinfunction "2_2") (pintype "passive"))
    )
    (net (code "126") (name "/Y_MAX") (class "Default")
      (node (ref "C81") (pin "1") (pinfunction "1_1") (pintype "passive"))
      (node (ref "IC1") (pin "43") (pinfunction "P1[27]/CLKOUT/~{USB_OVRCR}/CAP0[1]_43") (pintype "bidirectional"))
      (node (ref "R99") (pin "2") (pinfunction "2_2") (pintype "passive"))
    )
    (net (code "127") (name "/Y_MIN") (class "Default")
      (node (ref "C80") (pin "1") (pinfunction "1_1") (pintype "passive"))
      (node (ref "IC1") (pin "40") (pinfunction "P1[26]/MCOB1/PWM1[6]/CAP0[0]_40") (pintype "bidirectional"))
      (node (ref "R97") (pin "2") (pinfunction "2_2") (pintype "passive"))
    )
    (net (code "128") (name "/Z_MAX") (class "Default")
      (node (ref "C83") (pin "1") (pinfunction "1_1") (pintype "passive"))
      (node (ref "IC1") (pin "45") (pinfunction "P1[29]/MCOB2/PCAP1[1]/MAT0[1]_45") (pintype "bidirectional"))
      (node (ref "R103") (pin "2") (pinfunction "2_2") (pintype "passive"))
    )
    (net (code "129") (name "/Z_MIN") (class "Default")
      (node (ref "C82") (pin "1") (pinfunction "1_1") (pintype "passive"))
      (node (ref "IC1") (pin "44") (pinfunction "P1[28]/MCOA2/PCAP1[0]/MAT0[0]_44") (pintype "input"))
      (node (ref "R101") (pin "2") (pinfunction "2_2") (pintype "passive"))
    )
    (net (code "130") (name "3V3") (class "Default")
      (node (ref "C1") (pin "1") (pinfunction "1_1") (pintype "passive"))
      (node (ref "C10") (pin "1") (pinfunction "1_1") (pintype "passive"))
      (node (ref "C11") (pin "1") (pinfunction "1_1") (pintype "passive"))
      (node (ref "C12") (pin "1") (pinfunction "1_1") (pintype "passive"))
      (node (ref "C13") (pin "1") (pinfunction "1_1") (pintype "passive"))
      (node (ref "C14") (pin "1") (pinfunction "1_1") (pintype "passive"))
      (node (ref "C65") (pin "1") (pinfunction "1_1") (pintype "passive"))
      (node (ref "C67") (pin "1") (pinfunction "1_1") (pintype "passive"))
      (node (ref "C7") (pin "1") (pinfunction "1_1") (pintype "passive"))
      (node (ref "C8") (pin "1") (pinfunction "1_1") (pintype "passive"))
      (node (ref "C9") (pin "1") (pinfunction "1_1") (pintype "passive"))
      (node (ref "CP1") (pin "1") (pinfunction "1_1") (pintype "passive"))
      (node (ref "IC1") (pin "19") (pinfunction "VBAT_19") (pintype "power_in"))
      (node (ref "IC1") (pin "28") (pinfunction "VDD(3V3)_28") (pintype "power_in"))
      (node (ref "IC1") (pin "42") (pinfunction "VDD(REG)(3V3)_42") (pintype "power_in"))
      (node (ref "IC1") (pin "54") (pinfunction "VDD(3V3)_54") (pintype "power_in"))
      (node (ref "IC1") (pin "71") (pinfunction "VDD(3V3)_71") (pintype "power_in"))
      (node (ref "IC1") (pin "84") (pinfunction "VDD(REG)(3V3)_84") (pintype "power_in"))
      (node (ref "IC1") (pin "96") (pinfunction "VDD(3V3)_96") (pintype "power_in"))
      (node (ref "IC10") (pin "2") (pinfunction "Vout_2") (pintype "passive"))
      (node (ref "IC10") (pin "4") (pinfunction "Vout_4") (pintype "passive"))
      (node (ref "JP1") (pin "2") (pinfunction "2_2") (pintype "passive"))
      (node (ref "JP2") (pin "1") (pinfunction "1_1") (pintype "passive"))
      (node (ref "JP32") (pin "1") (pinfunction "1_1") (pintype "passive"))
      (node (ref "JP8") (pin "1") (pinfunction "1_1") (pintype "passive"))
      (node (ref "L1") (pin "1") (pinfunction "1_1") (pintype "passive"))
      (node (ref "Q1") (pin "2") (pinfunction "S_2") (pintype "passive"))
      (node (ref "R1") (pin "1") (pinfunction "1_1") (pintype "passive"))
      (node (ref "R14") (pin "1") (pinfunction "1_1") (pintype "passive"))
      (node (ref "R15") (pin "2") (pinfunction "2_2") (pintype "passive"))
      (node (ref "R16") (pin "2") (pinfunction "2_2") (pintype "passive"))
      (node (ref "R17") (pin "1") (pinfunction "1_1") (pintype "passive"))
      (node (ref "R2") (pin "2") (pinfunction "2_2") (pintype "passive"))
      (node (ref "R3") (pin "1") (pinfunction "1_1") (pintype "passive"))
      (node (ref "R35") (pin "1") (pinfunction "1_1") (pintype "passive"))
      (node (ref "R36") (pin "1") (pinfunction "1_1") (pintype "passive"))
      (node (ref "R5") (pin "1") (pinfunction "1_1") (pintype "passive"))
      (node (ref "R6") (pin "1") (pinfunction "1_1") (pintype "passive"))
      (node (ref "R77") (pin "1") (pinfunction "1_1") (pintype "passive"))
      (node (ref "U1") (pin "4") (pinfunction "VDD_4") (pintype "passive"))
    )
    (net (code "131") (name "5V") (class "Default")
      (node (ref "C64") (pin "1") (pinfunction "1_1") (pintype "passive"))
      (node (ref "C84") (pin "1") (pinfunction "1_1") (pintype "passive"))
      (node (ref "C85") (pin "1") (pinfunction "1_1") (pintype "passive"))
      (node (ref "C86") (pin "1") (pinfunction "1_1") (pintype "passive"))
      (node (ref "D1") (pin "2") (pinfunction "K_2") (pintype "passive"))
      (node (ref "D2") (pin "2") (pinfunction "K_2") (pintype "passive"))
      (node (ref "IC10") (pin "3") (pinfunction "Vin_3") (pintype "passive"))
      (node (ref "JP14") (pin "1") (pinfunction "1_1") (pintype "passive"))
      (node (ref "JP16") (pin "1") (pinfunction "1_1") (pintype "passive"))
      (node (ref "JP19") (pin "1") (pinfunction "1_1") (pintype "passive"))
      (node (ref "JP21") (pin "1") (pinfunction "1_1") (pintype "passive"))
      (node (ref "JP22") (pin "1") (pinfunction "1_1") (pintype "passive"))
      (node (ref "JP26") (pin "1") (pinfunction "1_1") (pintype "passive"))
      (node (ref "JP36") (pin "1") (pinfunction "1_1") (pintype "passive"))
      (node (ref "JP5") (pin "1") (pinfunction "1_1") (pintype "passive"))
      (node (ref "R100") (pin "1") (pinfunction "1_1") (pintype "passive"))
      (node (ref "R102") (pin "1") (pinfunction "1_1") (pintype "passive"))
      (node (ref "R86") (pin "2") (pinfunction "2_2") (pintype "passive"))
      (node (ref "R93") (pin "1") (pinfunction "1_1") (pintype "passive"))
      (node (ref "R94") (pin "1") (pinfunction "1_1") (pintype "passive"))
      (node (ref "R96") (pin "1") (pinfunction "1_1") (pintype "passive"))
      (node (ref "R98") (pin "1") (pinfunction "1_1") (pintype "passive"))
      (node (ref "U10") (pin "1") (pinfunction "VCC_1") (pintype "passive"))
      (node (ref "U10") (pin "4") (pinfunction "EN_4") (pintype "passive"))
      (node (ref "U15") (pin "1") (pinfunction "VCC_1") (pintype "passive"))
      (node (ref "U15") (pin "4") (pinfunction "EN_4") (pintype "passive"))
      (node (ref "U16") (pin "1") (pinfunction "VCC_1") (pintype "passive"))
      (node (ref "U16") (pin "4") (pinfunction "EN_4") (pintype "passive"))
    )
    (net (code "132") (name "24V") (class "Default")
      (node (ref "C111") (pin "1") (pinfunction "1_1") (pintype "passive"))
      (node (ref "C112") (pin "2") (pinfunction "2_2") (pintype "passive"))
      (node (ref "C113") (pin "1") (pinfunction "1_1") (pintype "passive"))
      (node (ref "C115") (pin "2") (pinfunction "2_2") (pintype "passive"))
      (node (ref "C116") (pin "1") (pinfunction "1_1") (pintype "passive"))
      (node (ref "C119") (pin "1") (pinfunction "1_1") (pintype "passive"))
      (node (ref "C131") (pin "1") (pinfunction "1_1") (pintype "passive"))
      (node (ref "C132") (pin "2") (pinfunction "2_2") (pintype "passive"))
      (node (ref "C133") (pin "1") (pinfunction "1_1") (pintype "passive"))
      (node (ref "C135") (pin "2") (pinfunction "2_2") (pintype "passive"))
      (node (ref "C136") (pin "1") (pinfunction "1_1") (pintype "passive"))
      (node (ref "C139") (pin "1") (pinfunction "1_1") (pintype "passive"))
      (node (ref "C151") (pin "1") (pinfunction "1_1") (pintype "passive"))
      (node (ref "C152") (pin "2") (pinfunction "2_2") (pintype "passive"))
      (node (ref "C153") (pin "1") (pinfunction "1_1") (pintype "passive"))
      (node (ref "C155") (pin "2") (pinfunction "2_2") (pintype "passive"))
      (node (ref "C156") (pin "1") (pinfunction "1_1") (pintype "passive"))
      (node (ref "C159") (pin "1") (pinfunction "1_1") (pintype "passive"))
      (node (ref "C171") (pin "1") (pinfunction "1_1") (pintype "passive"))
      (node (ref "C172") (pin "2") (pinfunction "2_2") (pintype "passive"))
      (node (ref "C173") (pin "1") (pinfunction "1_1") (pintype "passive"))
      (node (ref "C175") (pin "2") (pinfunction "2_2") (pintype "passive"))
      (node (ref "C176") (pin "1") (pinfunction "1_1") (pintype "passive"))
      (node (ref "C179") (pin "1") (pinfunction "1_1") (pintype "passive"))
      (node (ref "C192") (pin "2") (pinfunction "2_2") (pintype "passive"))
      (node (ref "C193") (pin "1") (pinfunction "1_1") (pintype "passive"))
      (node (ref "C195") (pin "2") (pinfunction "2_2") (pintype "passive"))
      (node (ref "C196") (pin "1") (pinfunction "1_1") (pintype "passive"))
      (node (ref "C199") (pin "1") (pinfunction "1_1") (pintype "passive"))
      (node (ref "D10") (pin "2") (pinfunction "K_2") (pintype "passive"))
      (node (ref "D15") (pin "2") (pinfunction "K_2") (pintype "passive"))
      (node (ref "D16") (pin "2") (pinfunction "K_2") (pintype "passive"))
      (node (ref "D7") (pin "2") (pinfunction "K_2") (pintype "passive"))
      (node (ref "D8") (pin "2") (pinfunction "K_2") (pintype "passive"))
      (node (ref "D9") (pin "2") (pinfunction "K_2") (pintype "passive"))
      (node (ref "R65") (pin "2") (pinfunction "2_2") (pintype "passive"))
      (node (ref "R66") (pin "2") (pinfunction "2_2") (pintype "passive"))
      (node (ref "R67") (pin "2") (pinfunction "2_2") (pintype "passive"))
      (node (ref "R68") (pin "2") (pinfunction "2_2") (pintype "passive"))
      (node (ref "R78") (pin "2") (pinfunction "2_2") (pintype "passive"))
      (node (ref "R84") (pin "2") (pinfunction "2_2") (pintype "passive"))
      (node (ref "R85") (pin "2") (pinfunction "2_2") (pintype "passive"))
      (node (ref "R89") (pin "2") (pinfunction "2_2") (pintype "passive"))
      (node (ref "U111") (pin "26") (pinfunction "VS_26") (pintype "passive"))
      (node (ref "U111") (pin "3") (pinfunction "VS_3") (pintype "passive"))
      (node (ref "U131") (pin "26") (pinfunction "VS_26") (pintype "passive"))
      (node (ref "U131") (pin "3") (pinfunction "VS_3") (pintype "passive"))
      (node (ref "U151") (pin "26") (pinfunction "VS_26") (pintype "passive"))
      (node (ref "U151") (pin "3") (pinfunction "VS_3") (pintype "passive"))
      (node (ref "U171") (pin "26") (pinfunction "VS_26") (pintype "passive"))
      (node (ref "U171") (pin "3") (pinfunction "VS_3") (pintype "passive"))
      (node (ref "U191") (pin "26") (pinfunction "VS_26") (pintype "passive"))
      (node (ref "U191") (pin "3") (pinfunction "VS_3") (pintype "passive"))
      (node (ref "X10") (pin "1") (pinfunction "1_1") (pintype "passive"))
      (node (ref "X11") (pin "1") (pinfunction "1_1") (pintype "passive"))
      (node (ref "X15") (pin "1") (pinfunction "1_1") (pintype "passive"))
      (node (ref "X16") (pin "1") (pinfunction "1_1") (pintype "passive"))
      (node (ref "X7") (pin "1") (pinfunction "1_1") (pintype "passive"))
      (node (ref "X8") (pin "1") (pinfunction "1_1") (pintype "passive"))
      (node (ref "X9") (pin "1") (pinfunction "1_1") (pintype "passive"))
    )
    (net (code "133") (name "AGND") (class "Default")
      (node (ref "C21") (pin "2") (pinfunction "2_2") (pintype "passive"))
      (node (ref "C22") (pin "2") (pinfunction "2_2") (pintype "passive"))
      (node (ref "C23") (pin "2") (pinfunction "2_2") (pintype "passive"))
      (node (ref "C24") (pin "2") (pinfunction "2_2") (pintype "passive"))
      (node (ref "C6") (pin "2") (pinfunction "2_2") (pintype "passive"))
      (node (ref "IC1") (pin "11") (pinfunction "VSSA_11") (pintype "power_in"))
      (node (ref "IC1") (pin "15") (pinfunction "VREFN_15") (pintype "power_in"))
      (node (ref "JP35") (pin "2") (pinfunction "2_2") (pintype "passive"))
      (node (ref "R87") (pin "1") (pinfunction "1_1") (pintype "passive"))
      (node (ref "SL1") (pin "1") (pinfunction "1_1") (pintype "passive"))
      (node (ref "SL1") (pin "3") (pinfunction "3_3") (pintype "passive"))
      (node (ref "SL1") (pin "5") (pinfunction "5_5") (pintype "passive"))
      (node (ref "SL1") (pin "7") (pinfunction "7_7") (pintype "passive"))
    )
    (net (code "134") (name "AVCC") (class "Default")
      (node (ref "C6") (pin "1") (pinfunction "1_1") (pintype "passive"))
      (node (ref "IC1") (pin "10") (pinfunction "VDDA_10") (pintype "power_in"))
      (node (ref "IC1") (pin "12") (pinfunction "VREFP_12") (pintype "power_in"))
      (node (ref "JP35") (pin "1") (pinfunction "1_1") (pintype "passive"))
      (node (ref "L1") (pin "2") (pinfunction "2_2") (pintype "passive"))
      (node (ref "RN1") (pin "2") (pinfunction "2_2") (pintype "passive"))
      (node (ref "RN2") (pin "2") (pinfunction "2_2") (pintype "passive"))
      (node (ref "RN3") (pin "2") (pinfunction "2_2") (pintype "passive"))
      (node (ref "RN4") (pin "2") (pinfunction "2_2") (pintype "passive"))
    )
    (net (code "135") (name "GND") (class "Default")
      (node (ref "C1") (pin "2") (pinfunction "2_2") (pintype "passive"))
      (node (ref "C10") (pin "2") (pinfunction "2_2") (pintype "passive"))
      (node (ref "C11") (pin "2") (pinfunction "2_2") (pintype "passive"))
      (node (ref "C12") (pin "2") (pinfunction "2_2") (pintype "passive"))
      (node (ref "C13") (pin "2") (pinfunction "2_2") (pintype "passive"))
      (node (ref "C14") (pin "2") (pinfunction "2_2") (pintype "passive"))
      (node (ref "C2") (pin "1") (pinfunction "1_1") (pintype "passive"))
      (node (ref "C3") (pin "1") (pinfunction "1_1") (pintype "passive"))
      (node (ref "C4") (pin "2") (pinfunction "2_2") (pintype "passive"))
      (node (ref "C5") (pin "2") (pinfunction "2_2") (pintype "passive"))
      (node (ref "C64") (pin "2") (pinfunction "2_2") (pintype "passive"))
      (node (ref "C65") (pin "2") (pinfunction "2_2") (pintype "passive"))
      (node (ref "C67") (pin "2") (pinfunction "2_2") (pintype "passive"))
      (node (ref "C7") (pin "2") (pinfunction "2_2") (pintype "passive"))
      (node (ref "C78") (pin "2") (pinfunction "2_2") (pintype "passive"))
      (node (ref "C79") (pin "2") (pinfunction "2_2") (pintype "passive"))
      (node (ref "C8") (pin "2") (pinfunction "2_2") (pintype "passive"))
      (node (ref "C80") (pin "2") (pinfunction "2_2") (pintype "passive"))
      (node (ref "C81") (pin "2") (pinfunction "2_2") (pintype "passive"))
      (node (ref "C82") (pin "2") (pinfunction "2_2") (pintype "passive"))
      (node (ref "C83") (pin "2") (pinfunction "2_2") (pintype "passive"))
      (node (ref "C84") (pin "2") (pinfunction "2_2") (pintype "passive"))
      (node (ref "C85") (pin "2") (pinfunction "2_2") (pintype "passive"))
      (node (ref "C86") (pin "2") (pinfunction "2_2") (pintype "passive"))
      (node (ref "C9") (pin "2") (pinfunction "2_2") (pintype "passive"))
      (node (ref "CP1") (pin "2") (pinfunction "2_2") (pintype "passive"))
      (node (ref "IC1") (pin "31") (pinfunction "VSS_31") (pintype "power_in"))
      (node (ref "IC1") (pin "41") (pinfunction "VSS_41") (pintype "power_in"))
      (node (ref "IC1") (pin "55") (pinfunction "VSS_55") (pintype "power_in"))
      (node (ref "IC1") (pin "72") (pinfunction "VSS_72") (pintype "power_in"))
      (node (ref "IC1") (pin "83") (pinfunction "VSS_83") (pintype "power_in"))
      (node (ref "IC1") (pin "97") (pinfunction "VSS_97") (pintype "power_in"))
      (node (ref "IC10") (pin "1") (pinfunction "GND_1") (pintype "passive"))
      (node (ref "JP1") (pin "1") (pinfunction "1_1") (pintype "passive"))
      (node (ref "JP1") (pin "4") (pinfunction "4_4") (pintype "passive"))
      (node (ref "JP12") (pin "4") (pinfunction "4_4") (pintype "passive"))
      (node (ref "JP14") (pin "2") (pinfunction "2_2") (pintype "passive"))
      (node (ref "JP15") (pin "4") (pinfunction "4_4") (pintype "passive"))
      (node (ref "JP16") (pin "2") (pinfunction "2_2") (pintype "passive"))
      (node (ref "JP18") (pin "4") (pinfunction "4_4") (pintype "passive"))
      (node (ref "JP19") (pin "2") (pinfunction "2_2") (pintype "passive"))
      (node (ref "JP2") (pin "6") (pinfunction "6_6") (pintype "passive"))
      (node (ref "JP21") (pin "2") (pinfunction "2_2") (pintype "passive"))
      (node (ref "JP22") (pin "2") (pinfunction "2_2") (pintype "passive"))
      (node (ref "JP23") (pin "2") (pinfunction "2_2") (pintype "passive"))
      (node (ref "JP25") (pin "2") (pinfunction "2_2") (pintype "passive"))
      (node (ref "JP26") (pin "2") (pinfunction "2_2") (pintype "passive"))
      (node (ref "JP27") (pin "2") (pinfunction "2_2") (pintype "passive"))
      (node (ref "JP32") (pin "2") (pinfunction "2_2") (pintype "passive"))
      (node (ref "JP36") (pin "2") (pinfunction "2_2") (pintype "passive"))
      (node (ref "JP5") (pin "2") (pinfunction "2_2") (pintype "passive"))
      (node (ref "JP7") (pin "4") (pinfunction "4_4") (pintype "passive"))
      (node (ref "JP8") (pin "2") (pinfunction "2_2") (pintype "passive"))
      (node (ref "JP9") (pin "4") (pinfunction "4_4") (pintype "passive"))
      (node (ref "LED1") (pin "2") (pinfunction "K_2") (pintype "passive"))
      (node (ref "LED2") (pin "2") (pinfunction "K_2") (pintype "passive"))
      (node (ref "LED3") (pin "2") (pinfunction "K_2") (pintype "passive"))
      (node (ref "LED4") (pin "2") (pinfunction "K_2") (pintype "passive"))
      (node (ref "LED9") (pin "2") (pinfunction "K_2") (pintype "passive"))
      (node (ref "R87") (pin "2") (pinfunction "2_2") (pintype "passive"))
      (node (ref "R91") (pin "2") (pinfunction "2_2") (pintype "passive"))
      (node (ref "S1") (pin "1") (pinfunction "1_1") (pintype "passive"))
      (node (ref "S2") (pin "1") (pinfunction "1_1") (pintype "passive"))
      (node (ref "S3") (pin "1") (pinfunction "1_1") (pintype "passive"))
      (node (ref "TVS1") (pin "1") (pintype "passive"))
      (node (ref "U1") (pin "10") (pinfunction "SHIELD_10") (pintype "passive"))
      (node (ref "U1") (pin "6") (pinfunction "VSS_6") (pintype "passive"))
      (node (ref "U1") (pin "9") (pinfunction "Cd_9") (pintype "passive"))
      (node (ref "U10") (pin "2") (pinfunction "GND_2") (pintype "passive"))
      (node (ref "U15") (pin "2") (pinfunction "GND_2") (pintype "passive"))
      (node (ref "U16") (pin "2") (pinfunction "GND_2") (pintype "passive"))
      (node (ref "X12") (pin "2") (pinfunction "2_2") (pintype "passive"))
      (node (ref "X14") (pin "0") (pinfunction "GND_0") (pintype "passive"))
      (node (ref "X14") (pin "4") (pinfunction "GND_4") (pintype "passive"))
    )
    (net (code "136") (name "Net-(C122-Pad1)") (class "Default")
      (node (ref "C122") (pin "1") (pinfunction "1_1") (pintype "passive"))
      (node (ref "R116") (pin "2") (pinfunction "2_2") (pintype "passive"))
    )
    (net (code "137") (name "Net-(C142-Pad1)") (class "Default")
      (node (ref "C142") (pin "1") (pinfunction "1_1") (pintype "passive"))
      (node (ref "R136") (pin "2") (pinfunction "2_2") (pintype "passive"))
    )
    (net (code "138") (name "Net-(C162-Pad1)") (class "Default")
      (node (ref "C162") (pin "1") (pinfunction "1_1") (pintype "passive"))
      (node (ref "R156") (pin "2") (pinfunction "2_2") (pintype "passive"))
    )
    (net (code "139") (name "Net-(C182-Pad1)") (class "Default")
      (node (ref "C182") (pin "1") (pinfunction "1_1") (pintype "passive"))
      (node (ref "R176") (pin "2") (pinfunction "2_2") (pintype "passive"))
    )
    (net (code "140") (name "Net-(C202-Pad1)") (class "Default")
      (node (ref "C202") (pin "1") (pinfunction "1_1") (pintype "passive"))
      (node (ref "R196") (pin "2") (pinfunction "2_2") (pintype "passive"))
    )
    (net (code "141") (name "Net-(D5-K)") (class "Default")
      (node (ref "C63") (pin "2") (pinfunction "2_2") (pintype "passive"))
      (node (ref "D5") (pin "2") (pinfunction "K_2") (pintype "passive"))
      (node (ref "Q10") (pin "1") (pinfunction "G_1") (pintype "passive"))
      (node (ref "R89") (pin "1") (pinfunction "1_1") (pintype "passive"))
      (node (ref "R90") (pin "2") (pinfunction "2_2") (pintype "passive"))
    )
    (net (code "142") (name "Net-(D7-A)") (class "Default")
      (node (ref "D7") (pin "1") (pinfunction "A_1") (pintype "passive"))
      (node (ref "LED5") (pin "2") (pinfunction "K_2") (pintype "passive"))
      (node (ref "Q8") (pin "3") (pinfunction "D_3") (pintype "passive"))
      (node (ref "X7") (pin "2") (pinfunction "2_2") (pintype "passive"))
    )
    (net (code "143") (name "Net-(D8-A)") (class "Default")
      (node (ref "D8") (pin "1") (pinfunction "A_1") (pintype "passive"))
      (node (ref "LED6") (pin "2") (pinfunction "K_2") (pintype "passive"))
      (node (ref "Q9") (pin "3") (pinfunction "D_3") (pintype "passive"))
      (node (ref "X8") (pin "2") (pinfunction "2_2") (pintype "passive"))
    )
    (net (code "144") (name "Net-(D9-A)") (class "Default")
      (node (ref "D9") (pin "1") (pinfunction "A_1") (pintype "passive"))
      (node (ref "LED11") (pin "2") (pinfunction "K_2") (pintype "passive"))
      (node (ref "Q4") (pin "3") (pinfunction "D_3") (pintype "passive"))
      (node (ref "X9") (pin "2") (pinfunction "2_2") (pintype "passive"))
    )
    (net (code "145") (name "Net-(D10-A)") (class "Default")
      (node (ref "D10") (pin "1") (pinfunction "A_1") (pintype "passive"))
      (node (ref "LED7") (pin "2") (pinfunction "K_2") (pintype "passive"))
      (node (ref "Q6") (pin "4") (pinfunction "D_4") (pintype "passive"))
      (node (ref "X10") (pin "2") (pinfunction "2_2") (pintype "passive"))
    )
    (net (code "146") (name "Net-(D15-A)") (class "Default")
      (node (ref "D15") (pin "1") (pinfunction "A_1") (pintype "passive"))
      (node (ref "LED8") (pin "2") (pinfunction "K_2") (pintype "passive"))
      (node (ref "Q7") (pin "4") (pinfunction "D_4") (pintype "passive"))
      (node (ref "X15") (pin "2") (pinfunction "2_2") (pintype "passive"))
    )
    (net (code "147") (name "Net-(D16-A)") (class "Default")
      (node (ref "D16") (pin "1") (pinfunction "A_1") (pintype "passive"))
      (node (ref "LED12") (pin "2") (pinfunction "K_2") (pintype "passive"))
      (node (ref "Q5") (pin "4") (pinfunction "D_4") (pintype "passive"))
      (node (ref "X16") (pin "2") (pinfunction "2_2") (pintype "passive"))
    )
    (net (code "148") (name "Net-(IC1-XTAL1)") (class "Default")
      (node (ref "C2") (pin "2") (pinfunction "2_2") (pintype "passive"))
      (node (ref "IC1") (pin "22") (pinfunction "XTAL1_22") (pintype "input"))
      (node (ref "Q2") (pin "2") (pinfunction "OSC2_2") (pintype "passive"))
    )
    (net (code "149") (name "Net-(IC1-XTAL2)") (class "Default")
      (node (ref "C3") (pin "2") (pinfunction "2_2") (pintype "passive"))
      (node (ref "IC1") (pin "23") (pinfunction "XTAL2_23") (pintype "input"))
      (node (ref "Q2") (pin "1") (pinfunction "OSC1_1") (pintype "passive"))
    )
    (net (code "150") (name "Net-(J111-Pad1)") (class "Default")
      (node (ref "J111") (pin "1") (pinfunction "1_1") (pintype "passive"))
      (node (ref "R119") (pin "2") (pinfunction "2_2") (pintype "passive"))
      (node (ref "R120") (pin "2") (pinfunction "2_2") (pintype "passive"))
      (node (ref "R121") (pin "2") (pinfunction "2_2") (pintype "passive"))
    )
    (net (code "151") (name "Net-(J131-Pad1)") (class "Default")
      (node (ref "J131") (pin "1") (pinfunction "1_1") (pintype "passive"))
      (node (ref "R139") (pin "2") (pinfunction "2_2") (pintype "passive"))
      (node (ref "R140") (pin "2") (pinfunction "2_2") (pintype "passive"))
      (node (ref "R141") (pin "2") (pinfunction "2_2") (pintype "passive"))
    )
    (net (code "152") (name "Net-(J151-Pad1)") (class "Default")
      (node (ref "J151") (pin "1") (pinfunction "1_1") (pintype "passive"))
      (node (ref "R159") (pin "2") (pinfunction "2_2") (pintype "passive"))
      (node (ref "R160") (pin "2") (pinfunction "2_2") (pintype "passive"))
      (node (ref "R161") (pin "2") (pinfunction "2_2") (pintype "passive"))
    )
    (net (code "153") (name "Net-(J171-Pad1)") (class "Default")
      (node (ref "J171") (pin "1") (pinfunction "1_1") (pintype "passive"))
      (node (ref "R179") (pin "2") (pinfunction "2_2") (pintype "passive"))
      (node (ref "R180") (pin "2") (pinfunction "2_2") (pintype "passive"))
      (node (ref "R181") (pin "2") (pinfunction "2_2") (pintype "passive"))
    )
    (net (code "154") (name "Net-(J191-Pad1)") (class "Default")
      (node (ref "J191") (pin "1") (pinfunction "1_1") (pintype "passive"))
      (node (ref "R199") (pin "2") (pinfunction "2_2") (pintype "passive"))
      (node (ref "R200") (pin "2") (pinfunction "2_2") (pintype "passive"))
      (node (ref "R201") (pin "2") (pinfunction "2_2") (pintype "passive"))
    )
    (net (code "155") (name "Net-(JP14-Pad3)") (class "Default")
      (node (ref "JP14") (pin "3") (pinfunction "3_3") (pintype "passive"))
      (node (ref "R94") (pin "2") (pinfunction "2_2") (pintype "passive"))
      (node (ref "R95") (pin "1") (pinfunction "1_1") (pintype "passive"))
    )
    (net (code "156") (name "Net-(JP16-Pad3)") (class "Default")
      (node (ref "JP16") (pin "3") (pinfunction "3_3") (pintype "passive"))
      (node (ref "R96") (pin "2") (pinfunction "2_2") (pintype "passive"))
      (node (ref "R97") (pin "1") (pinfunction "1_1") (pintype "passive"))
    )
    (net (code "157") (name "Net-(JP19-Pad3)") (class "Default")
      (node (ref "JP19") (pin "3") (pinfunction "3_3") (pintype "passive"))
      (node (ref "R98") (pin "2") (pinfunction "2_2") (pintype "passive"))
      (node (ref "R99") (pin "1") (pinfunction "1_1") (pintype "passive"))
    )
    (net (code "158") (name "Net-(JP21-Pad3)") (class "Default")
      (node (ref "JP21") (pin "3") (pinfunction "3_3") (pintype "passive"))
      (node (ref "R100") (pin "2") (pinfunction "2_2") (pintype "passive"))
      (node (ref "R101") (pin "1") (pinfunction "1_1") (pintype "passive"))
    )
    (net (code "159") (name "Net-(JP22-Pad3)") (class "Default")
      (node (ref "JP22") (pin "3") (pinfunction "3_3") (pintype "passive"))
      (node (ref "R102") (pin "2") (pinfunction "2_2") (pintype "passive"))
      (node (ref "R103") (pin "1") (pinfunction "1_1") (pintype "passive"))
    )
    (net (code "160") (name "Net-(JP24-Pad2)") (class "Default")
      (node (ref "JP24") (pin "2") (pinfunction "2_2") (pintype "passive"))
      (node (ref "R17") (pin "2") (pinfunction "2_2") (pintype "passive"))
    )
    (net (code "161") (name "Net-(JP26-Pad3)") (class "Default")
      (node (ref "JP26") (pin "3") (pinfunction "3_3") (pintype "passive"))
      (node (ref "R92") (pin "1") (pinfunction "1_1") (pintype "passive"))
      (node (ref "R93") (pin "2") (pinfunction "2_2") (pintype "passive"))
    )
    (net (code "162") (name "Net-(LED1-A)") (class "Default")
      (node (ref "LED1") (pin "1") (pinfunction "A_1") (pintype "passive"))
      (node (ref "R10") (pin "1") (pinfunction "1_1") (pintype "passive"))
    )
    (net (code "163") (name "Net-(LED2-A)") (class "Default")
      (node (ref "LED2") (pin "1") (pinfunction "A_1") (pintype "passive"))
      (node (ref "R11") (pin "1") (pinfunction "1_1") (pintype "passive"))
    )
    (net (code "164") (name "Net-(LED3-A)") (class "Default")
      (node (ref "LED3") (pin "1") (pinfunction "A_1") (pintype "passive"))
      (node (ref "R12") (pin "1") (pinfunction "1_1") (pintype "passive"))
    )
    (net (code "165") (name "Net-(LED4-A)") (class "Default")
      (node (ref "LED4") (pin "1") (pinfunction "A_1") (pintype "passive"))
      (node (ref "R13") (pin "1") (pinfunction "1_1") (pintype "passive"))
    )
    (net (code "166") (name "Net-(LED5-A)") (class "Default")
      (node (ref "LED5") (pin "1") (pinfunction "A_1") (pintype "passive"))
      (node (ref "R65") (pin "1") (pinfunction "1_1") (pintype "passive"))
    )
    (net (code "167") (name "Net-(LED6-A)") (class "Default")
      (node (ref "LED6") (pin "1") (pinfunction "A_1") (pintype "passive"))
      (node (ref "R66") (pin "1") (pinfunction "1_1") (pintype "passive"))
    )
    (net (code "168") (name "Net-(LED7-A)") (class "Default")
      (node (ref "LED7") (pin "1") (pinfunction "A_1") (pintype "passive"))
      (node (ref "R67") (pin "1") (pinfunction "1_1") (pintype "passive"))
    )
    (net (code "169") (name "Net-(LED8-A)") (class "Default")
      (node (ref "LED8") (pin "1") (pinfunction "A_1") (pintype "passive"))
      (node (ref "R68") (pin "1") (pinfunction "1_1") (pintype "passive"))
    )
    (net (code "170") (name "Net-(LED9-A)") (class "Default")
      (node (ref "LED9") (pin "1") (pinfunction "A_1") (pintype "passive"))
      (node (ref "R77") (pin "2") (pinfunction "2_2") (pintype "passive"))
    )
    (net (code "171") (name "Net-(LED10-A)") (class "Default")
      (node (ref "LED10") (pin "1") (pinfunction "A_1") (pintype "passive"))
      (node (ref "R78") (pin "1") (pinfunction "1_1") (pintype "passive"))
    )
    (net (code "172") (name "Net-(LED11-A)") (class "Default")
      (node (ref "LED11") (pin "1") (pinfunction "A_1") (pintype "passive"))
      (node (ref "R84") (pin "1") (pinfunction "1_1") (pintype "passive"))
    )
    (net (code "173") (name "Net-(LED12-A)") (class "Default")
      (node (ref "LED12") (pin "1") (pinfunction "A_1") (pintype "passive"))
      (node (ref "R85") (pin "1") (pinfunction "1_1") (pintype "passive"))
    )
    (net (code "174") (name "Net-(PLAY_LED-A)") (class "Default")
      (node (ref "JP24") (pin "3") (pinfunction "3_3") (pintype "passive"))
      (node (ref "PLAY_LED") (pin "1") (pinfunction "A_1") (pintype "passive"))
    )
    (net (code "175") (name "Net-(Q1-D)") (class "Default")
      (node (ref "Q1") (pin "3") (pinfunction "D_3") (pintype "passive"))
      (node (ref "R7") (pin "2") (pinfunction "2_2") (pintype "passive"))
    )
    (net (code "176") (name "Net-(Q4-G)") (class "Default")
      (node (ref "Q4") (pin "1") (pinfunction "G_1") (pintype "passive"))
      (node (ref "R82") (pin "1") (pinfunction "1_1") (pintype "passive"))
      (node (ref "R83") (pin "2") (pinfunction "2_2") (pintype "passive"))
    )
    (net (code "177") (name "Net-(Q5-G)") (class "Default")
      (node (ref "Q5") (pin "1") (pinfunction "G_1") (pintype "passive"))
      (node (ref "R88") (pin "1") (pinfunction "1_1") (pintype "passive"))
    )
    (net (code "178") (name "Net-(Q6-G)") (class "Default")
      (node (ref "Q6") (pin "1") (pinfunction "G_1") (pintype "passive"))
      (node (ref "R69") (pin "1") (pinfunction "1_1") (pintype "passive"))
    )
    (net (code "179") (name "Net-(Q7-G)") (class "Default")
      (node (ref "Q7") (pin "1") (pinfunction "G_1") (pintype "passive"))
      (node (ref "R70") (pin "1") (pinfunction "1_1") (pintype "passive"))
    )
    (net (code "180") (name "Net-(Q8-G)") (class "Default")
      (node (ref "Q8") (pin "1") (pinfunction "G_1") (pintype "passive"))
      (node (ref "R73") (pin "1") (pinfunction "1_1") (pintype "passive"))
      (node (ref "R74") (pin "2") (pinfunction "2_2") (pintype "passive"))
    )
    (net (code "181") (name "Net-(Q9-G)") (class "Default")
      (node (ref "Q9") (pin "1") (pinfunction "G_1") (pintype "passive"))
      (node (ref "R75") (pin "1") (pinfunction "1_1") (pintype "passive"))
      (node (ref "R76") (pin "2") (pinfunction "2_2") (pintype "passive"))
    )
    (net (code "182") (name "Net-(Q10-D)") (class "Default")
      (node (ref "Q10") (pin "4") (pinfunction "D_4") (pintype "passive"))
      (node (ref "X11") (pin "2") (pinfunction "2_2") (pintype "passive"))
    )
    (net (code "183") (name "Net-(R86-Pad1)") (class "Default")
      (node (ref "R86") (pin "1") (pinfunction "1_1") (pintype "passive"))
      (node (ref "TVS1") (pin "4") (pinfunction "4_4") (pintype "passive"))
    )
    (net (code "184") (name "Net-(R117-Pad1)") (class "Default")
      (node (ref "R117") (pin "1") (pinfunction "1_1") (pintype "passive"))
      (node (ref "R118") (pin "2") (pinfunction "2_2") (pintype "passive"))
    )
    (net (code "185") (name "Net-(R118-Pad1)") (class "Default")
      (node (ref "R118") (pin "1") (pinfunction "1_1") (pintype "passive"))
      (node (ref "RV1") (pin "1") (pinfunction "1_1") (pintype "passive"))
    )
    (net (code "186") (name "Net-(R137-Pad1)") (class "Default")
      (node (ref "R137") (pin "1") (pinfunction "1_1") (pintype "passive"))
      (node (ref "R138") (pin "2") (pinfunction "2_2") (pintype "passive"))
    )
    (net (code "187") (name "Net-(R138-Pad1)") (class "Default")
      (node (ref "R138") (pin "1") (pinfunction "1_1") (pintype "passive"))
      (node (ref "RV2") (pin "1") (pinfunction "1_1") (pintype "passive"))
    )
    (net (code "188") (name "Net-(R157-Pad1)") (class "Default")
      (node (ref "R157") (pin "1") (pinfunction "1_1") (pintype "passive"))
      (node (ref "R158") (pin "2") (pinfunction "2_2") (pintype "passive"))
    )
    (net (code "189") (name "Net-(R158-Pad1)") (class "Default")
      (node (ref "R158") (pin "1") (pinfunction "1_1") (pintype "passive"))
      (node (ref "RV3") (pin "1") (pinfunction "1_1") (pintype "passive"))
    )
    (net (code "190") (name "Net-(R177-Pad1)") (class "Default")
      (node (ref "R177") (pin "1") (pinfunction "1_1") (pintype "passive"))
      (node (ref "R178") (pin "2") (pinfunction "2_2") (pintype "passive"))
    )
    (net (code "191") (name "Net-(R178-Pad1)") (class "Default")
      (node (ref "R178") (pin "1") (pinfunction "1_1") (pintype "passive"))
      (node (ref "RV4") (pin "1") (pinfunction "1_1") (pintype "passive"))
    )
    (net (code "192") (name "Net-(R197-Pad1)") (class "Default")
      (node (ref "R197") (pin "1") (pinfunction "1_1") (pintype "passive"))
      (node (ref "R198") (pin "2") (pinfunction "2_2") (pintype "passive"))
    )
    (net (code "193") (name "Net-(R198-Pad1)") (class "Default")
      (node (ref "R198") (pin "1") (pinfunction "1_1") (pintype "passive"))
      (node (ref "RV5") (pin "1") (pinfunction "1_1") (pintype "passive"))
    )
    (net (code "194") (name "Net-(U10-OUT)") (class "Default")
      (node (ref "R69") (pin "2") (pinfunction "2_2") (pintype "passive"))
      (node (ref "U10") (pin "3") (pinfunction "OUT_3") (pintype "passive"))
    )
    (net (code "195") (name "Net-(U15-OUT)") (class "Default")
      (node (ref "R70") (pin "2") (pinfunction "2_2") (pintype "passive"))
      (node (ref "U15") (pin "3") (pinfunction "OUT_3") (pintype "passive"))
    )
    (net (code "196") (name "Net-(U16-OUT)") (class "Default")
      (node (ref "R88") (pin "2") (pinfunction "2_2") (pintype "passive"))
      (node (ref "U16") (pin "3") (pinfunction "OUT_3") (pintype "passive"))
    )
    (net (code "197") (name "Net-(U111-BRA)") (class "Default")
      (node (ref "C117") (pin "1") (pinfunction "1_1") (pintype "passive"))
      (node (ref "R113") (pin "1") (pinfunction "1_1") (pintype "passive"))
      (node (ref "U111") (pin "27") (pinfunction "BRA_27") (pintype "passive"))
    )
    (net (code "198") (name "Net-(U111-BRB)") (class "Default")
      (node (ref "C114") (pin "2") (pinfunction "2_2") (pintype "passive"))
      (node (ref "R111") (pin "2") (pinfunction "2_2") (pintype "passive"))
      (node (ref "U111") (pin "2") (pinfunction "BRB_2") (pintype "passive"))
    )
    (net (code "199") (name "Net-(U111-CPI)") (class "Default")
      (node (ref "C118") (pin "2") (pinfunction "2_2") (pintype "passive"))
      (node (ref "U111") (pin "8") (pinfunction "CPI_8") (pintype "passive"))
    )
    (net (code "200") (name "Net-(U111-CPO)") (class "Default")
      (node (ref "C118") (pin "1") (pinfunction "1_1") (pintype "passive"))
      (node (ref "U111") (pin "7") (pinfunction "CPO_7") (pintype "passive"))
    )
    (net (code "201") (name "Net-(U111-STDBY)") (class "Default")
      (node (ref "R115") (pin "1") (pinfunction "1_1") (pintype "passive"))
      (node (ref "U111") (pin "24") (pinfunction "STDBY_24") (pintype "passive"))
    )
    (net (code "202") (name "Net-(U111-VCP)") (class "Default")
      (node (ref "C119") (pin "2") (pinfunction "2_2") (pintype "passive"))
      (node (ref "U111") (pin "9") (pinfunction "VCP_9") (pintype "passive"))
    )
    (net (code "203") (name "Net-(U131-BRA)") (class "Default")
      (node (ref "C137") (pin "1") (pinfunction "1_1") (pintype "passive"))
      (node (ref "R133") (pin "1") (pinfunction "1_1") (pintype "passive"))
      (node (ref "U131") (pin "27") (pinfunction "BRA_27") (pintype "passive"))
    )
    (net (code "204") (name "Net-(U131-BRB)") (class "Default")
      (node (ref "C134") (pin "2") (pinfunction "2_2") (pintype "passive"))
      (node (ref "R131") (pin "2") (pinfunction "2_2") (pintype "passive"))
      (node (ref "U131") (pin "2") (pinfunction "BRB_2") (pintype "passive"))
    )
    (net (code "205") (name "Net-(U131-CPI)") (class "Default")
      (node (ref "C138") (pin "2") (pinfunction "2_2") (pintype "passive"))
      (node (ref "U131") (pin "8") (pinfunction "CPI_8") (pintype "passive"))
    )
    (net (code "206") (name "Net-(U131-CPO)") (class "Default")
      (node (ref "C138") (pin "1") (pinfunction "1_1") (pintype "passive"))
      (node (ref "U131") (pin "7") (pinfunction "CPO_7") (pintype "passive"))
    )
    (net (code "207") (name "Net-(U131-STDBY)") (class "Default")
      (node (ref "R135") (pin "1") (pinfunction "1_1") (pintype "passive"))
      (node (ref "U131") (pin "24") (pinfunction "STDBY_24") (pintype "passive"))
    )
    (net (code "208") (name "Net-(U131-VCP)") (class "Default")
      (node (ref "C139") (pin "2") (pinfunction "2_2") (pintype "passive"))
      (node (ref "U131") (pin "9") (pinfunction "VCP_9") (pintype "passive"))
    )
    (net (code "209") (name "Net-(U151-BRA)") (class "Default")
      (node (ref "C157") (pin "1") (pinfunction "1_1") (pintype "passive"))
      (node (ref "R153") (pin "1") (pinfunction "1_1") (pintype "passive"))
      (node (ref "U151") (pin "27") (pinfunction "BRA_27") (pintype "passive"))
    )
    (net (code "210") (name "Net-(U151-BRB)") (class "Default")
      (node (ref "C154") (pin "2") (pinfunction "2_2") (pintype "passive"))
      (node (ref "R151") (pin "2") (pinfunction "2_2") (pintype "passive"))
      (node (ref "U151") (pin "2") (pinfunction "BRB_2") (pintype "passive"))
    )
    (net (code "211") (name "Net-(U151-CPI)") (class "Default")
      (node (ref "C158") (pin "2") (pinfunction "2_2") (pintype "passive"))
      (node (ref "U151") (pin "8") (pinfunction "CPI_8") (pintype "passive"))
    )
    (net (code "212") (name "Net-(U151-CPO)") (class "Default")
      (node (ref "C158") (pin "1") (pinfunction "1_1") (pintype "passive"))
      (node (ref "U151") (pin "7") (pinfunction "CPO_7") (pintype "passive"))
    )
    (net (code "213") (name "Net-(U151-STDBY)") (class "Default")
      (node (ref "R155") (pin "1") (pinfunction "1_1") (pintype "passive"))
      (node (ref "U151") (pin "24") (pinfunction "STDBY_24") (pintype "passive"))
    )
    (net (code "214") (name "Net-(U151-VCP)") (class "Default")
      (node (ref "C159") (pin "2") (pinfunction "2_2") (pintype "passive"))
      (node (ref "U151") (pin "9") (pinfunction "VCP_9") (pintype "passive"))
    )
    (net (code "215") (name "Net-(U171-BRA)") (class "Default")
      (node (ref "C177") (pin "1") (pinfunction "1_1") (pintype "passive"))
      (node (ref "R173") (pin "1") (pinfunction "1_1") (pintype "passive"))
      (node (ref "U171") (pin "27") (pinfunction "BRA_27") (pintype "passive"))
    )
    (net (code "216") (name "Net-(U171-BRB)") (class "Default")
      (node (ref "C174") (pin "2") (pinfunction "2_2") (pintype "passive"))
      (node (ref "R171") (pin "2") (pinfunction "2_2") (pintype "passive"))
      (node (ref "U171") (pin "2") (pinfunction "BRB_2") (pintype "passive"))
    )
    (net (code "217") (name "Net-(U171-CPI)") (class "Default")
      (node (ref "C178") (pin "2") (pinfunction "2_2") (pintype "passive"))
      (node (ref "U171") (pin "8") (pinfunction "CPI_8") (pintype "passive"))
    )
    (net (code "218") (name "Net-(U171-CPO)") (class "Default")
      (node (ref "C178") (pin "1") (pinfunction "1_1") (pintype "passive"))
      (node (ref "U171") (pin "7") (pinfunction "CPO_7") (pintype "passive"))
    )
    (net (code "219") (name "Net-(U171-STDBY)") (class "Default")
      (node (ref "R175") (pin "1") (pinfunction "1_1") (pintype "passive"))
      (node (ref "U171") (pin "24") (pinfunction "STDBY_24") (pintype "passive"))
    )
    (net (code "220") (name "Net-(U171-VCP)") (class "Default")
      (node (ref "C179") (pin "2") (pinfunction "2_2") (pintype "passive"))
      (node (ref "U171") (pin "9") (pinfunction "VCP_9") (pintype "passive"))
    )
    (net (code "221") (name "Net-(U191-BRA)") (class "Default")
      (node (ref "C197") (pin "1") (pinfunction "1_1") (pintype "passive"))
      (node (ref "R193") (pin "1") (pinfunction "1_1") (pintype "passive"))
      (node (ref "U191") (pin "27") (pinfunction "BRA_27") (pintype "passive"))
    )
    (net (code "222") (name "Net-(U191-BRB)") (class "Default")
      (node (ref "C194") (pin "2") (pinfunction "2_2") (pintype "passive"))
      (node (ref "R191") (pin "2") (pinfunction "2_2") (pintype "passive"))
      (node (ref "U191") (pin "2") (pinfunction "BRB_2") (pintype "passive"))
    )
    (net (code "223") (name "Net-(U191-CPI)") (class "Default")
      (node (ref "C198") (pin "2") (pinfunction "2_2") (pintype "passive"))
      (node (ref "U191") (pin "8") (pinfunction "CPI_8") (pintype "passive"))
    )
    (net (code "224") (name "Net-(U191-CPO)") (class "Default")
      (node (ref "C198") (pin "1") (pinfunction "1_1") (pintype "passive"))
      (node (ref "U191") (pin "7") (pinfunction "CPO_7") (pintype "passive"))
    )
    (net (code "225") (name "Net-(U191-STDBY)") (class "Default")
      (node (ref "R195") (pin "1") (pinfunction "1_1") (pintype "passive"))
      (node (ref "U191") (pin "24") (pinfunction "STDBY_24") (pintype "passive"))
    )
    (net (code "226") (name "Net-(U191-VCP)") (class "Default")
      (node (ref "C199") (pin "2") (pinfunction "2_2") (pintype "passive"))
      (node (ref "U191") (pin "9") (pinfunction "VCP_9") (pintype "passive"))
    )
    (net (code "227") (name "Net-(X14-D+)") (class "Default")
      (node (ref "R8") (pin "1") (pinfunction "1_1") (pintype "passive"))
      (node (ref "TVS1") (pin "3") (pintype "passive"))
      (node (ref "X14") (pin "3") (pinfunction "D+_3") (pintype "passive"))
    )
    (net (code "228") (name "Net-(X14-D-)") (class "Default")
      (node (ref "R9") (pin "1") (pinfunction "1_1") (pintype "passive"))
      (node (ref "TVS1") (pin "2") (pintype "passive"))
      (node (ref "X14") (pin "2") (pinfunction "D-_2") (pintype "passive"))
    )
    (net (code "229") (name "PGND") (class "Default")
      (node (ref "C111") (pin "2") (pinfunction "2_2") (pintype "passive"))
      (node (ref "C112") (pin "1") (pinfunction "1_1") (pintype "passive"))
      (node (ref "C113") (pin "2") (pinfunction "2_2") (pintype "passive"))
      (node (ref "C114") (pin "1") (pinfunction "1_1") (pintype "passive"))
      (node (ref "C115") (pin "1") (pinfunction "1_1") (pintype "passive"))
      (node (ref "C116") (pin "2") (pinfunction "2_2") (pintype "passive"))
      (node (ref "C117") (pin "2") (pinfunction "2_2") (pintype "passive"))
      (node (ref "C120") (pin "2") (pinfunction "2_2") (pintype "passive"))
      (node (ref "C121") (pin "2") (pinfunction "2_2") (pintype "passive"))
      (node (ref "C122") (pin "2") (pinfunction "2_2") (pintype "passive"))
      (node (ref "C123") (pin "2") (pinfunction "2_2") (pintype "passive"))
      (node (ref "C124") (pin "2") (pinfunction "2_2") (pintype "passive"))
      (node (ref "C125") (pin "2") (pinfunction "2_2") (pintype "passive"))
      (node (ref "C126") (pin "2") (pinfunction "2_2") (pintype "passive"))
      (node (ref "C131") (pin "2") (pinfunction "2_2") (pintype "passive"))
      (node (ref "C132") (pin "1") (pinfunction "1_1") (pintype "passive"))
      (node (ref "C133") (pin "2") (pinfunction "2_2") (pintype "passive"))
      (node (ref "C134") (pin "1") (pinfunction "1_1") (pintype "passive"))
      (node (ref "C135") (pin "1") (pinfunction "1_1") (pintype "passive"))
      (node (ref "C136") (pin "2") (pinfunction "2_2") (pintype "passive"))
      (node (ref "C137") (pin "2") (pinfunction "2_2") (pintype "passive"))
      (node (ref "C140") (pin "2") (pinfunction "2_2") (pintype "passive"))
      (node (ref "C141") (pin "2") (pinfunction "2_2") (pintype "passive"))
      (node (ref "C142") (pin "2") (pinfunction "2_2") (pintype "passive"))
      (node (ref "C143") (pin "2") (pinfunction "2_2") (pintype "passive"))
      (node (ref "C144") (pin "2") (pinfunction "2_2") (pintype "passive"))
      (node (ref "C145") (pin "2") (pinfunction "2_2") (pintype "passive"))
      (node (ref "C146") (pin "2") (pinfunction "2_2") (pintype "passive"))
      (node (ref "C151") (pin "2") (pinfunction "2_2") (pintype "passive"))
      (node (ref "C152") (pin "1") (pinfunction "1_1") (pintype "passive"))
      (node (ref "C153") (pin "2") (pinfunction "2_2") (pintype "passive"))
      (node (ref "C154") (pin "1") (pinfunction "1_1") (pintype "passive"))
      (node (ref "C155") (pin "1") (pinfunction "1_1") (pintype "passive"))
      (node (ref "C156") (pin "2") (pinfunction "2_2") (pintype "passive"))
      (node (ref "C157") (pin "2") (pinfunction "2_2") (pintype "passive"))
      (node (ref "C160") (pin "2") (pinfunction "2_2") (pintype "passive"))
      (node (ref "C161") (pin "2") (pinfunction "2_2") (pintype "passive"))
      (node (ref "C162") (pin "2") (pinfunction "2_2") (pintype "passive"))
      (node (ref "C163") (pin "2") (pinfunction "2_2") (pintype "passive"))
      (node (ref "C164") (pin "2") (pinfunction "2_2") (pintype "passive"))
      (node (ref "C165") (pin "2") (pinfunction "2_2") (pintype "passive"))
      (node (ref "C166") (pin "2") (pinfunction "2_2") (pintype "passive"))
      (node (ref "C171") (pin "2") (pinfunction "2_2") (pintype "passive"))
      (node (ref "C172") (pin "1") (pinfunction "1_1") (pintype "passive"))
      (node (ref "C173") (pin "2") (pinfunction "2_2") (pintype "passive"))
      (node (ref "C174") (pin "1") (pinfunction "1_1") (pintype "passive"))
      (node (ref "C175") (pin "1") (pinfunction "1_1") (pintype "passive"))
      (node (ref "C176") (pin "2") (pinfunction "2_2") (pintype "passive"))
      (node (ref "C177") (pin "2") (pinfunction "2_2") (pintype "passive"))
      (node (ref "C180") (pin "2") (pinfunction "2_2") (pintype "passive"))
      (node (ref "C181") (pin "2") (pinfunction "2_2") (pintype "passive"))
      (node (ref "C182") (pin "2") (pinfunction "2_2") (pintype "passive"))
      (node (ref "C183") (pin "2") (pinfunction "2_2") (pintype "passive"))
      (node (ref "C184") (pin "2") (pinfunction "2_2") (pintype "passive"))
      (node (ref "C185") (pin "2") (pinfunction "2_2") (pintype "passive"))
      (node (ref "C186") (pin "2") (pinfunction "2_2") (pintype "passive"))
      (node (ref "C192") (pin "1") (pinfunction "1_1") (pintype "passive"))
      (node (ref "C193") (pin "2") (pinfunction "2_2") (pintype "passive"))
      (node (ref "C194") (pin "1") (pinfunction "1_1") (pintype "passive"))
      (node (ref "C195") (pin "1") (pinfunction "1_1") (pintype "passive"))
      (node (ref "C196") (pin "2") (pinfunction "2_2") (pintype "passive"))
      (node (ref "C197") (pin "2") (pinfunction "2_2") (pintype "passive"))
      (node (ref "C200") (pin "2") (pinfunction "2_2") (pintype "passive"))
      (node (ref "C201") (pin "2") (pinfunction "2_2") (pintype "passive"))
      (node (ref "C202") (pin "2") (pinfunction "2_2") (pintype "passive"))
      (node (ref "C203") (pin "2") (pinfunction "2_2") (pintype "passive"))
      (node (ref "C204") (pin "2") (pinfunction "2_2") (pintype "passive"))
      (node (ref "C205") (pin "2") (pinfunction "2_2") (pintype "passive"))
      (node (ref "C206") (pin "2") (pinfunction "2_2") (pintype "passive"))
      (node (ref "C63") (pin "1") (pinfunction "1_1") (pintype "passive"))
      (node (ref "D5") (pin "1") (pinfunction "A_1") (pintype "passive"))
      (node (ref "J111") (pin "2") (pinfunction "2_2") (pintype "passive"))
      (node (ref "J131") (pin "2") (pinfunction "2_2") (pintype "passive"))
      (node (ref "J151") (pin "2") (pinfunction "2_2") (pintype "passive"))
      (node (ref "J171") (pin "2") (pinfunction "2_2") (pintype "passive"))
      (node (ref "J191") (pin "2") (pinfunction "2_2") (pintype "passive"))
      (node (ref "LED10") (pin "2") (pinfunction "K_2") (pintype "passive"))
      (node (ref "Q10") (pin "3") (pinfunction "S_3") (pintype "passive"))
      (node (ref "Q4") (pin "2") (pinfunction "S_2") (pintype "passive"))
      (node (ref "Q5") (pin "3") (pinfunction "S_3") (pintype "passive"))
      (node (ref "Q6") (pin "3") (pinfunction "S_3") (pintype "passive"))
      (node (ref "Q7") (pin "3") (pinfunction "S_3") (pintype "passive"))
      (node (ref "Q8") (pin "2") (pinfunction "S_2") (pintype "passive"))
      (node (ref "Q9") (pin "2") (pinfunction "S_2") (pintype "passive"))
      (node (ref "R111") (pin "1") (pinfunction "1_1") (pintype "passive"))
      (node (ref "R113") (pin "2") (pinfunction "2_2") (pintype "passive"))
      (node (ref "R115") (pin "2") (pinfunction "2_2") (pintype "passive"))
      (node (ref "R121") (pin "1") (pinfunction "1_1") (pintype "passive"))
      (node (ref "R131") (pin "1") (pinfunction "1_1") (pintype "passive"))
      (node (ref "R133") (pin "2") (pinfunction "2_2") (pintype "passive"))
      (node (ref "R135") (pin "2") (pinfunction "2_2") (pintype "passive"))
      (node (ref "R141") (pin "1") (pinfunction "1_1") (pintype "passive"))
      (node (ref "R151") (pin "1") (pinfunction "1_1") (pintype "passive"))
      (node (ref "R153") (pin "2") (pinfunction "2_2") (pintype "passive"))
      (node (ref "R155") (pin "2") (pinfunction "2_2") (pintype "passive"))
      (node (ref "R161") (pin "1") (pinfunction "1_1") (pintype "passive"))
      (node (ref "R171") (pin "1") (pinfunction "1_1") (pintype "passive"))
      (node (ref "R173") (pin "2") (pinfunction "2_2") (pintype "passive"))
      (node (ref "R175") (pin "2") (pinfunction "2_2") (pintype "passive"))
      (node (ref "R181") (pin "1") (pinfunction "1_1") (pintype "passive"))
      (node (ref "R191") (pin "1") (pinfunction "1_1") (pintype "passive"))
      (node (ref "R193") (pin "2") (pinfunction "2_2") (pintype "passive"))
      (node (ref "R195") (pin "2") (pinfunction "2_2") (pintype "passive"))
      (node (ref "R201") (pin "1") (pinfunction "1_1") (pintype "passive"))
      (node (ref "R74") (pin "1") (pinfunction "1_1") (pintype "passive"))
      (node (ref "R76") (pin "1") (pinfunction "1_1") (pintype "passive"))
      (node (ref "R83") (pin "1") (pinfunction "1_1") (pintype "passive"))
      (node (ref "R90") (pin "1") (pinfunction "1_1") (pintype "passive"))
      (node (ref "R91") (pin "1") (pinfunction "1_1") (pintype "passive"))
      (node (ref "U111") (pin "0") (pinfunction "EPAD_0") (pintype "passive"))
      (node (ref "U111") (pin "13") (pinfunction "NC_13") (pintype "passive"))
      (node (ref "U111") (pin "17") (pinfunction "CLK_17") (pintype "passive"))
      (node (ref "U111") (pin "22") (pinfunction "GND_22") (pintype "passive"))
      (node (ref "U111") (pin "6") (pinfunction "GND_6") (pintype "passive"))
      (node (ref "U131") (pin "0") (pinfunction "EPAD_0") (pintype "passive"))
      (node (ref "U131") (pin "13") (pinfunction "NC_13") (pintype "passive"))
      (node (ref "U131") (pin "17") (pinfunction "CLK_17") (pintype "passive"))
      (node (ref "U131") (pin "22") (pinfunction "GND_22") (pintype "passive"))
      (node (ref "U131") (pin "6") (pinfunction "GND_6") (pintype "passive"))
      (node (ref "U151") (pin "0") (pinfunction "EPAD_0") (pintype "passive"))
      (node (ref "U151") (pin "13") (pinfunction "NC_13") (pintype "passive"))
      (node (ref "U151") (pin "17") (pinfunction "CLK_17") (pintype "passive"))
      (node (ref "U151") (pin "22") (pinfunction "GND_22") (pintype "passive"))
      (node (ref "U151") (pin "6") (pinfunction "GND_6") (pintype "passive"))
      (node (ref "U171") (pin "0") (pinfunction "EPAD_0") (pintype "passive"))
      (node (ref "U171") (pin "13") (pinfunction "NC_13") (pintype "passive"))
      (node (ref "U171") (pin "17") (pinfunction "CLK_17") (pintype "passive"))
      (node (ref "U171") (pin "22") (pinfunction "GND_22") (pintype "passive"))
      (node (ref "U171") (pin "6") (pinfunction "GND_6") (pintype "passive"))
      (node (ref "U191") (pin "0") (pinfunction "EPAD_0") (pintype "passive"))
      (node (ref "U191") (pin "13") (pinfunction "NC_13") (pintype "passive"))
      (node (ref "U191") (pin "17") (pinfunction "CLK_17") (pintype "passive"))
      (node (ref "U191") (pin "22") (pinfunction "GND_22") (pintype "passive"))
      (node (ref "U191") (pin "6") (pinfunction "GND_6") (pintype "passive"))
    )
    (net (code "230") (name "VUSB") (class "Default")
      (node (ref "D1") (pin "1") (pinfunction "A_1") (pintype "passive"))
      (node (ref "X14") (pin "1") (pinfunction "VBUS_1") (pintype "passive"))
    )
    (net (code "231") (name "unconnected-(IC1-N.C.-Pad13)") (class "Default")
      (node (ref "IC1") (pin "13") (pinfunction "N.C._13") (pintype "power_in"))
    )
    (net (code "232") (name "unconnected-(IC1-RTCX1-Pad16)") (class "Default")
      (node (ref "IC1") (pin "16") (pinfunction "RTCX1_16") (pintype "bidirectional"))
    )
    (net (code "233") (name "unconnected-(IC1-RTCX2-Pad18)") (class "Default")
      (node (ref "IC1") (pin "18") (pinfunction "RTCX2_18") (pintype "bidirectional"))
    )
    (net (code "234") (name "unconnected-(U1-RSV-Pad1)") (class "Default")
      (node (ref "U1") (pin "1") (pinfunction "RSV_1") (pintype "passive+no_connect"))
    )
    (net (code "235") (name "unconnected-(U1-RSV-Pad8)") (class "Default")
      (node (ref "U1") (pin "8") (pinfunction "RSV_8") (pintype "passive+no_connect"))
    )
    (net (code "236") (name "unconnected-(U111-DIAG-Pad15)") (class "Default")
      (node (ref "U111") (pin "15") (pinfunction "DIAG_15") (pintype "passive"))
    )
    (net (code "237") (name "unconnected-(U111-INDEX-Pad16)") (class "Default")
      (node (ref "U111") (pin "16") (pinfunction "INDEX_16") (pintype "passive"))
    )
    (net (code "238") (name "unconnected-(U131-DIAG-Pad15)") (class "Default")
      (node (ref "U131") (pin "15") (pinfunction "DIAG_15") (pintype "passive"))
    )
    (net (code "239") (name "unconnected-(U131-INDEX-Pad16)") (class "Default")
      (node (ref "U131") (pin "16") (pinfunction "INDEX_16") (pintype "passive"))
    )
    (net (code "240") (name "unconnected-(U151-DIAG-Pad15)") (class "Default")
      (node (ref "U151") (pin "15") (pinfunction "DIAG_15") (pintype "passive"))
    )
    (net (code "241") (name "unconnected-(U151-INDEX-Pad16)") (class "Default")
      (node (ref "U151") (pin "16") (pinfunction "INDEX_16") (pintype "passive"))
    )
    (net (code "242") (name "unconnected-(U171-DIAG-Pad15)") (class "Default")
      (node (ref "U171") (pin "15") (pinfunction "DIAG_15") (pintype "passive"))
    )
    (net (code "243") (name "unconnected-(U171-INDEX-Pad16)") (class "Default")
      (node (ref "U171") (pin "16") (pinfunction "INDEX_16") (pintype "passive"))
    )
    (net (code "244") (name "unconnected-(U191-DIAG-Pad15)") (class "Default")
      (node (ref "U191") (pin "15") (pinfunction "DIAG_15") (pintype "passive"))
    )
    (net (code "245") (name "unconnected-(U191-INDEX-Pad16)") (class "Default")
      (node (ref "U191") (pin "16") (pinfunction "INDEX_16") (pintype "passive"))
    )
    (net (code "246") (name "unconnected-(X14-GND-Pad7)") (class "Default")
      (node (ref "X14") (pin "7") (pinfunction "GND_7") (pintype "passive"))
    )
    (net (code "247") (name "unconnected-(X14-USB3.0_Receive+-Pad6)") (class "Default")
      (node (ref "X14") (pin "6") (pinfunction "USB3.0_Receive+_6") (pintype "passive"))
    )
    (net (code "248") (name "unconnected-(X14-USB3.0_Receive--Pad5)") (class "Default")
      (node (ref "X14") (pin "5") (pinfunction "USB3.0_Receive-_5") (pintype "passive"))
    )
    (net (code "249") (name "unconnected-(X14-USB3.0_Transmit+-Pad9)") (class "Default")
      (node (ref "X14") (pin "9") (pinfunction "USB3.0_Transmit+_9") (pintype "passive"))
    )
    (net (code "250") (name "unconnected-(X14-USB3.0_Transmit--Pad8)") (class "Default")
      (node (ref "X14") (pin "8") (pinfunction "USB3.0_Transmit-_8") (pintype "passive"))
    )
  )
)
